# SlaveBoard_2020.net
KiCad netlist of a schematic drawn in Altium Designer
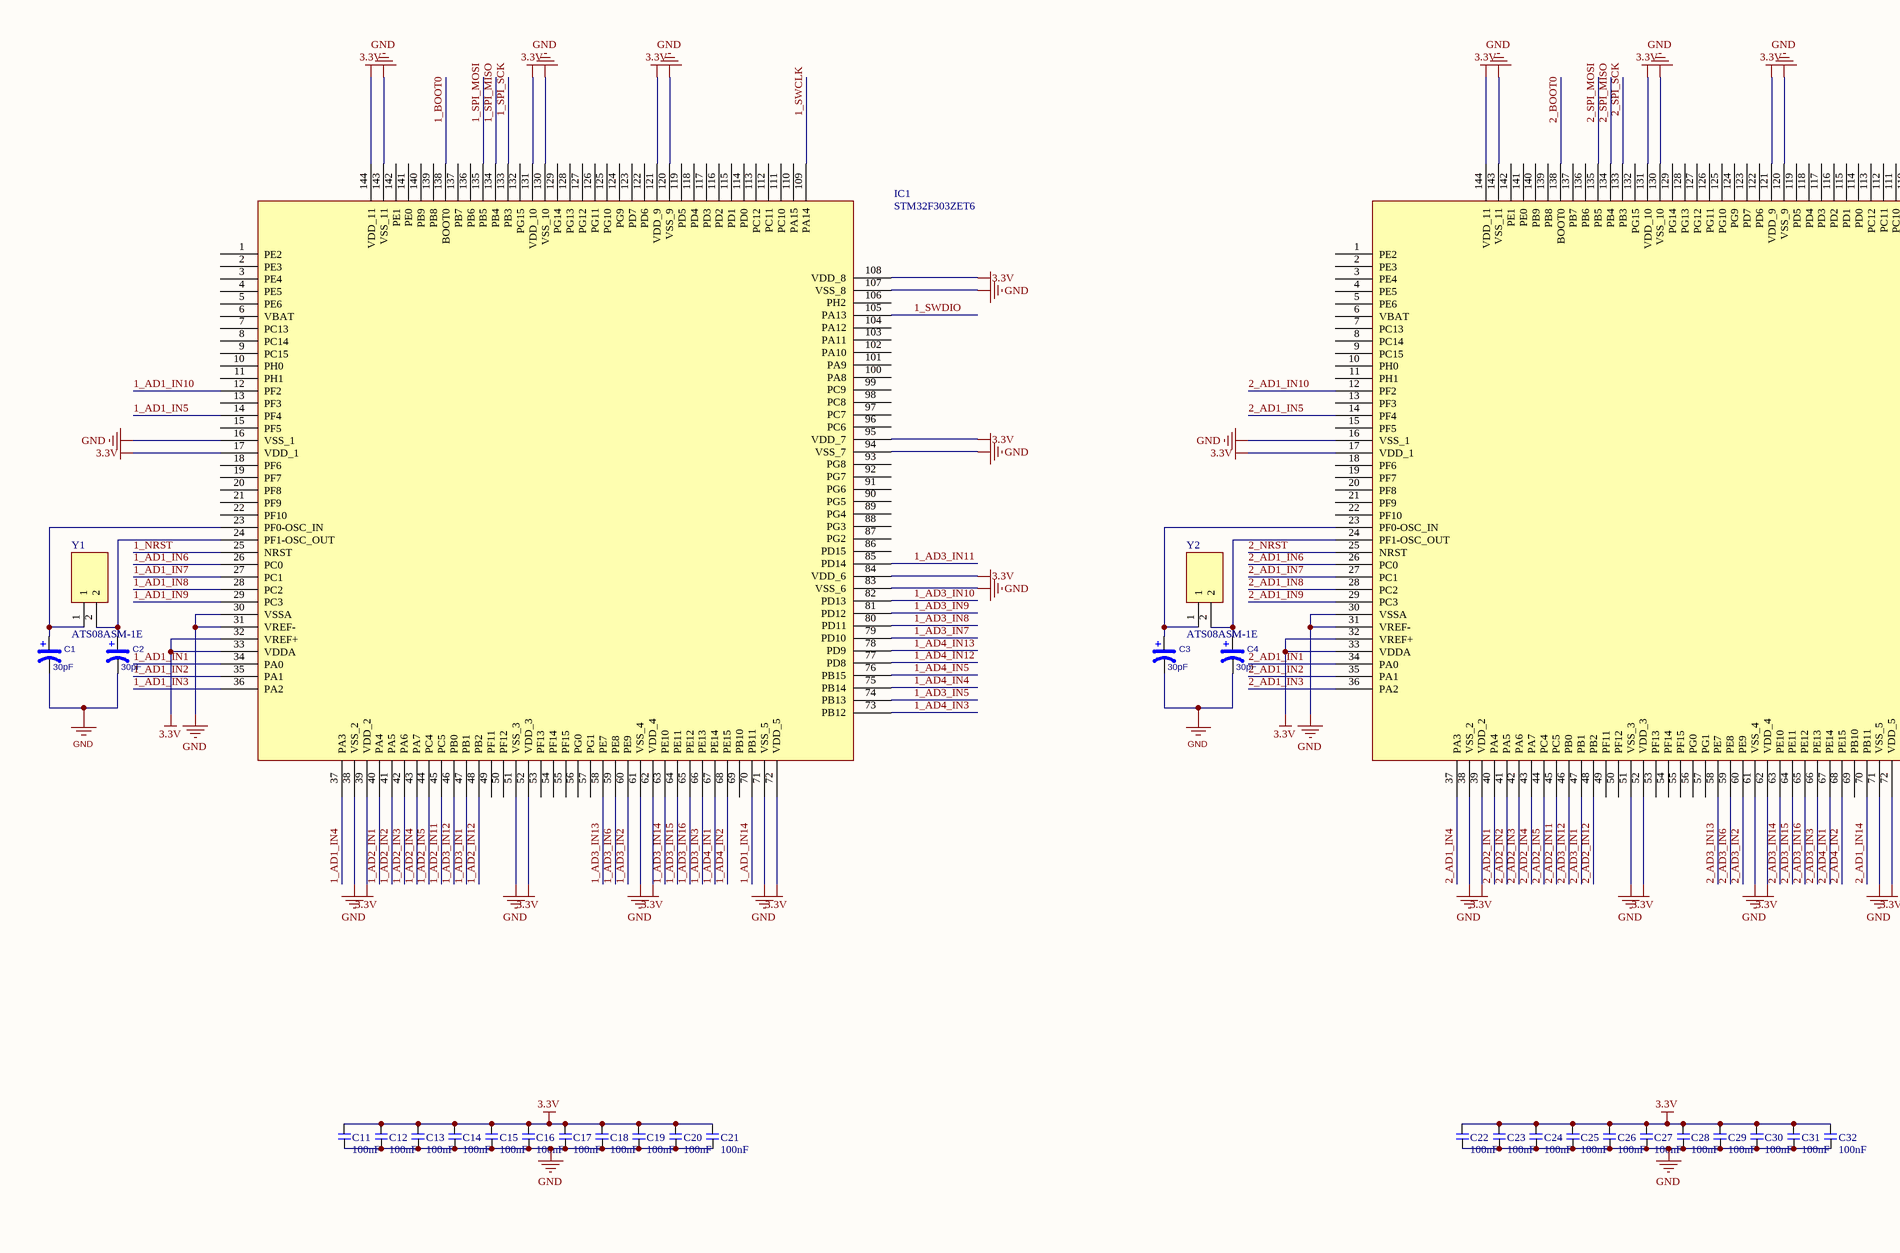
[diagram p0: SlaveBoard_2020.SchDoc, top left]
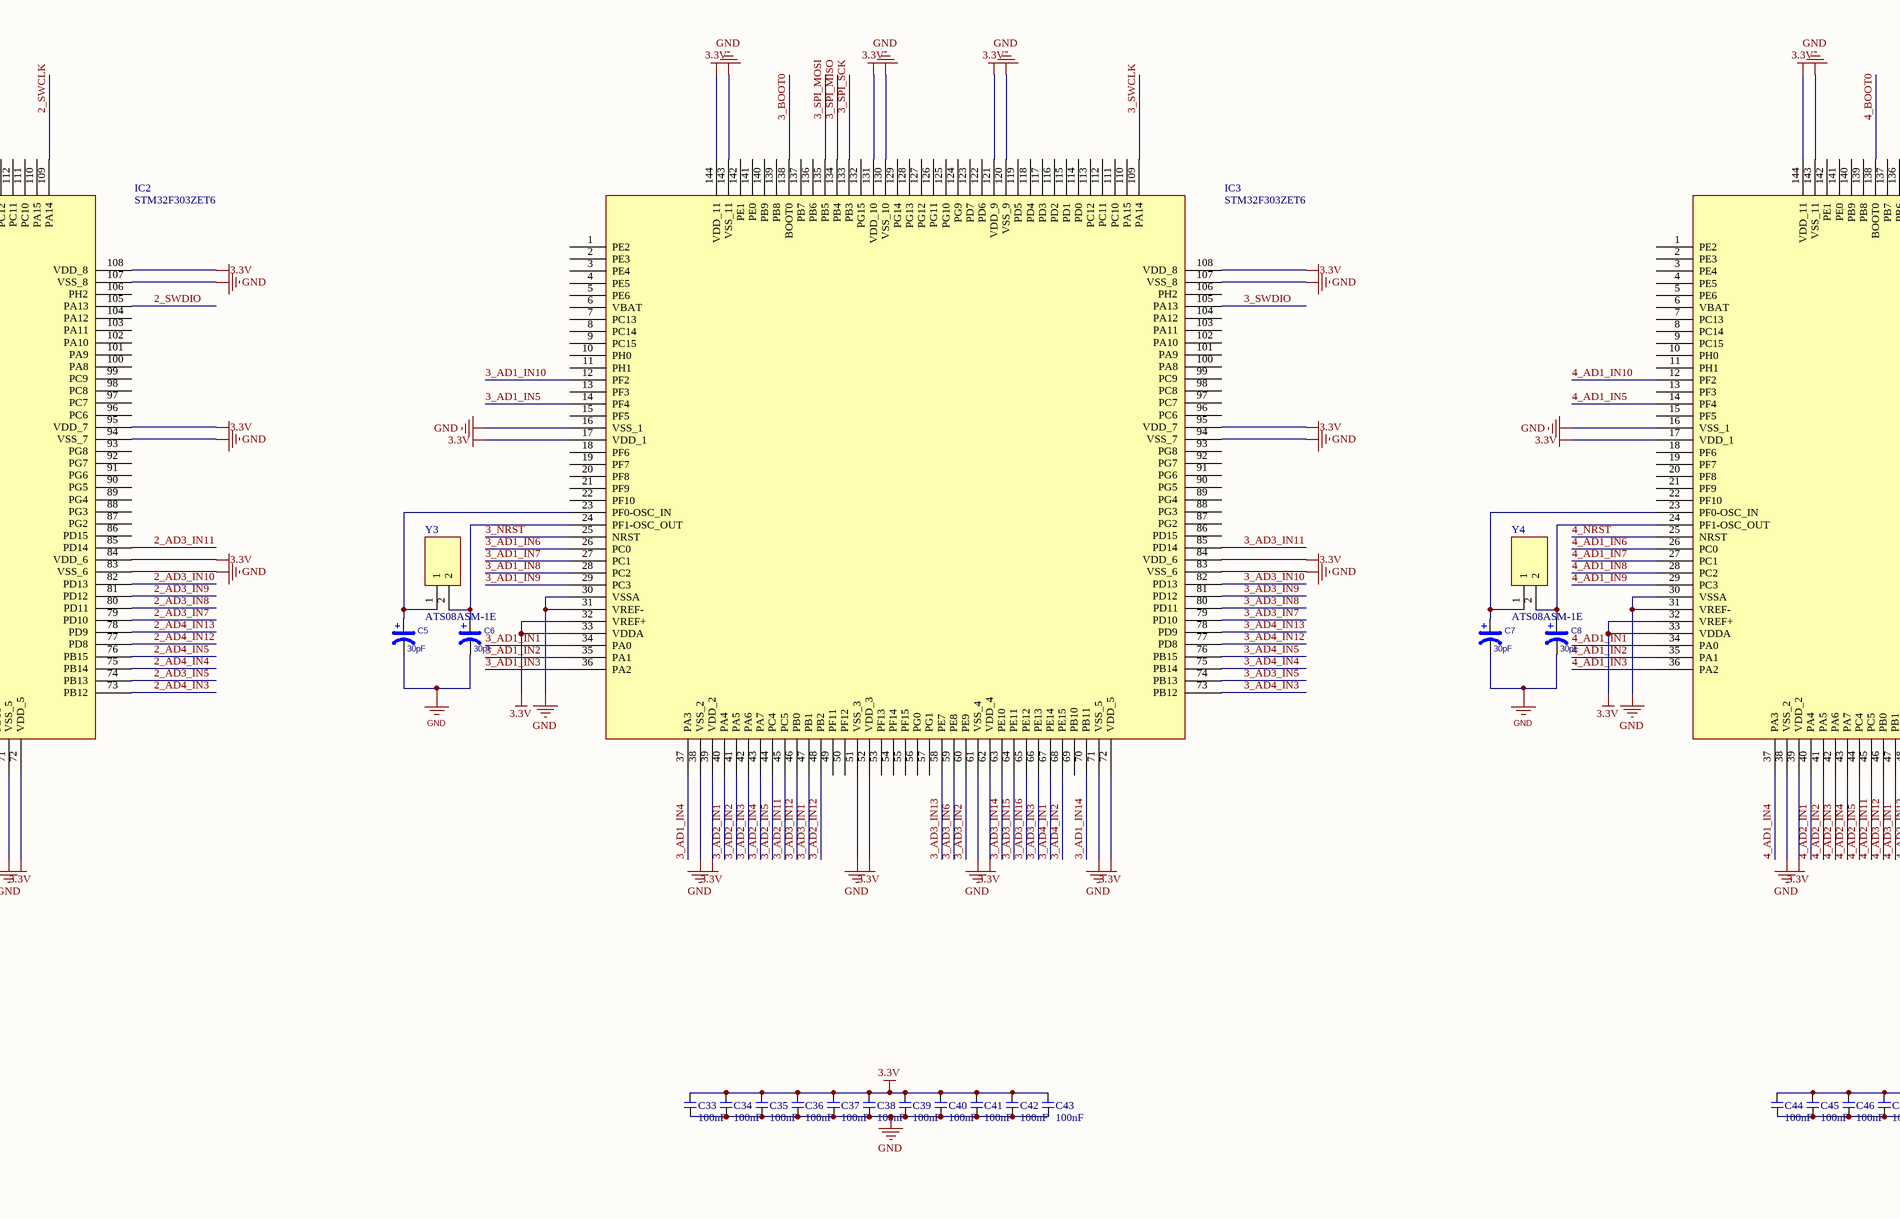
[diagram p1: SlaveBoard_2020.SchDoc, top middle]
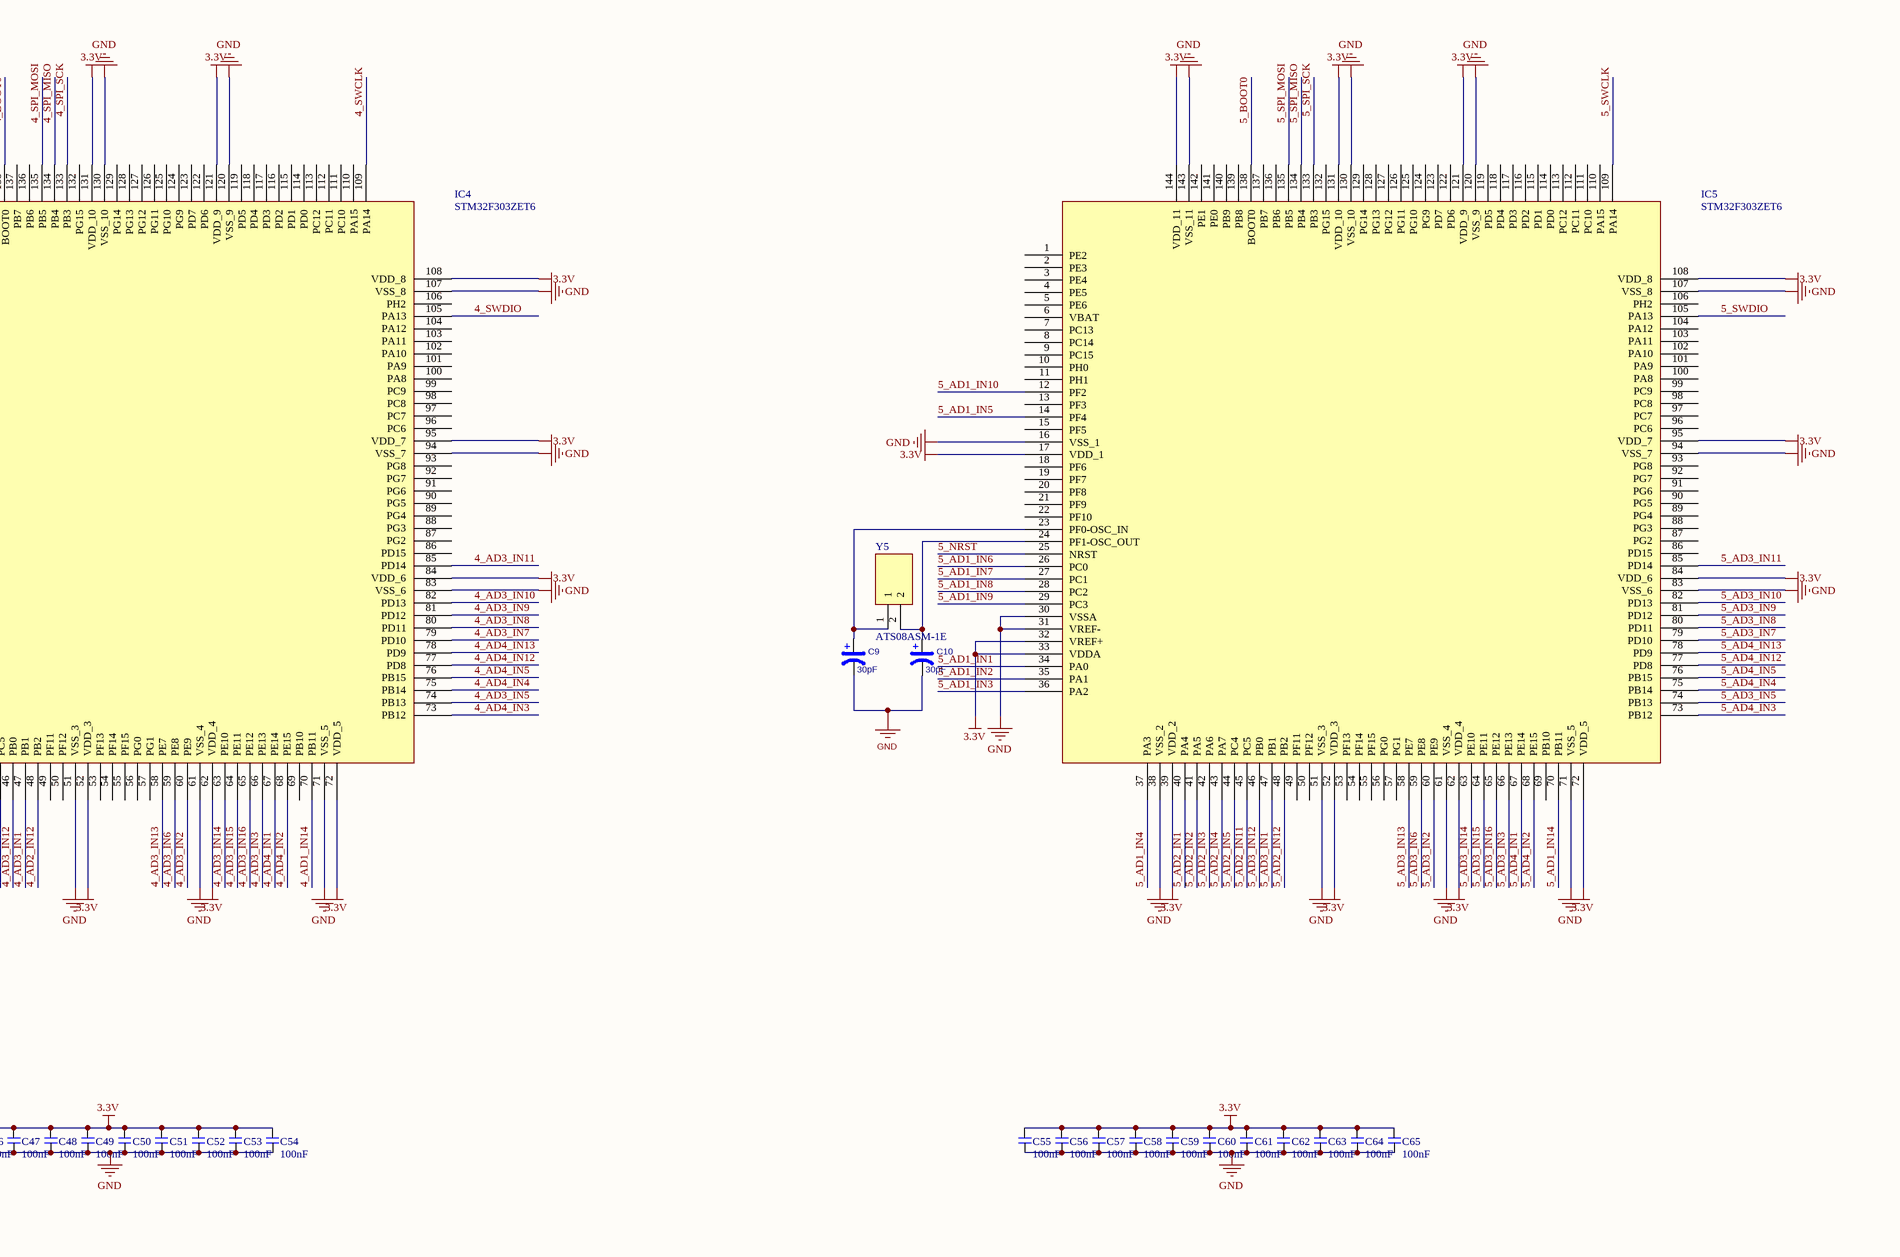
[diagram p2: SlaveBoard_2020.SchDoc, top right]
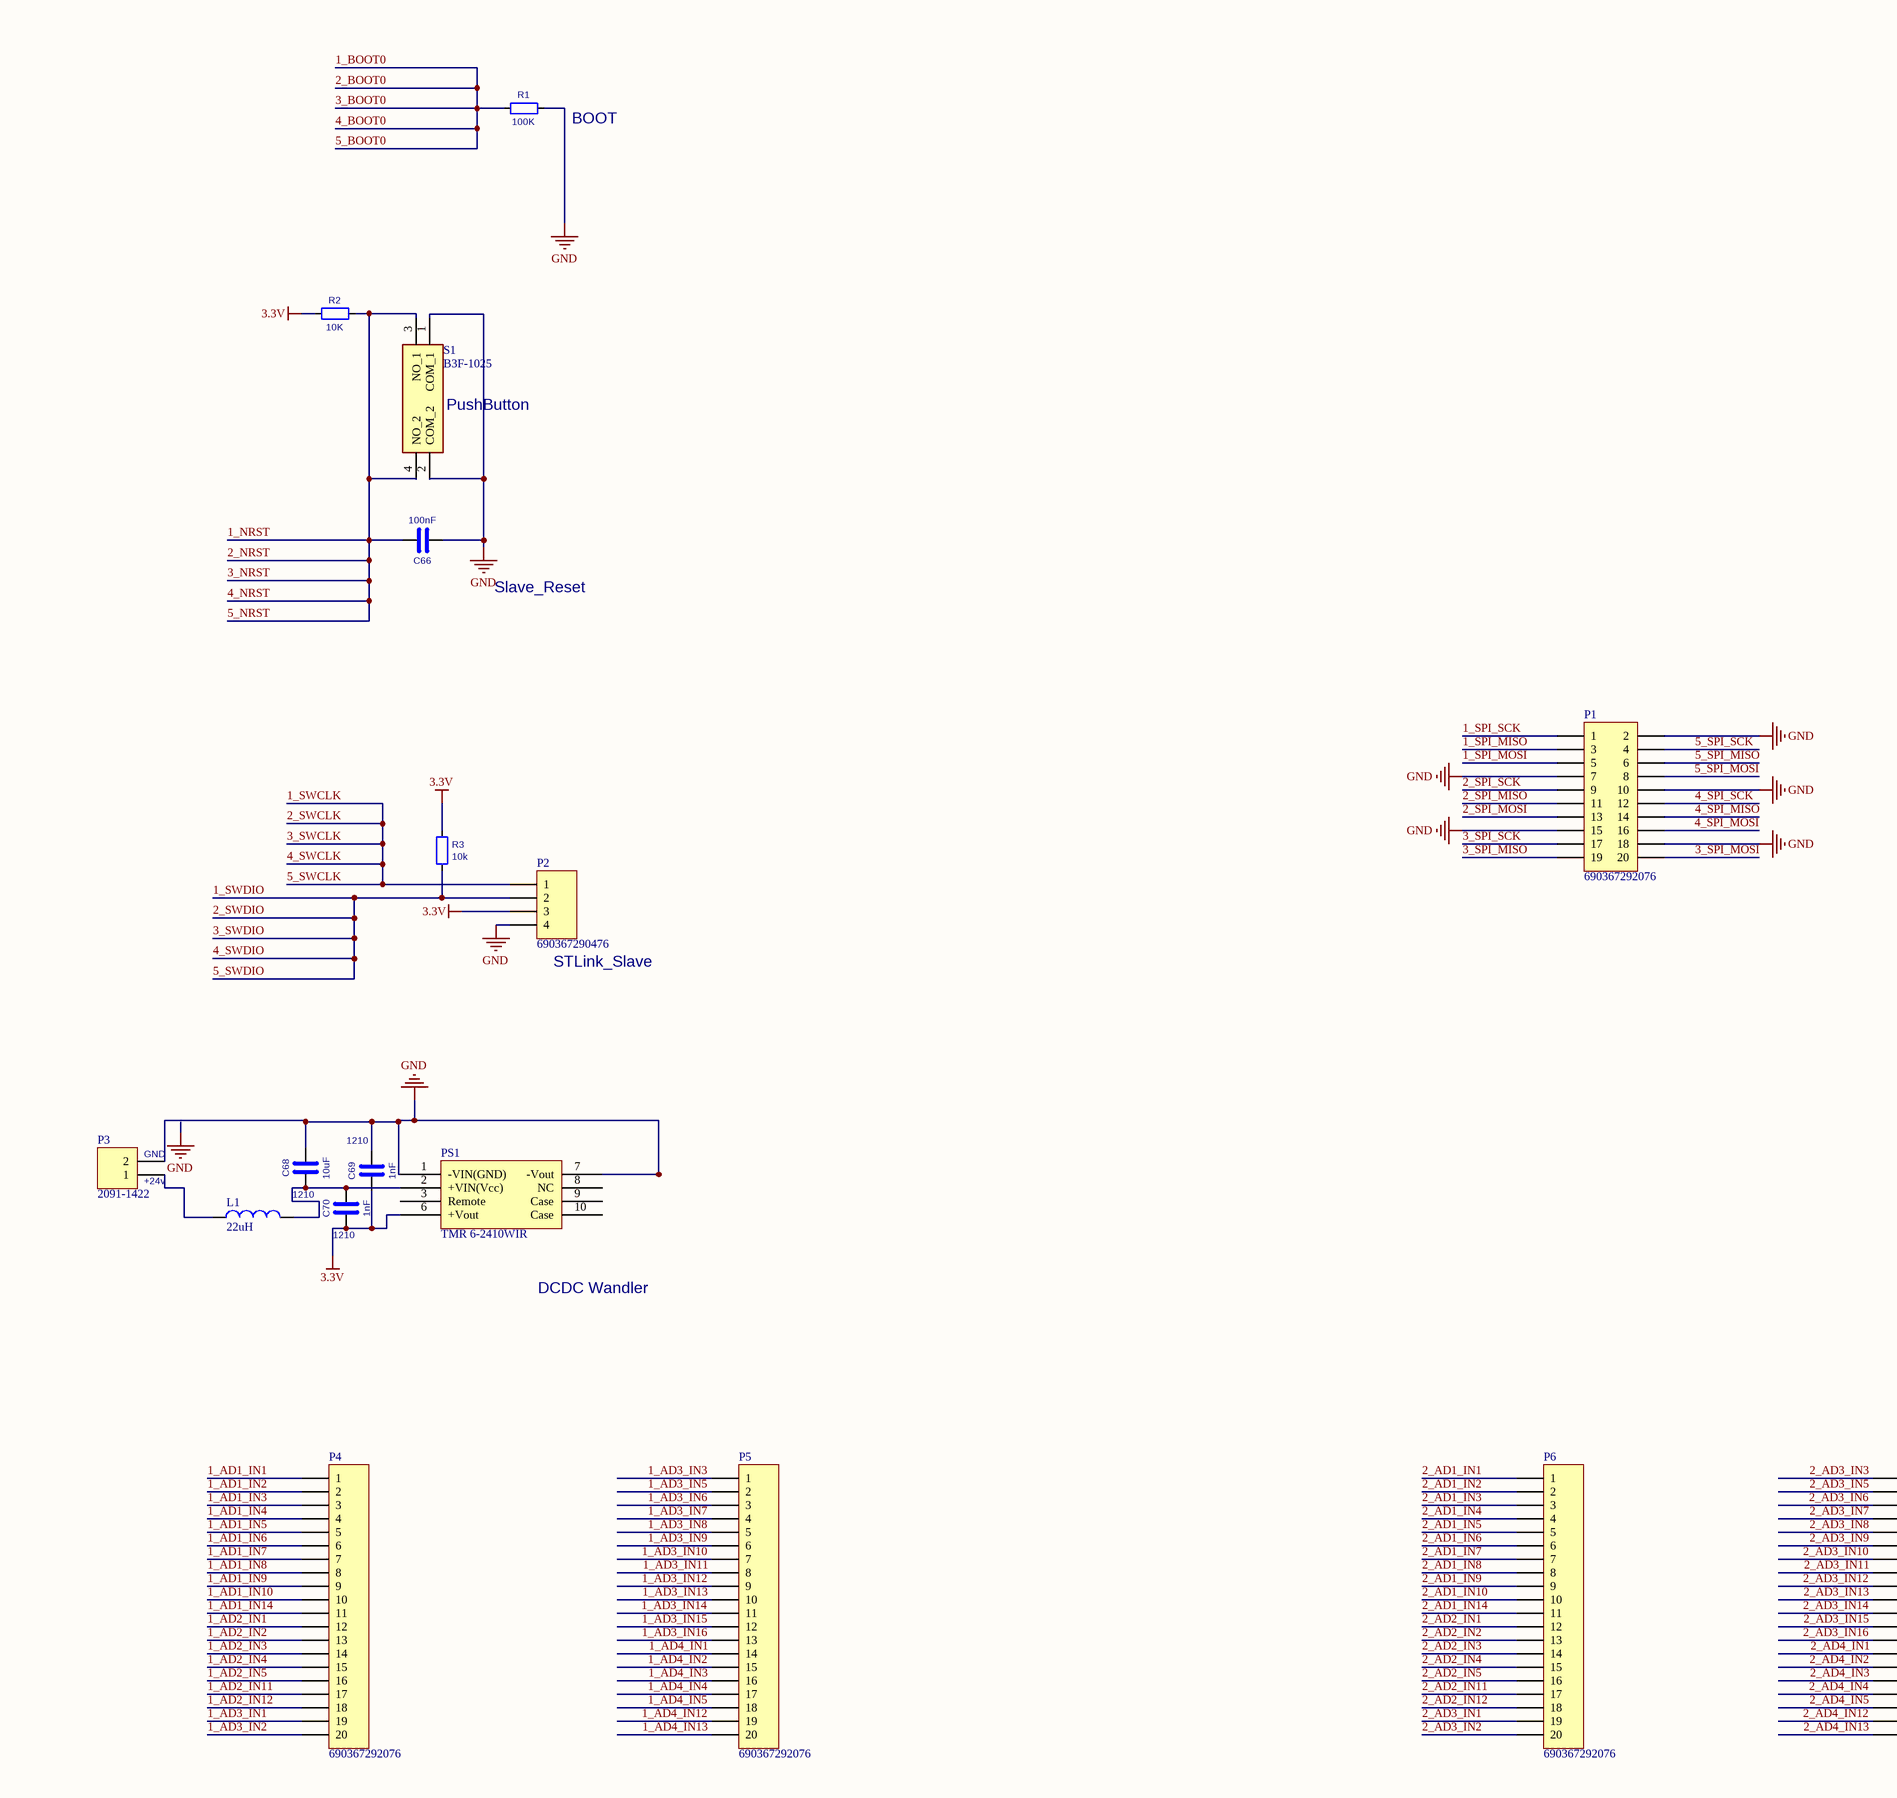
[diagram p3: SlaveBoard_2020.SchDoc, bottom left]
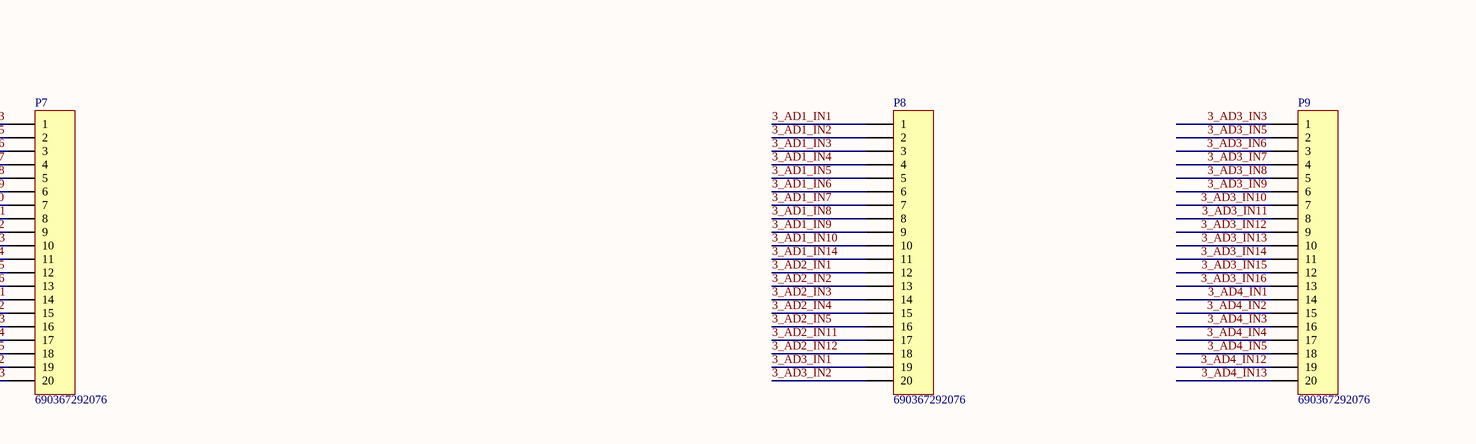
[diagram p4: SlaveBoard_2020.SchDoc, bottom middle]
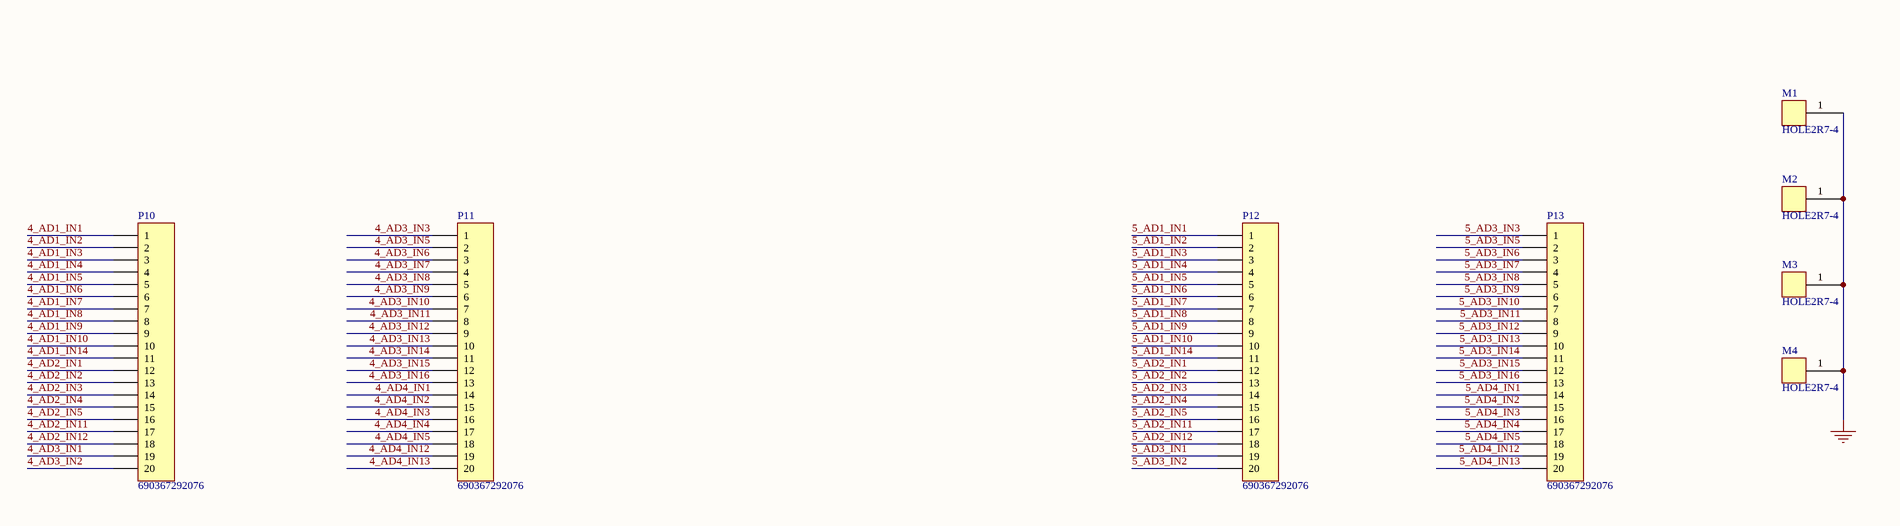
[diagram p5: SlaveBoard_2020.SchDoc, bottom right]

(export (version "E")
  (design (tool "Eeschema 10.0.6"))
  (components
    (comp (ref "C1") (value "30pF") (footprint "C0603") (libsource (lib "Device") (part "CP1")))
    (comp (ref "C2") (value "30pF") (footprint "C0603") (libsource (lib "Device") (part "CP1")))
    (comp (ref "C3") (value "30pF") (footprint "C0603") (libsource (lib "Device") (part "CP1")))
    (comp (ref "C4") (value "30pF") (footprint "C0603") (libsource (lib "Device") (part "CP1")))
    (comp (ref "C5") (value "30pF") (footprint "C0603") (libsource (lib "Device") (part "CP1")))
    (comp (ref "C6") (value "30pF") (footprint "C0603") (libsource (lib "Device") (part "CP1")))
    (comp (ref "C7") (value "30pF") (footprint "C0603") (libsource (lib "Device") (part "CP1")))
    (comp (ref "C8") (value "30pF") (footprint "C0603") (libsource (lib "Device") (part "CP1")))
    (comp (ref "C9") (value "30pF") (footprint "C0603") (libsource (lib "Device") (part "CP1")))
    (comp (ref "C10") (value "30pF") (footprint "C0603") (libsource (lib "Device") (part "CP1")))
    (comp (ref "C11") (value "100nF") (footprint "C0603") (libsource (lib "My_Chip") (part "Cap_0805")))
    (comp (ref "C12") (value "100nF") (footprint "C0603") (libsource (lib "My_Chip") (part "Cap_0805")))
    (comp (ref "C13") (value "100nF") (footprint "C0603") (libsource (lib "My_Chip") (part "Cap_0805")))
    (comp (ref "C14") (value "100nF") (footprint "C0603") (libsource (lib "My_Chip") (part "Cap_0805")))
    (comp (ref "C15") (value "100nF") (footprint "C0603") (libsource (lib "My_Chip") (part "Cap_0805")))
    (comp (ref "C16") (value "100nF") (footprint "C0603") (libsource (lib "My_Chip") (part "Cap_0805")))
    (comp (ref "C17") (value "100nF") (footprint "C0603") (libsource (lib "My_Chip") (part "Cap_0805")))
    (comp (ref "C18") (value "100nF") (footprint "C0603") (libsource (lib "My_Chip") (part "Cap_0805")))
    (comp (ref "C19") (value "100nF") (footprint "C0603") (libsource (lib "My_Chip") (part "Cap_0805")))
    (comp (ref "C20") (value "100nF") (footprint "C0603") (libsource (lib "My_Chip") (part "Cap_0805")))
    (comp (ref "C21") (value "100nF") (footprint "C0603") (libsource (lib "My_Chip") (part "Cap_0805")))
    (comp (ref "C22") (value "100nF") (footprint "C0603") (libsource (lib "My_Chip") (part "Cap_0805")))
    (comp (ref "C23") (value "100nF") (footprint "C0603") (libsource (lib "My_Chip") (part "Cap_0805")))
    (comp (ref "C24") (value "100nF") (footprint "C0603") (libsource (lib "My_Chip") (part "Cap_0805")))
    (comp (ref "C25") (value "100nF") (footprint "C0603") (libsource (lib "My_Chip") (part "Cap_0805")))
    (comp (ref "C26") (value "100nF") (footprint "C0603") (libsource (lib "My_Chip") (part "Cap_0805")))
    (comp (ref "C27") (value "100nF") (footprint "C0603") (libsource (lib "My_Chip") (part "Cap_0805")))
    (comp (ref "C28") (value "100nF") (footprint "C0603") (libsource (lib "My_Chip") (part "Cap_0805")))
    (comp (ref "C29") (value "100nF") (footprint "C0603") (libsource (lib "My_Chip") (part "Cap_0805")))
    (comp (ref "C30") (value "100nF") (footprint "C0603") (libsource (lib "My_Chip") (part "Cap_0805")))
    (comp (ref "C31") (value "100nF") (footprint "C0603") (libsource (lib "My_Chip") (part "Cap_0805")))
    (comp (ref "C32") (value "100nF") (footprint "C0603") (libsource (lib "My_Chip") (part "Cap_0805")))
    (comp (ref "C33") (value "100nF") (footprint "C0603") (libsource (lib "My_Chip") (part "Cap_0805")))
    (comp (ref "C34") (value "100nF") (footprint "C0603") (libsource (lib "My_Chip") (part "Cap_0805")))
    (comp (ref "C35") (value "100nF") (footprint "C0603") (libsource (lib "My_Chip") (part "Cap_0805")))
    (comp (ref "C36") (value "100nF") (footprint "C0603") (libsource (lib "My_Chip") (part "Cap_0805")))
    (comp (ref "C37") (value "100nF") (footprint "C0603") (libsource (lib "My_Chip") (part "Cap_0805")))
    (comp (ref "C38") (value "100nF") (footprint "C0603") (libsource (lib "My_Chip") (part "Cap_0805")))
    (comp (ref "C39") (value "100nF") (footprint "C0603") (libsource (lib "My_Chip") (part "Cap_0805")))
    (comp (ref "C40") (value "100nF") (footprint "C0603") (libsource (lib "My_Chip") (part "Cap_0805")))
    (comp (ref "C41") (value "100nF") (footprint "C0603") (libsource (lib "My_Chip") (part "Cap_0805")))
    (comp (ref "C42") (value "100nF") (footprint "C0603") (libsource (lib "My_Chip") (part "Cap_0805")))
    (comp (ref "C43") (value "100nF") (footprint "C0603") (libsource (lib "My_Chip") (part "Cap_0805")))
    (comp (ref "C44") (value "100nF") (footprint "C0603") (libsource (lib "My_Chip") (part "Cap_0805")))
    (comp (ref "C45") (value "100nF") (footprint "C0603") (libsource (lib "My_Chip") (part "Cap_0805")))
    (comp (ref "C46") (value "100nF") (footprint "C0603") (libsource (lib "My_Chip") (part "Cap_0805")))
    (comp (ref "C47") (value "100nF") (footprint "C0603") (libsource (lib "My_Chip") (part "Cap_0805")))
    (comp (ref "C48") (value "100nF") (footprint "C0603") (libsource (lib "My_Chip") (part "Cap_0805")))
    (comp (ref "C49") (value "100nF") (footprint "C0603") (libsource (lib "My_Chip") (part "Cap_0805")))
    (comp (ref "C50") (value "100nF") (footprint "C0603") (libsource (lib "My_Chip") (part "Cap_0805")))
    (comp (ref "C51") (value "100nF") (footprint "C0603") (libsource (lib "My_Chip") (part "Cap_0805")))
    (comp (ref "C52") (value "100nF") (footprint "C0603") (libsource (lib "My_Chip") (part "Cap_0805")))
    (comp (ref "C53") (value "100nF") (footprint "C0603") (libsource (lib "My_Chip") (part "Cap_0805")))
    (comp (ref "C54") (value "100nF") (footprint "C0603") (libsource (lib "My_Chip") (part "Cap_0805")))
    (comp (ref "C55") (value "100nF") (footprint "C0603") (libsource (lib "My_Chip") (part "Cap_0805")))
    (comp (ref "C56") (value "100nF") (footprint "C0603") (libsource (lib "My_Chip") (part "Cap_0805")))
    (comp (ref "C57") (value "100nF") (footprint "C0603") (libsource (lib "My_Chip") (part "Cap_0805")))
    (comp (ref "C58") (value "100nF") (footprint "C0603") (libsource (lib "My_Chip") (part "Cap_0805")))
    (comp (ref "C59") (value "100nF") (footprint "C0603") (libsource (lib "My_Chip") (part "Cap_0805")))
    (comp (ref "C60") (value "100nF") (footprint "C0603") (libsource (lib "My_Chip") (part "Cap_0805")))
    (comp (ref "C61") (value "100nF") (footprint "C0603") (libsource (lib "My_Chip") (part "Cap_0805")))
    (comp (ref "C62") (value "100nF") (footprint "C0603") (libsource (lib "My_Chip") (part "Cap_0805")))
    (comp (ref "C63") (value "100nF") (footprint "C0603") (libsource (lib "My_Chip") (part "Cap_0805")))
    (comp (ref "C64") (value "100nF") (footprint "C0603") (libsource (lib "My_Chip") (part "Cap_0805")))
    (comp (ref "C65") (value "100nF") (footprint "C0603") (libsource (lib "My_Chip") (part "Cap_0805")))
    (comp (ref "C66") (value "100nF") (footprint "C0603") (libsource (lib "Device") (part "C")))
    (comp (ref "C68") (value "10uF") (footprint "C1210") (libsource (lib "Device") (part "C")))
    (comp (ref "C69") (value "1nF") (footprint "C1210") (libsource (lib "Device") (part "C")))
    (comp (ref "C70") (value "1nF") (footprint "C1210") (libsource (lib "Device") (part "C")))
    (comp (ref "IC1")
      (value "STM32F303ZET6")
      (footprint "f303QFP50P2200X2200X160-144N")
      (libsource (lib "SamacSys") (part "STM32F303ZET6"))
    )
    (comp (ref "IC2")
      (value "STM32F303ZET6")
      (footprint "f303QFP50P2200X2200X160-144N")
      (libsource (lib "SamacSys") (part "STM32F303ZET6"))
    )
    (comp (ref "IC3")
      (value "STM32F303ZET6")
      (footprint "f303QFP50P2200X2200X160-144N")
      (libsource (lib "SamacSys") (part "STM32F303ZET6"))
    )
    (comp (ref "IC4")
      (value "STM32F303ZET6")
      (footprint "f303QFP50P2200X2200X160-144N")
      (libsource (lib "SamacSys") (part "STM32F303ZET6"))
    )
    (comp (ref "IC5")
      (value "STM32F303ZET6")
      (footprint "f303QFP50P2200X2200X160-144N")
      (libsource (lib "SamacSys") (part "STM32F303ZET6"))
    )
    (comp (ref "L1")
      (value "22uH")
      (footprint "L1_74404054220")
      (description "Inductor")
      (libsource (lib "Simulation Generic Components") (part "Inductor"))
    )
    (comp (ref "M1")
      (value "HOLE2R7-4")
      (footprint "HOLE2R7-4")
      (libsource (lib "SamacSys") (part "HOLE2R7-4"))
    )
    (comp (ref "M2")
      (value "HOLE2R7-4")
      (footprint "HOLE2R7-4")
      (libsource (lib "SamacSys") (part "HOLE2R7-4"))
    )
    (comp (ref "M3")
      (value "HOLE2R7-4")
      (footprint "HOLE2R7-4")
      (libsource (lib "SamacSys") (part "HOLE2R7-4"))
    )
    (comp (ref "M4")
      (value "HOLE2R7-4")
      (footprint "HOLE2R7-4")
      (libsource (lib "SamacSys") (part "HOLE2R7-4"))
    )
    (comp (ref "P1")
      (value "690367292076")
      (footprint "conn20pin")
      (description "Header, 10-Pin, Dual row")
      (fields (field (name "PUBLISHER") "Altium Limited"))
      (libsource (lib "Miscellaneous Connectors") (part "MHDR2X10"))
    )
    (comp (ref "P2")
      (value "690367290476")
      (footprint "Conn4pin")
      (description "Header, 4-Pin")
      (fields (field (name "PUBLISHER") "Altium Limited"))
      (libsource (lib "Miscellaneous Connectors") (part "MHDR1X4"))
    )
    (comp (ref "P3")
      (value "2091-1422")
      (footprint "ConnPWR")
      (description "Header, 2-Pin")
      (fields (field (name "PUBLISHER") "Altium Limited"))
      (libsource (lib "Miscellaneous Connectors") (part "MHDR1X2"))
    )
    (comp (ref "P4")
      (value "690367292076")
      (footprint "conn20pin")
      (description "Header, 20-Pin")
      (fields (field (name "PUBLISHER") "Altium Limited"))
      (libsource (lib "Miscellaneous Connectors") (part "MHDR1X20"))
    )
    (comp (ref "P5")
      (value "690367292076")
      (footprint "conn20pin")
      (description "Header, 20-Pin")
      (fields (field (name "PUBLISHER") "Altium Limited"))
      (libsource (lib "Miscellaneous Connectors") (part "MHDR1X20"))
    )
    (comp (ref "P6")
      (value "690367292076")
      (footprint "conn20pin")
      (description "Header, 20-Pin")
      (fields (field (name "PUBLISHER") "Altium Limited"))
      (libsource (lib "Miscellaneous Connectors") (part "MHDR1X20"))
    )
    (comp (ref "P7")
      (value "690367292076")
      (footprint "conn20pin")
      (description "Header, 20-Pin")
      (fields (field (name "PUBLISHER") "Altium Limited"))
      (libsource (lib "Miscellaneous Connectors") (part "MHDR1X20"))
    )
    (comp (ref "P8")
      (value "690367292076")
      (footprint "conn20pin")
      (description "Header, 20-Pin")
      (fields (field (name "PUBLISHER") "Altium Limited"))
      (libsource (lib "Miscellaneous Connectors") (part "MHDR1X20"))
    )
    (comp (ref "P9")
      (value "690367292076")
      (footprint "conn20pin")
      (description "Header, 20-Pin")
      (fields (field (name "PUBLISHER") "Altium Limited"))
      (libsource (lib "Miscellaneous Connectors") (part "MHDR1X20"))
    )
    (comp (ref "P10")
      (value "690367292076")
      (footprint "conn20pin")
      (description "Header, 20-Pin")
      (fields (field (name "PUBLISHER") "Altium Limited"))
      (libsource (lib "Miscellaneous Connectors") (part "MHDR1X20"))
    )
    (comp (ref "P11")
      (value "690367292076")
      (footprint "conn20pin")
      (description "Header, 20-Pin")
      (fields (field (name "PUBLISHER") "Altium Limited"))
      (libsource (lib "Miscellaneous Connectors") (part "MHDR1X20"))
    )
    (comp (ref "P12")
      (value "690367292076")
      (footprint "conn20pin")
      (description "Header, 20-Pin")
      (fields (field (name "PUBLISHER") "Altium Limited"))
      (libsource (lib "Miscellaneous Connectors") (part "MHDR1X20"))
    )
    (comp (ref "P13")
      (value "690367292076")
      (footprint "conn20pin")
      (description "Header, 20-Pin")
      (fields (field (name "PUBLISHER") "Altium Limited"))
      (libsource (lib "Miscellaneous Connectors") (part "MHDR1X20"))
    )
    (comp (ref "PS1")
      (value "TMR 6-2410WIR")
      (footprint "TMR62410WIR")
      (description "DCDC Wandler")
      (libsource (lib "SamacSys") (part "TMR 6-2410WIR"))
    )
    (comp (ref "R1")
      (value "100K")
      (footprint "6-0805_N")
      (fields (field (name "Comment") "10K"))
      (libsource (lib "Device") (part "R"))
    )
    (comp (ref "R2") (value "10K") (footprint "6-0805_N") (libsource (lib "Device") (part "R")))
    (comp (ref "R3") (value "10k") (footprint "6-0805_N") (libsource (lib "") (part "R_1")))
    (comp (ref "S1")
      (value "B3F-1025")
      (footprint "B3F1025")
      (description "Switch")
      (fields (field (name "MOUSER PART NUMBER") "653-B3F-1025"))
      (libsource (lib "*") (part "B3F-1025"))
    )
    (comp (ref "Y1")
      (value "ATS08ASM-1E")
      (footprint "ATS040SM1")
      (description "Crystal or Oscillator")
      (fields (field (name "MOUSER PART NUMBER") "774-ATS08ASM-1E"))
      (libsource (lib "*") (part "ATS08ASM-1E"))
    )
    (comp (ref "Y2")
      (value "ATS08ASM-1E")
      (footprint "ATS040SM1")
      (description "Crystal or Oscillator")
      (fields (field (name "MOUSER PART NUMBER") "774-ATS08ASM-1E"))
      (libsource (lib "*") (part "ATS08ASM-1E"))
    )
    (comp (ref "Y3")
      (value "ATS08ASM-1E")
      (footprint "ATS040SM1")
      (description "Crystal or Oscillator")
      (fields (field (name "MOUSER PART NUMBER") "774-ATS08ASM-1E"))
      (libsource (lib "*") (part "ATS08ASM-1E"))
    )
    (comp (ref "Y4")
      (value "ATS08ASM-1E")
      (footprint "ATS040SM1")
      (description "Crystal or Oscillator")
      (fields (field (name "MOUSER PART NUMBER") "774-ATS08ASM-1E"))
      (libsource (lib "*") (part "ATS08ASM-1E"))
    )
    (comp (ref "Y5")
      (value "ATS08ASM-1E")
      (footprint "ATS040SM1")
      (description "Crystal or Oscillator")
      (fields (field (name "MOUSER PART NUMBER") "774-ATS08ASM-1E"))
      (libsource (lib "*") (part "ATS08ASM-1E"))
    )
  )
  (nets
    (net (code "1") (name "/1_AD1_IN1") (class "Default")
      (node (ref "IC1") (pin "34") (pinfunction "PA0_34") (pintype "passive"))
      (node (ref "P4") (pin "1") (pinfunction "1_1") (pintype "passive"))
    )
    (net (code "2") (name "/1_AD1_IN2") (class "Default")
      (node (ref "IC1") (pin "35") (pinfunction "PA1_35") (pintype "passive"))
      (node (ref "P4") (pin "2") (pinfunction "2_2") (pintype "passive"))
    )
    (net (code "3") (name "/1_AD1_IN3") (class "Default")
      (node (ref "IC1") (pin "36") (pinfunction "PA2_36") (pintype "passive"))
      (node (ref "P4") (pin "3") (pinfunction "3_3") (pintype "passive"))
    )
    (net (code "4") (name "/1_AD1_IN4") (class "Default")
      (node (ref "IC1") (pin "37") (pinfunction "PA3_37") (pintype "passive"))
      (node (ref "P4") (pin "4") (pinfunction "4_4") (pintype "passive"))
    )
    (net (code "5") (name "/1_AD1_IN5") (class "Default")
      (node (ref "IC1") (pin "14") (pinfunction "PF4_14") (pintype "passive"))
      (node (ref "P4") (pin "5") (pinfunction "5_5") (pintype "passive"))
    )
    (net (code "6") (name "/1_AD1_IN6") (class "Default")
      (node (ref "IC1") (pin "26") (pinfunction "PC0_26") (pintype "passive"))
      (node (ref "P4") (pin "6") (pinfunction "6_6") (pintype "passive"))
    )
    (net (code "7") (name "/1_AD1_IN7") (class "Default")
      (node (ref "IC1") (pin "27") (pinfunction "PC1_27") (pintype "passive"))
      (node (ref "P4") (pin "7") (pinfunction "7_7") (pintype "passive"))
    )
    (net (code "8") (name "/1_AD1_IN8") (class "Default")
      (node (ref "IC1") (pin "28") (pinfunction "PC2_28") (pintype "passive"))
      (node (ref "P4") (pin "8") (pinfunction "8_8") (pintype "passive"))
    )
    (net (code "9") (name "/1_AD1_IN9") (class "Default")
      (node (ref "IC1") (pin "29") (pinfunction "PC3_29") (pintype "passive"))
      (node (ref "P4") (pin "9") (pinfunction "9_9") (pintype "passive"))
    )
    (net (code "10") (name "/1_AD1_IN10") (class "Default")
      (node (ref "IC1") (pin "12") (pinfunction "PF2_12") (pintype "passive"))
      (node (ref "P4") (pin "10") (pinfunction "10_10") (pintype "passive"))
    )
    (net (code "11") (name "/1_AD1_IN14") (class "Default")
      (node (ref "IC1") (pin "70") (pinfunction "PB11_70") (pintype "passive"))
      (node (ref "P4") (pin "11") (pinfunction "11_11") (pintype "passive"))
    )
    (net (code "12") (name "/1_AD2_IN1") (class "Default")
      (node (ref "IC1") (pin "40") (pinfunction "PA4_40") (pintype "passive"))
      (node (ref "P4") (pin "12") (pinfunction "12_12") (pintype "passive"))
    )
    (net (code "13") (name "/1_AD2_IN2") (class "Default")
      (node (ref "IC1") (pin "41") (pinfunction "PA5_41") (pintype "passive"))
      (node (ref "P4") (pin "13") (pinfunction "13_13") (pintype "passive"))
    )
    (net (code "14") (name "/1_AD2_IN3") (class "Default")
      (node (ref "IC1") (pin "42") (pinfunction "PA6_42") (pintype "passive"))
      (node (ref "P4") (pin "14") (pinfunction "14_14") (pintype "passive"))
    )
    (net (code "15") (name "/1_AD2_IN4") (class "Default")
      (node (ref "IC1") (pin "43") (pinfunction "PA7_43") (pintype "passive"))
      (node (ref "P4") (pin "15") (pinfunction "15_15") (pintype "passive"))
    )
    (net (code "16") (name "/1_AD2_IN5") (class "Default")
      (node (ref "IC1") (pin "44") (pinfunction "PC4_44") (pintype "passive"))
      (node (ref "P4") (pin "16") (pinfunction "16_16") (pintype "passive"))
    )
    (net (code "17") (name "/1_AD2_IN11") (class "Default")
      (node (ref "IC1") (pin "45") (pinfunction "PC5_45") (pintype "passive"))
      (node (ref "P4") (pin "17") (pinfunction "17_17") (pintype "passive"))
    )
    (net (code "18") (name "/1_AD2_IN12") (class "Default")
      (node (ref "IC1") (pin "48") (pinfunction "PB2_48") (pintype "passive"))
      (node (ref "P4") (pin "18") (pinfunction "18_18") (pintype "passive"))
    )
    (net (code "19") (name "/1_AD3_IN1") (class "Default")
      (node (ref "IC1") (pin "47") (pinfunction "PB1_47") (pintype "passive"))
      (node (ref "P4") (pin "19") (pinfunction "19_19") (pintype "passive"))
    )
    (net (code "20") (name "/1_AD3_IN2") (class "Default")
      (node (ref "IC1") (pin "60") (pinfunction "PE9_60") (pintype "passive"))
      (node (ref "P4") (pin "20") (pinfunction "20_20") (pintype "passive"))
    )
    (net (code "21") (name "/1_AD3_IN3") (class "Default")
      (node (ref "IC1") (pin "66") (pinfunction "PE13_66") (pintype "passive"))
      (node (ref "P5") (pin "1") (pinfunction "1_1") (pintype "passive"))
    )
    (net (code "22") (name "/1_AD3_IN5") (class "Default")
      (node (ref "IC1") (pin "74") (pinfunction "PB13_74") (pintype "passive"))
      (node (ref "P5") (pin "2") (pinfunction "2_2") (pintype "passive"))
    )
    (net (code "23") (name "/1_AD3_IN6") (class "Default")
      (node (ref "IC1") (pin "59") (pinfunction "PE8_59") (pintype "passive"))
      (node (ref "P5") (pin "3") (pinfunction "3_3") (pintype "passive"))
    )
    (net (code "24") (name "/1_AD3_IN7") (class "Default")
      (node (ref "IC1") (pin "79") (pinfunction "PD10_79") (pintype "passive"))
      (node (ref "P5") (pin "4") (pinfunction "4_4") (pintype "passive"))
    )
    (net (code "25") (name "/1_AD3_IN8") (class "Default")
      (node (ref "IC1") (pin "80") (pinfunction "PD11_80") (pintype "passive"))
      (node (ref "P5") (pin "5") (pinfunction "5_5") (pintype "passive"))
    )
    (net (code "26") (name "/1_AD3_IN9") (class "Default")
      (node (ref "IC1") (pin "81") (pinfunction "PD12_81") (pintype "passive"))
      (node (ref "P5") (pin "6") (pinfunction "6_6") (pintype "passive"))
    )
    (net (code "27") (name "/1_AD3_IN10") (class "Default")
      (node (ref "IC1") (pin "82") (pinfunction "PD13_82") (pintype "passive"))
      (node (ref "P5") (pin "7") (pinfunction "7_7") (pintype "passive"))
    )
    (net (code "28") (name "/1_AD3_IN11") (class "Default")
      (node (ref "IC1") (pin "85") (pinfunction "PD14_85") (pintype "passive"))
      (node (ref "P5") (pin "8") (pinfunction "8_8") (pintype "passive"))
    )
    (net (code "29") (name "/1_AD3_IN12") (class "Default")
      (node (ref "IC1") (pin "46") (pinfunction "PB0_46") (pintype "passive"))
      (node (ref "P5") (pin "9") (pinfunction "9_9") (pintype "passive"))
    )
    (net (code "30") (name "/1_AD3_IN13") (class "Default")
      (node (ref "IC1") (pin "58") (pinfunction "PE7_58") (pintype "passive"))
      (node (ref "P5") (pin "10") (pinfunction "10_10") (pintype "passive"))
    )
    (net (code "31") (name "/1_AD3_IN14") (class "Default")
      (node (ref "IC1") (pin "63") (pinfunction "PE10_63") (pintype "passive"))
      (node (ref "P5") (pin "11") (pinfunction "11_11") (pintype "passive"))
    )
    (net (code "32") (name "/1_AD3_IN15") (class "Default")
      (node (ref "IC1") (pin "64") (pinfunction "PE11_64") (pintype "passive"))
      (node (ref "P5") (pin "12") (pinfunction "12_12") (pintype "passive"))
    )
    (net (code "33") (name "/1_AD3_IN16") (class "Default")
      (node (ref "IC1") (pin "65") (pinfunction "PE12_65") (pintype "passive"))
      (node (ref "P5") (pin "13") (pinfunction "13_13") (pintype "passive"))
    )
    (net (code "34") (name "/1_AD4_IN1") (class "Default")
      (node (ref "IC1") (pin "67") (pinfunction "PE14_67") (pintype "passive"))
      (node (ref "P5") (pin "14") (pinfunction "14_14") (pintype "passive"))
    )
    (net (code "35") (name "/1_AD4_IN2") (class "Default")
      (node (ref "IC1") (pin "68") (pinfunction "PE15_68") (pintype "passive"))
      (node (ref "P5") (pin "15") (pinfunction "15_15") (pintype "passive"))
    )
    (net (code "36") (name "/1_AD4_IN3") (class "Default")
      (node (ref "IC1") (pin "73") (pinfunction "PB12_73") (pintype "passive"))
      (node (ref "P5") (pin "16") (pinfunction "16_16") (pintype "passive"))
    )
    (net (code "37") (name "/1_AD4_IN4") (class "Default")
      (node (ref "IC1") (pin "75") (pinfunction "PB14_75") (pintype "passive"))
      (node (ref "P5") (pin "17") (pinfunction "17_17") (pintype "passive"))
    )
    (net (code "38") (name "/1_AD4_IN5") (class "Default")
      (node (ref "IC1") (pin "76") (pinfunction "PB15_76") (pintype "passive"))
      (node (ref "P5") (pin "18") (pinfunction "18_18") (pintype "passive"))
    )
    (net (code "39") (name "/1_AD4_IN12") (class "Default")
      (node (ref "IC1") (pin "77") (pinfunction "PD8_77") (pintype "passive"))
      (node (ref "P5") (pin "19") (pinfunction "19_19") (pintype "passive"))
    )
    (net (code "40") (name "/1_AD4_IN13") (class "Default")
      (node (ref "IC1") (pin "78") (pinfunction "PD9_78") (pintype "passive"))
      (node (ref "P5") (pin "20") (pinfunction "20_20") (pintype "passive"))
    )
    (net (code "41") (name "/1_BOOT0") (class "Default")
      (node (ref "IC1") (pin "138") (pinfunction "BOOT0_138") (pintype "passive"))
      (node (ref "IC2") (pin "138") (pinfunction "BOOT0_138") (pintype "passive"))
      (node (ref "IC3") (pin "138") (pinfunction "BOOT0_138") (pintype "passive"))
      (node (ref "IC4") (pin "138") (pinfunction "BOOT0_138") (pintype "passive"))
      (node (ref "IC5") (pin "138") (pinfunction "BOOT0_138") (pintype "passive"))
      (node (ref "R1") (pin "2") (pinfunction "2_2") (pintype "passive"))
    )
    (net (code "42") (name "/1_NRST") (class "Default")
      (node (ref "C66") (pin "1") (pinfunction "1_1") (pintype "passive"))
      (node (ref "IC1") (pin "25") (pinfunction "NRST_25") (pintype "passive"))
      (node (ref "IC2") (pin "25") (pinfunction "NRST_25") (pintype "passive"))
      (node (ref "IC3") (pin "25") (pinfunction "NRST_25") (pintype "passive"))
      (node (ref "IC4") (pin "25") (pinfunction "NRST_25") (pintype "passive"))
      (node (ref "IC5") (pin "25") (pinfunction "NRST_25") (pintype "passive"))
      (node (ref "R2") (pin "1") (pinfunction "1_1") (pintype "passive"))
      (node (ref "S1") (pin "3") (pinfunction "NO_1_3") (pintype "passive"))
      (node (ref "S1") (pin "4") (pinfunction "NO_2_4") (pintype "passive"))
    )
    (net (code "43") (name "/1_SPI_MISO") (class "Default")
      (node (ref "IC1") (pin "134") (pinfunction "PB4_134") (pintype "passive"))
      (node (ref "P1") (pin "3") (pinfunction "3_3") (pintype "passive"))
    )
    (net (code "44") (name "/1_SPI_MOSI") (class "Default")
      (node (ref "IC1") (pin "135") (pinfunction "PB5_135") (pintype "passive"))
      (node (ref "P1") (pin "5") (pinfunction "5_5") (pintype "passive"))
    )
    (net (code "45") (name "/1_SPI_SCK") (class "Default")
      (node (ref "IC1") (pin "133") (pinfunction "PB3_133") (pintype "passive"))
      (node (ref "P1") (pin "1") (pinfunction "1_1") (pintype "passive"))
    )
    (net (code "46") (name "/1_SWCLK") (class "Default")
      (node (ref "IC1") (pin "109") (pinfunction "PA14_109") (pintype "passive"))
      (node (ref "IC2") (pin "109") (pinfunction "PA14_109") (pintype "passive"))
      (node (ref "IC3") (pin "109") (pinfunction "PA14_109") (pintype "passive"))
      (node (ref "IC4") (pin "109") (pinfunction "PA14_109") (pintype "passive"))
      (node (ref "IC5") (pin "109") (pinfunction "PA14_109") (pintype "passive"))
      (node (ref "P2") (pin "1") (pinfunction "1_1") (pintype "passive"))
    )
    (net (code "47") (name "/1_SWDIO") (class "Default")
      (node (ref "IC1") (pin "105") (pinfunction "PA13_105") (pintype "passive"))
      (node (ref "IC2") (pin "105") (pinfunction "PA13_105") (pintype "passive"))
      (node (ref "IC3") (pin "105") (pinfunction "PA13_105") (pintype "passive"))
      (node (ref "IC4") (pin "105") (pinfunction "PA13_105") (pintype "passive"))
      (node (ref "IC5") (pin "105") (pinfunction "PA13_105") (pintype "passive"))
      (node (ref "P2") (pin "2") (pinfunction "2_2") (pintype "passive"))
      (node (ref "R3") (pin "2") (pinfunction "2_2") (pintype "passive"))
    )
    (net (code "48") (name "/2_AD1_IN1") (class "Default")
      (node (ref "IC2") (pin "34") (pinfunction "PA0_34") (pintype "passive"))
      (node (ref "P6") (pin "1") (pinfunction "1_1") (pintype "passive"))
    )
    (net (code "49") (name "/2_AD1_IN2") (class "Default")
      (node (ref "IC2") (pin "35") (pinfunction "PA1_35") (pintype "passive"))
      (node (ref "P6") (pin "2") (pinfunction "2_2") (pintype "passive"))
    )
    (net (code "50") (name "/2_AD1_IN3") (class "Default")
      (node (ref "IC2") (pin "36") (pinfunction "PA2_36") (pintype "passive"))
      (node (ref "P6") (pin "3") (pinfunction "3_3") (pintype "passive"))
    )
    (net (code "51") (name "/2_AD1_IN4") (class "Default")
      (node (ref "IC2") (pin "37") (pinfunction "PA3_37") (pintype "passive"))
      (node (ref "P6") (pin "4") (pinfunction "4_4") (pintype "passive"))
    )
    (net (code "52") (name "/2_AD1_IN5") (class "Default")
      (node (ref "IC2") (pin "14") (pinfunction "PF4_14") (pintype "passive"))
      (node (ref "P6") (pin "5") (pinfunction "5_5") (pintype "passive"))
    )
    (net (code "53") (name "/2_AD1_IN6") (class "Default")
      (node (ref "IC2") (pin "26") (pinfunction "PC0_26") (pintype "passive"))
      (node (ref "P6") (pin "6") (pinfunction "6_6") (pintype "passive"))
    )
    (net (code "54") (name "/2_AD1_IN7") (class "Default")
      (node (ref "IC2") (pin "27") (pinfunction "PC1_27") (pintype "passive"))
      (node (ref "P6") (pin "7") (pinfunction "7_7") (pintype "passive"))
    )
    (net (code "55") (name "/2_AD1_IN8") (class "Default")
      (node (ref "IC2") (pin "28") (pinfunction "PC2_28") (pintype "passive"))
      (node (ref "P6") (pin "8") (pinfunction "8_8") (pintype "passive"))
    )
    (net (code "56") (name "/2_AD1_IN9") (class "Default")
      (node (ref "IC2") (pin "29") (pinfunction "PC3_29") (pintype "passive"))
      (node (ref "P6") (pin "9") (pinfunction "9_9") (pintype "passive"))
    )
    (net (code "57") (name "/2_AD1_IN10") (class "Default")
      (node (ref "IC2") (pin "12") (pinfunction "PF2_12") (pintype "passive"))
      (node (ref "P6") (pin "10") (pinfunction "10_10") (pintype "passive"))
    )
    (net (code "58") (name "/2_AD1_IN14") (class "Default")
      (node (ref "IC2") (pin "70") (pinfunction "PB11_70") (pintype "passive"))
      (node (ref "P6") (pin "11") (pinfunction "11_11") (pintype "passive"))
    )
    (net (code "59") (name "/2_AD2_IN1") (class "Default")
      (node (ref "IC2") (pin "40") (pinfunction "PA4_40") (pintype "passive"))
      (node (ref "P6") (pin "12") (pinfunction "12_12") (pintype "passive"))
    )
    (net (code "60") (name "/2_AD2_IN2") (class "Default")
      (node (ref "IC2") (pin "41") (pinfunction "PA5_41") (pintype "passive"))
      (node (ref "P6") (pin "13") (pinfunction "13_13") (pintype "passive"))
    )
    (net (code "61") (name "/2_AD2_IN3") (class "Default")
      (node (ref "IC2") (pin "42") (pinfunction "PA6_42") (pintype "passive"))
      (node (ref "P6") (pin "14") (pinfunction "14_14") (pintype "passive"))
    )
    (net (code "62") (name "/2_AD2_IN4") (class "Default")
      (node (ref "IC2") (pin "43") (pinfunction "PA7_43") (pintype "passive"))
      (node (ref "P6") (pin "15") (pinfunction "15_15") (pintype "passive"))
    )
    (net (code "63") (name "/2_AD2_IN5") (class "Default")
      (node (ref "IC2") (pin "44") (pinfunction "PC4_44") (pintype "passive"))
      (node (ref "P6") (pin "16") (pinfunction "16_16") (pintype "passive"))
    )
    (net (code "64") (name "/2_AD2_IN11") (class "Default")
      (node (ref "IC2") (pin "45") (pinfunction "PC5_45") (pintype "passive"))
      (node (ref "P6") (pin "17") (pinfunction "17_17") (pintype "passive"))
    )
    (net (code "65") (name "/2_AD2_IN12") (class "Default")
      (node (ref "IC2") (pin "48") (pinfunction "PB2_48") (pintype "passive"))
      (node (ref "P6") (pin "18") (pinfunction "18_18") (pintype "passive"))
    )
    (net (code "66") (name "/2_AD3_IN1") (class "Default")
      (node (ref "IC2") (pin "47") (pinfunction "PB1_47") (pintype "passive"))
      (node (ref "P6") (pin "19") (pinfunction "19_19") (pintype "passive"))
    )
    (net (code "67") (name "/2_AD3_IN2") (class "Default")
      (node (ref "IC2") (pin "60") (pinfunction "PE9_60") (pintype "passive"))
      (node (ref "P6") (pin "20") (pinfunction "20_20") (pintype "passive"))
    )
    (net (code "68") (name "/2_AD3_IN3") (class "Default")
      (node (ref "IC2") (pin "66") (pinfunction "PE13_66") (pintype "passive"))
      (node (ref "P7") (pin "1") (pinfunction "1_1") (pintype "passive"))
    )
    (net (code "69") (name "/2_AD3_IN5") (class "Default")
      (node (ref "IC2") (pin "74") (pinfunction "PB13_74") (pintype "passive"))
      (node (ref "P7") (pin "2") (pinfunction "2_2") (pintype "passive"))
    )
    (net (code "70") (name "/2_AD3_IN6") (class "Default")
      (node (ref "IC2") (pin "59") (pinfunction "PE8_59") (pintype "passive"))
      (node (ref "P7") (pin "3") (pinfunction "3_3") (pintype "passive"))
    )
    (net (code "71") (name "/2_AD3_IN7") (class "Default")
      (node (ref "IC2") (pin "79") (pinfunction "PD10_79") (pintype "passive"))
      (node (ref "P7") (pin "4") (pinfunction "4_4") (pintype "passive"))
    )
    (net (code "72") (name "/2_AD3_IN8") (class "Default")
      (node (ref "IC2") (pin "80") (pinfunction "PD11_80") (pintype "passive"))
      (node (ref "P7") (pin "5") (pinfunction "5_5") (pintype "passive"))
    )
    (net (code "73") (name "/2_AD3_IN9") (class "Default")
      (node (ref "IC2") (pin "81") (pinfunction "PD12_81") (pintype "passive"))
      (node (ref "P7") (pin "6") (pinfunction "6_6") (pintype "passive"))
    )
    (net (code "74") (name "/2_AD3_IN10") (class "Default")
      (node (ref "IC2") (pin "82") (pinfunction "PD13_82") (pintype "passive"))
      (node (ref "P7") (pin "7") (pinfunction "7_7") (pintype "passive"))
    )
    (net (code "75") (name "/2_AD3_IN11") (class "Default")
      (node (ref "IC2") (pin "85") (pinfunction "PD14_85") (pintype "passive"))
      (node (ref "P7") (pin "8") (pinfunction "8_8") (pintype "passive"))
    )
    (net (code "76") (name "/2_AD3_IN12") (class "Default")
      (node (ref "IC2") (pin "46") (pinfunction "PB0_46") (pintype "passive"))
      (node (ref "P7") (pin "9") (pinfunction "9_9") (pintype "passive"))
    )
    (net (code "77") (name "/2_AD3_IN13") (class "Default")
      (node (ref "IC2") (pin "58") (pinfunction "PE7_58") (pintype "passive"))
      (node (ref "P7") (pin "10") (pinfunction "10_10") (pintype "passive"))
    )
    (net (code "78") (name "/2_AD3_IN14") (class "Default")
      (node (ref "IC2") (pin "63") (pinfunction "PE10_63") (pintype "passive"))
      (node (ref "P7") (pin "11") (pinfunction "11_11") (pintype "passive"))
    )
    (net (code "79") (name "/2_AD3_IN15") (class "Default")
      (node (ref "IC2") (pin "64") (pinfunction "PE11_64") (pintype "passive"))
      (node (ref "P7") (pin "12") (pinfunction "12_12") (pintype "passive"))
    )
    (net (code "80") (name "/2_AD3_IN16") (class "Default")
      (node (ref "IC2") (pin "65") (pinfunction "PE12_65") (pintype "passive"))
      (node (ref "P7") (pin "13") (pinfunction "13_13") (pintype "passive"))
    )
    (net (code "81") (name "/2_AD4_IN1") (class "Default")
      (node (ref "IC2") (pin "67") (pinfunction "PE14_67") (pintype "passive"))
      (node (ref "P7") (pin "14") (pinfunction "14_14") (pintype "passive"))
    )
    (net (code "82") (name "/2_AD4_IN2") (class "Default")
      (node (ref "IC2") (pin "68") (pinfunction "PE15_68") (pintype "passive"))
      (node (ref "P7") (pin "15") (pinfunction "15_15") (pintype "passive"))
    )
    (net (code "83") (name "/2_AD4_IN3") (class "Default")
      (node (ref "IC2") (pin "73") (pinfunction "PB12_73") (pintype "passive"))
      (node (ref "P7") (pin "16") (pinfunction "16_16") (pintype "passive"))
    )
    (net (code "84") (name "/2_AD4_IN4") (class "Default")
      (node (ref "IC2") (pin "75") (pinfunction "PB14_75") (pintype "passive"))
      (node (ref "P7") (pin "17") (pinfunction "17_17") (pintype "passive"))
    )
    (net (code "85") (name "/2_AD4_IN5") (class "Default")
      (node (ref "IC2") (pin "76") (pinfunction "PB15_76") (pintype "passive"))
      (node (ref "P7") (pin "18") (pinfunction "18_18") (pintype "passive"))
    )
    (net (code "86") (name "/2_AD4_IN12") (class "Default")
      (node (ref "IC2") (pin "77") (pinfunction "PD8_77") (pintype "passive"))
      (node (ref "P7") (pin "19") (pinfunction "19_19") (pintype "passive"))
    )
    (net (code "87") (name "/2_AD4_IN13") (class "Default")
      (node (ref "IC2") (pin "78") (pinfunction "PD9_78") (pintype "passive"))
      (node (ref "P7") (pin "20") (pinfunction "20_20") (pintype "passive"))
    )
    (net (code "88") (name "/2_SPI_MISO") (class "Default")
      (node (ref "IC2") (pin "134") (pinfunction "PB4_134") (pintype "passive"))
      (node (ref "P1") (pin "11") (pinfunction "11_11") (pintype "passive"))
    )
    (net (code "89") (name "/2_SPI_MOSI") (class "Default")
      (node (ref "IC2") (pin "135") (pinfunction "PB5_135") (pintype "passive"))
      (node (ref "P1") (pin "13") (pinfunction "13_13") (pintype "passive"))
    )
    (net (code "90") (name "/2_SPI_SCK") (class "Default")
      (node (ref "IC2") (pin "133") (pinfunction "PB3_133") (pintype "passive"))
      (node (ref "P1") (pin "9") (pinfunction "9_9") (pintype "passive"))
    )
    (net (code "91") (name "/3_AD1_IN1") (class "Default")
      (node (ref "IC3") (pin "34") (pinfunction "PA0_34") (pintype "passive"))
      (node (ref "P8") (pin "1") (pinfunction "1_1") (pintype "passive"))
    )
    (net (code "92") (name "/3_AD1_IN2") (class "Default")
      (node (ref "IC3") (pin "35") (pinfunction "PA1_35") (pintype "passive"))
      (node (ref "P8") (pin "2") (pinfunction "2_2") (pintype "passive"))
    )
    (net (code "93") (name "/3_AD1_IN3") (class "Default")
      (node (ref "IC3") (pin "36") (pinfunction "PA2_36") (pintype "passive"))
      (node (ref "P8") (pin "3") (pinfunction "3_3") (pintype "passive"))
    )
    (net (code "94") (name "/3_AD1_IN4") (class "Default")
      (node (ref "IC3") (pin "37") (pinfunction "PA3_37") (pintype "passive"))
      (node (ref "P8") (pin "4") (pinfunction "4_4") (pintype "passive"))
    )
    (net (code "95") (name "/3_AD1_IN5") (class "Default")
      (node (ref "IC3") (pin "14") (pinfunction "PF4_14") (pintype "passive"))
      (node (ref "P8") (pin "5") (pinfunction "5_5") (pintype "passive"))
    )
    (net (code "96") (name "/3_AD1_IN6") (class "Default")
      (node (ref "IC3") (pin "26") (pinfunction "PC0_26") (pintype "passive"))
      (node (ref "P8") (pin "6") (pinfunction "6_6") (pintype "passive"))
    )
    (net (code "97") (name "/3_AD1_IN7") (class "Default")
      (node (ref "IC3") (pin "27") (pinfunction "PC1_27") (pintype "passive"))
      (node (ref "P8") (pin "7") (pinfunction "7_7") (pintype "passive"))
    )
    (net (code "98") (name "/3_AD1_IN8") (class "Default")
      (node (ref "IC3") (pin "28") (pinfunction "PC2_28") (pintype "passive"))
      (node (ref "P8") (pin "8") (pinfunction "8_8") (pintype "passive"))
    )
    (net (code "99") (name "/3_AD1_IN9") (class "Default")
      (node (ref "IC3") (pin "29") (pinfunction "PC3_29") (pintype "passive"))
      (node (ref "P8") (pin "9") (pinfunction "9_9") (pintype "passive"))
    )
    (net (code "100") (name "/3_AD1_IN10") (class "Default")
      (node (ref "IC3") (pin "12") (pinfunction "PF2_12") (pintype "passive"))
      (node (ref "P8") (pin "10") (pinfunction "10_10") (pintype "passive"))
    )
    (net (code "101") (name "/3_AD1_IN14") (class "Default")
      (node (ref "IC3") (pin "70") (pinfunction "PB11_70") (pintype "passive"))
      (node (ref "P8") (pin "11") (pinfunction "11_11") (pintype "passive"))
    )
    (net (code "102") (name "/3_AD2_IN1") (class "Default")
      (node (ref "IC3") (pin "40") (pinfunction "PA4_40") (pintype "passive"))
      (node (ref "P8") (pin "12") (pinfunction "12_12") (pintype "passive"))
    )
    (net (code "103") (name "/3_AD2_IN2") (class "Default")
      (node (ref "IC3") (pin "41") (pinfunction "PA5_41") (pintype "passive"))
      (node (ref "P8") (pin "13") (pinfunction "13_13") (pintype "passive"))
    )
    (net (code "104") (name "/3_AD2_IN3") (class "Default")
      (node (ref "IC3") (pin "42") (pinfunction "PA6_42") (pintype "passive"))
      (node (ref "P8") (pin "14") (pinfunction "14_14") (pintype "passive"))
    )
    (net (code "105") (name "/3_AD2_IN4") (class "Default")
      (node (ref "IC3") (pin "43") (pinfunction "PA7_43") (pintype "passive"))
      (node (ref "P8") (pin "15") (pinfunction "15_15") (pintype "passive"))
    )
    (net (code "106") (name "/3_AD2_IN5") (class "Default")
      (node (ref "IC3") (pin "44") (pinfunction "PC4_44") (pintype "passive"))
      (node (ref "P8") (pin "16") (pinfunction "16_16") (pintype "passive"))
    )
    (net (code "107") (name "/3_AD2_IN11") (class "Default")
      (node (ref "IC3") (pin "45") (pinfunction "PC5_45") (pintype "passive"))
      (node (ref "P8") (pin "17") (pinfunction "17_17") (pintype "passive"))
    )
    (net (code "108") (name "/3_AD2_IN12") (class "Default")
      (node (ref "IC3") (pin "48") (pinfunction "PB2_48") (pintype "passive"))
      (node (ref "P8") (pin "18") (pinfunction "18_18") (pintype "passive"))
    )
    (net (code "109") (name "/3_AD3_IN1") (class "Default")
      (node (ref "IC3") (pin "47") (pinfunction "PB1_47") (pintype "passive"))
      (node (ref "P8") (pin "19") (pinfunction "19_19") (pintype "passive"))
    )
    (net (code "110") (name "/3_AD3_IN2") (class "Default")
      (node (ref "IC3") (pin "60") (pinfunction "PE9_60") (pintype "passive"))
      (node (ref "P8") (pin "20") (pinfunction "20_20") (pintype "passive"))
    )
    (net (code "111") (name "/3_AD3_IN3") (class "Default")
      (node (ref "IC3") (pin "66") (pinfunction "PE13_66") (pintype "passive"))
      (node (ref "P9") (pin "1") (pinfunction "1_1") (pintype "passive"))
    )
    (net (code "112") (name "/3_AD3_IN5") (class "Default")
      (node (ref "IC3") (pin "74") (pinfunction "PB13_74") (pintype "passive"))
      (node (ref "P9") (pin "2") (pinfunction "2_2") (pintype "passive"))
    )
    (net (code "113") (name "/3_AD3_IN6") (class "Default")
      (node (ref "IC3") (pin "59") (pinfunction "PE8_59") (pintype "passive"))
      (node (ref "P9") (pin "3") (pinfunction "3_3") (pintype "passive"))
    )
    (net (code "114") (name "/3_AD3_IN7") (class "Default")
      (node (ref "IC3") (pin "79") (pinfunction "PD10_79") (pintype "passive"))
      (node (ref "P9") (pin "4") (pinfunction "4_4") (pintype "passive"))
    )
    (net (code "115") (name "/3_AD3_IN8") (class "Default")
      (node (ref "IC3") (pin "80") (pinfunction "PD11_80") (pintype "passive"))
      (node (ref "P9") (pin "5") (pinfunction "5_5") (pintype "passive"))
    )
    (net (code "116") (name "/3_AD3_IN9") (class "Default")
      (node (ref "IC3") (pin "81") (pinfunction "PD12_81") (pintype "passive"))
      (node (ref "P9") (pin "6") (pinfunction "6_6") (pintype "passive"))
    )
    (net (code "117") (name "/3_AD3_IN10") (class "Default")
      (node (ref "IC3") (pin "82") (pinfunction "PD13_82") (pintype "passive"))
      (node (ref "P9") (pin "7") (pinfunction "7_7") (pintype "passive"))
    )
    (net (code "118") (name "/3_AD3_IN11") (class "Default")
      (node (ref "IC3") (pin "85") (pinfunction "PD14_85") (pintype "passive"))
      (node (ref "P9") (pin "8") (pinfunction "8_8") (pintype "passive"))
    )
    (net (code "119") (name "/3_AD3_IN12") (class "Default")
      (node (ref "IC3") (pin "46") (pinfunction "PB0_46") (pintype "passive"))
      (node (ref "P9") (pin "9") (pinfunction "9_9") (pintype "passive"))
    )
    (net (code "120") (name "/3_AD3_IN13") (class "Default")
      (node (ref "IC3") (pin "58") (pinfunction "PE7_58") (pintype "passive"))
      (node (ref "P9") (pin "10") (pinfunction "10_10") (pintype "passive"))
    )
    (net (code "121") (name "/3_AD3_IN14") (class "Default")
      (node (ref "IC3") (pin "63") (pinfunction "PE10_63") (pintype "passive"))
      (node (ref "P9") (pin "11") (pinfunction "11_11") (pintype "passive"))
    )
    (net (code "122") (name "/3_AD3_IN15") (class "Default")
      (node (ref "IC3") (pin "64") (pinfunction "PE11_64") (pintype "passive"))
      (node (ref "P9") (pin "12") (pinfunction "12_12") (pintype "passive"))
    )
    (net (code "123") (name "/3_AD3_IN16") (class "Default")
      (node (ref "IC3") (pin "65") (pinfunction "PE12_65") (pintype "passive"))
      (node (ref "P9") (pin "13") (pinfunction "13_13") (pintype "passive"))
    )
    (net (code "124") (name "/3_AD4_IN1") (class "Default")
      (node (ref "IC3") (pin "67") (pinfunction "PE14_67") (pintype "passive"))
      (node (ref "P9") (pin "14") (pinfunction "14_14") (pintype "passive"))
    )
    (net (code "125") (name "/3_AD4_IN2") (class "Default")
      (node (ref "IC3") (pin "68") (pinfunction "PE15_68") (pintype "passive"))
      (node (ref "P9") (pin "15") (pinfunction "15_15") (pintype "passive"))
    )
    (net (code "126") (name "/3_AD4_IN3") (class "Default")
      (node (ref "IC3") (pin "73") (pinfunction "PB12_73") (pintype "passive"))
      (node (ref "P9") (pin "16") (pinfunction "16_16") (pintype "passive"))
    )
    (net (code "127") (name "/3_AD4_IN4") (class "Default")
      (node (ref "IC3") (pin "75") (pinfunction "PB14_75") (pintype "passive"))
      (node (ref "P9") (pin "17") (pinfunction "17_17") (pintype "passive"))
    )
    (net (code "128") (name "/3_AD4_IN5") (class "Default")
      (node (ref "IC3") (pin "76") (pinfunction "PB15_76") (pintype "passive"))
      (node (ref "P9") (pin "18") (pinfunction "18_18") (pintype "passive"))
    )
    (net (code "129") (name "/3_AD4_IN12") (class "Default")
      (node (ref "IC3") (pin "77") (pinfunction "PD8_77") (pintype "passive"))
      (node (ref "P9") (pin "19") (pinfunction "19_19") (pintype "passive"))
    )
    (net (code "130") (name "/3_AD4_IN13") (class "Default")
      (node (ref "IC3") (pin "78") (pinfunction "PD9_78") (pintype "passive"))
      (node (ref "P9") (pin "20") (pinfunction "20_20") (pintype "passive"))
    )
    (net (code "131") (name "/3_SPI_MISO") (class "Default")
      (node (ref "IC3") (pin "134") (pinfunction "PB4_134") (pintype "passive"))
      (node (ref "P1") (pin "19") (pinfunction "19_19") (pintype "passive"))
    )
    (net (code "132") (name "/3_SPI_MOSI") (class "Default")
      (node (ref "IC3") (pin "135") (pinfunction "PB5_135") (pintype "passive"))
      (node (ref "P1") (pin "20") (pinfunction "20_20") (pintype "passive"))
    )
    (net (code "133") (name "/3_SPI_SCK") (class "Default")
      (node (ref "IC3") (pin "133") (pinfunction "PB3_133") (pintype "passive"))
      (node (ref "P1") (pin "17") (pinfunction "17_17") (pintype "passive"))
    )
    (net (code "134") (name "/4_AD1_IN1") (class "Default")
      (node (ref "IC4") (pin "34") (pinfunction "PA0_34") (pintype "passive"))
      (node (ref "P10") (pin "1") (pinfunction "1_1") (pintype "passive"))
    )
    (net (code "135") (name "/4_AD1_IN2") (class "Default")
      (node (ref "IC4") (pin "35") (pinfunction "PA1_35") (pintype "passive"))
      (node (ref "P10") (pin "2") (pinfunction "2_2") (pintype "passive"))
    )
    (net (code "136") (name "/4_AD1_IN3") (class "Default")
      (node (ref "IC4") (pin "36") (pinfunction "PA2_36") (pintype "passive"))
      (node (ref "P10") (pin "3") (pinfunction "3_3") (pintype "passive"))
    )
    (net (code "137") (name "/4_AD1_IN4") (class "Default")
      (node (ref "IC4") (pin "37") (pinfunction "PA3_37") (pintype "passive"))
      (node (ref "P10") (pin "4") (pinfunction "4_4") (pintype "passive"))
    )
    (net (code "138") (name "/4_AD1_IN5") (class "Default")
      (node (ref "IC4") (pin "14") (pinfunction "PF4_14") (pintype "passive"))
      (node (ref "P10") (pin "5") (pinfunction "5_5") (pintype "passive"))
    )
    (net (code "139") (name "/4_AD1_IN6") (class "Default")
      (node (ref "IC4") (pin "26") (pinfunction "PC0_26") (pintype "passive"))
      (node (ref "P10") (pin "6") (pinfunction "6_6") (pintype "passive"))
    )
    (net (code "140") (name "/4_AD1_IN7") (class "Default")
      (node (ref "IC4") (pin "27") (pinfunction "PC1_27") (pintype "passive"))
      (node (ref "P10") (pin "7") (pinfunction "7_7") (pintype "passive"))
    )
    (net (code "141") (name "/4_AD1_IN8") (class "Default")
      (node (ref "IC4") (pin "28") (pinfunction "PC2_28") (pintype "passive"))
      (node (ref "P10") (pin "8") (pinfunction "8_8") (pintype "passive"))
    )
    (net (code "142") (name "/4_AD1_IN9") (class "Default")
      (node (ref "IC4") (pin "29") (pinfunction "PC3_29") (pintype "passive"))
      (node (ref "P10") (pin "9") (pinfunction "9_9") (pintype "passive"))
    )
    (net (code "143") (name "/4_AD1_IN10") (class "Default")
      (node (ref "IC4") (pin "12") (pinfunction "PF2_12") (pintype "passive"))
      (node (ref "P10") (pin "10") (pinfunction "10_10") (pintype "passive"))
    )
    (net (code "144") (name "/4_AD1_IN14") (class "Default")
      (node (ref "IC4") (pin "70") (pinfunction "PB11_70") (pintype "passive"))
      (node (ref "P10") (pin "11") (pinfunction "11_11") (pintype "passive"))
    )
    (net (code "145") (name "/4_AD2_IN1") (class "Default")
      (node (ref "IC4") (pin "40") (pinfunction "PA4_40") (pintype "passive"))
      (node (ref "P10") (pin "12") (pinfunction "12_12") (pintype "passive"))
    )
    (net (code "146") (name "/4_AD2_IN2") (class "Default")
      (node (ref "IC4") (pin "41") (pinfunction "PA5_41") (pintype "passive"))
      (node (ref "P10") (pin "13") (pinfunction "13_13") (pintype "passive"))
    )
    (net (code "147") (name "/4_AD2_IN3") (class "Default")
      (node (ref "IC4") (pin "42") (pinfunction "PA6_42") (pintype "passive"))
      (node (ref "P10") (pin "14") (pinfunction "14_14") (pintype "passive"))
    )
    (net (code "148") (name "/4_AD2_IN4") (class "Default")
      (node (ref "IC4") (pin "43") (pinfunction "PA7_43") (pintype "passive"))
      (node (ref "P10") (pin "15") (pinfunction "15_15") (pintype "passive"))
    )
    (net (code "149") (name "/4_AD2_IN5") (class "Default")
      (node (ref "IC4") (pin "44") (pinfunction "PC4_44") (pintype "passive"))
      (node (ref "P10") (pin "16") (pinfunction "16_16") (pintype "passive"))
    )
    (net (code "150") (name "/4_AD2_IN11") (class "Default")
      (node (ref "IC4") (pin "45") (pinfunction "PC5_45") (pintype "passive"))
      (node (ref "P10") (pin "17") (pinfunction "17_17") (pintype "passive"))
    )
    (net (code "151") (name "/4_AD2_IN12") (class "Default")
      (node (ref "IC4") (pin "48") (pinfunction "PB2_48") (pintype "passive"))
      (node (ref "P10") (pin "18") (pinfunction "18_18") (pintype "passive"))
    )
    (net (code "152") (name "/4_AD3_IN1") (class "Default")
      (node (ref "IC4") (pin "47") (pinfunction "PB1_47") (pintype "passive"))
      (node (ref "P10") (pin "19") (pinfunction "19_19") (pintype "passive"))
    )
    (net (code "153") (name "/4_AD3_IN2") (class "Default")
      (node (ref "IC4") (pin "60") (pinfunction "PE9_60") (pintype "passive"))
      (node (ref "P10") (pin "20") (pinfunction "20_20") (pintype "passive"))
    )
    (net (code "154") (name "/4_AD3_IN3") (class "Default")
      (node (ref "IC4") (pin "66") (pinfunction "PE13_66") (pintype "passive"))
      (node (ref "P11") (pin "1") (pinfunction "1_1") (pintype "passive"))
    )
    (net (code "155") (name "/4_AD3_IN5") (class "Default")
      (node (ref "IC4") (pin "74") (pinfunction "PB13_74") (pintype "passive"))
      (node (ref "P11") (pin "2") (pinfunction "2_2") (pintype "passive"))
    )
    (net (code "156") (name "/4_AD3_IN6") (class "Default")
      (node (ref "IC4") (pin "59") (pinfunction "PE8_59") (pintype "passive"))
      (node (ref "P11") (pin "3") (pinfunction "3_3") (pintype "passive"))
    )
    (net (code "157") (name "/4_AD3_IN7") (class "Default")
      (node (ref "IC4") (pin "79") (pinfunction "PD10_79") (pintype "passive"))
      (node (ref "P11") (pin "4") (pinfunction "4_4") (pintype "passive"))
    )
    (net (code "158") (name "/4_AD3_IN8") (class "Default")
      (node (ref "IC4") (pin "80") (pinfunction "PD11_80") (pintype "passive"))
      (node (ref "P11") (pin "5") (pinfunction "5_5") (pintype "passive"))
    )
    (net (code "159") (name "/4_AD3_IN9") (class "Default")
      (node (ref "IC4") (pin "81") (pinfunction "PD12_81") (pintype "passive"))
      (node (ref "P11") (pin "6") (pinfunction "6_6") (pintype "passive"))
    )
    (net (code "160") (name "/4_AD3_IN10") (class "Default")
      (node (ref "IC4") (pin "82") (pinfunction "PD13_82") (pintype "passive"))
      (node (ref "P11") (pin "7") (pinfunction "7_7") (pintype "passive"))
    )
    (net (code "161") (name "/4_AD3_IN11") (class "Default")
      (node (ref "IC4") (pin "85") (pinfunction "PD14_85") (pintype "passive"))
      (node (ref "P11") (pin "8") (pinfunction "8_8") (pintype "passive"))
    )
    (net (code "162") (name "/4_AD3_IN12") (class "Default")
      (node (ref "IC4") (pin "46") (pinfunction "PB0_46") (pintype "passive"))
      (node (ref "P11") (pin "9") (pinfunction "9_9") (pintype "passive"))
    )
    (net (code "163") (name "/4_AD3_IN13") (class "Default")
      (node (ref "IC4") (pin "58") (pinfunction "PE7_58") (pintype "passive"))
      (node (ref "P11") (pin "10") (pinfunction "10_10") (pintype "passive"))
    )
    (net (code "164") (name "/4_AD3_IN14") (class "Default")
      (node (ref "IC4") (pin "63") (pinfunction "PE10_63") (pintype "passive"))
      (node (ref "P11") (pin "11") (pinfunction "11_11") (pintype "passive"))
    )
    (net (code "165") (name "/4_AD3_IN15") (class "Default")
      (node (ref "IC4") (pin "64") (pinfunction "PE11_64") (pintype "passive"))
      (node (ref "P11") (pin "12") (pinfunction "12_12") (pintype "passive"))
    )
    (net (code "166") (name "/4_AD3_IN16") (class "Default")
      (node (ref "IC4") (pin "65") (pinfunction "PE12_65") (pintype "passive"))
      (node (ref "P11") (pin "13") (pinfunction "13_13") (pintype "passive"))
    )
    (net (code "167") (name "/4_AD4_IN1") (class "Default")
      (node (ref "IC4") (pin "67") (pinfunction "PE14_67") (pintype "passive"))
      (node (ref "P11") (pin "14") (pinfunction "14_14") (pintype "passive"))
    )
    (net (code "168") (name "/4_AD4_IN2") (class "Default")
      (node (ref "IC4") (pin "68") (pinfunction "PE15_68") (pintype "passive"))
      (node (ref "P11") (pin "15") (pinfunction "15_15") (pintype "passive"))
    )
    (net (code "169") (name "/4_AD4_IN3") (class "Default")
      (node (ref "IC4") (pin "73") (pinfunction "PB12_73") (pintype "passive"))
      (node (ref "P11") (pin "16") (pinfunction "16_16") (pintype "passive"))
    )
    (net (code "170") (name "/4_AD4_IN4") (class "Default")
      (node (ref "IC4") (pin "75") (pinfunction "PB14_75") (pintype "passive"))
      (node (ref "P11") (pin "17") (pinfunction "17_17") (pintype "passive"))
    )
    (net (code "171") (name "/4_AD4_IN5") (class "Default")
      (node (ref "IC4") (pin "76") (pinfunction "PB15_76") (pintype "passive"))
      (node (ref "P11") (pin "18") (pinfunction "18_18") (pintype "passive"))
    )
    (net (code "172") (name "/4_AD4_IN12") (class "Default")
      (node (ref "IC4") (pin "77") (pinfunction "PD8_77") (pintype "passive"))
      (node (ref "P11") (pin "19") (pinfunction "19_19") (pintype "passive"))
    )
    (net (code "173") (name "/4_AD4_IN13") (class "Default")
      (node (ref "IC4") (pin "78") (pinfunction "PD9_78") (pintype "passive"))
      (node (ref "P11") (pin "20") (pinfunction "20_20") (pintype "passive"))
    )
    (net (code "174") (name "/4_SPI_MISO") (class "Default")
      (node (ref "IC4") (pin "134") (pinfunction "PB4_134") (pintype "passive"))
      (node (ref "P1") (pin "14") (pinfunction "14_14") (pintype "passive"))
    )
    (net (code "175") (name "/4_SPI_MOSI") (class "Default")
      (node (ref "IC4") (pin "135") (pinfunction "PB5_135") (pintype "passive"))
      (node (ref "P1") (pin "16") (pinfunction "16_16") (pintype "passive"))
    )
    (net (code "176") (name "/4_SPI_SCK") (class "Default")
      (node (ref "IC4") (pin "133") (pinfunction "PB3_133") (pintype "passive"))
      (node (ref "P1") (pin "12") (pinfunction "12_12") (pintype "passive"))
    )
    (net (code "177") (name "/5_AD1_IN1") (class "Default")
      (node (ref "IC5") (pin "34") (pinfunction "PA0_34") (pintype "passive"))
      (node (ref "P12") (pin "1") (pinfunction "1_1") (pintype "passive"))
    )
    (net (code "178") (name "/5_AD1_IN2") (class "Default")
      (node (ref "IC5") (pin "35") (pinfunction "PA1_35") (pintype "passive"))
      (node (ref "P12") (pin "2") (pinfunction "2_2") (pintype "passive"))
    )
    (net (code "179") (name "/5_AD1_IN3") (class "Default")
      (node (ref "IC5") (pin "36") (pinfunction "PA2_36") (pintype "passive"))
      (node (ref "P12") (pin "3") (pinfunction "3_3") (pintype "passive"))
    )
    (net (code "180") (name "/5_AD1_IN4") (class "Default")
      (node (ref "IC5") (pin "37") (pinfunction "PA3_37") (pintype "passive"))
      (node (ref "P12") (pin "4") (pinfunction "4_4") (pintype "passive"))
    )
    (net (code "181") (name "/5_AD1_IN5") (class "Default")
      (node (ref "IC5") (pin "14") (pinfunction "PF4_14") (pintype "passive"))
      (node (ref "P12") (pin "5") (pinfunction "5_5") (pintype "passive"))
    )
    (net (code "182") (name "/5_AD1_IN6") (class "Default")
      (node (ref "IC5") (pin "26") (pinfunction "PC0_26") (pintype "passive"))
      (node (ref "P12") (pin "6") (pinfunction "6_6") (pintype "passive"))
    )
    (net (code "183") (name "/5_AD1_IN7") (class "Default")
      (node (ref "IC5") (pin "27") (pinfunction "PC1_27") (pintype "passive"))
      (node (ref "P12") (pin "7") (pinfunction "7_7") (pintype "passive"))
    )
    (net (code "184") (name "/5_AD1_IN8") (class "Default")
      (node (ref "IC5") (pin "28") (pinfunction "PC2_28") (pintype "passive"))
      (node (ref "P12") (pin "8") (pinfunction "8_8") (pintype "passive"))
    )
    (net (code "185") (name "/5_AD1_IN9") (class "Default")
      (node (ref "IC5") (pin "29") (pinfunction "PC3_29") (pintype "passive"))
      (node (ref "P12") (pin "9") (pinfunction "9_9") (pintype "passive"))
    )
    (net (code "186") (name "/5_AD1_IN10") (class "Default")
      (node (ref "IC5") (pin "12") (pinfunction "PF2_12") (pintype "passive"))
      (node (ref "P12") (pin "10") (pinfunction "10_10") (pintype "passive"))
    )
    (net (code "187") (name "/5_AD1_IN14") (class "Default")
      (node (ref "IC5") (pin "70") (pinfunction "PB11_70") (pintype "passive"))
      (node (ref "P12") (pin "11") (pinfunction "11_11") (pintype "passive"))
    )
    (net (code "188") (name "/5_AD2_IN1") (class "Default")
      (node (ref "IC5") (pin "40") (pinfunction "PA4_40") (pintype "passive"))
      (node (ref "P12") (pin "12") (pinfunction "12_12") (pintype "passive"))
    )
    (net (code "189") (name "/5_AD2_IN2") (class "Default")
      (node (ref "IC5") (pin "41") (pinfunction "PA5_41") (pintype "passive"))
      (node (ref "P12") (pin "13") (pinfunction "13_13") (pintype "passive"))
    )
    (net (code "190") (name "/5_AD2_IN3") (class "Default")
      (node (ref "IC5") (pin "42") (pinfunction "PA6_42") (pintype "passive"))
      (node (ref "P12") (pin "14") (pinfunction "14_14") (pintype "passive"))
    )
    (net (code "191") (name "/5_AD2_IN4") (class "Default")
      (node (ref "IC5") (pin "43") (pinfunction "PA7_43") (pintype "passive"))
      (node (ref "P12") (pin "15") (pinfunction "15_15") (pintype "passive"))
    )
    (net (code "192") (name "/5_AD2_IN5") (class "Default")
      (node (ref "IC5") (pin "44") (pinfunction "PC4_44") (pintype "passive"))
      (node (ref "P12") (pin "16") (pinfunction "16_16") (pintype "passive"))
    )
    (net (code "193") (name "/5_AD2_IN11") (class "Default")
      (node (ref "IC5") (pin "45") (pinfunction "PC5_45") (pintype "passive"))
      (node (ref "P12") (pin "17") (pinfunction "17_17") (pintype "passive"))
    )
    (net (code "194") (name "/5_AD2_IN12") (class "Default")
      (node (ref "IC5") (pin "48") (pinfunction "PB2_48") (pintype "passive"))
      (node (ref "P12") (pin "18") (pinfunction "18_18") (pintype "passive"))
    )
    (net (code "195") (name "/5_AD3_IN1") (class "Default")
      (node (ref "IC5") (pin "47") (pinfunction "PB1_47") (pintype "passive"))
      (node (ref "P12") (pin "19") (pinfunction "19_19") (pintype "passive"))
    )
    (net (code "196") (name "/5_AD3_IN2") (class "Default")
      (node (ref "IC5") (pin "60") (pinfunction "PE9_60") (pintype "passive"))
      (node (ref "P12") (pin "20") (pinfunction "20_20") (pintype "passive"))
    )
    (net (code "197") (name "/5_AD3_IN3") (class "Default")
      (node (ref "IC5") (pin "66") (pinfunction "PE13_66") (pintype "passive"))
      (node (ref "P13") (pin "1") (pinfunction "1_1") (pintype "passive"))
    )
    (net (code "198") (name "/5_AD3_IN5") (class "Default")
      (node (ref "IC5") (pin "74") (pinfunction "PB13_74") (pintype "passive"))
      (node (ref "P13") (pin "2") (pinfunction "2_2") (pintype "passive"))
    )
    (net (code "199") (name "/5_AD3_IN6") (class "Default")
      (node (ref "IC5") (pin "59") (pinfunction "PE8_59") (pintype "passive"))
      (node (ref "P13") (pin "3") (pinfunction "3_3") (pintype "passive"))
    )
    (net (code "200") (name "/5_AD3_IN7") (class "Default")
      (node (ref "IC5") (pin "79") (pinfunction "PD10_79") (pintype "passive"))
      (node (ref "P13") (pin "4") (pinfunction "4_4") (pintype "passive"))
    )
    (net (code "201") (name "/5_AD3_IN8") (class "Default")
      (node (ref "IC5") (pin "80") (pinfunction "PD11_80") (pintype "passive"))
      (node (ref "P13") (pin "5") (pinfunction "5_5") (pintype "passive"))
    )
    (net (code "202") (name "/5_AD3_IN9") (class "Default")
      (node (ref "IC5") (pin "81") (pinfunction "PD12_81") (pintype "passive"))
      (node (ref "P13") (pin "6") (pinfunction "6_6") (pintype "passive"))
    )
    (net (code "203") (name "/5_AD3_IN10") (class "Default")
      (node (ref "IC5") (pin "82") (pinfunction "PD13_82") (pintype "passive"))
      (node (ref "P13") (pin "7") (pinfunction "7_7") (pintype "passive"))
    )
    (net (code "204") (name "/5_AD3_IN11") (class "Default")
      (node (ref "IC5") (pin "85") (pinfunction "PD14_85") (pintype "passive"))
      (node (ref "P13") (pin "8") (pinfunction "8_8") (pintype "passive"))
    )
    (net (code "205") (name "/5_AD3_IN12") (class "Default")
      (node (ref "IC5") (pin "46") (pinfunction "PB0_46") (pintype "passive"))
      (node (ref "P13") (pin "9") (pinfunction "9_9") (pintype "passive"))
    )
    (net (code "206") (name "/5_AD3_IN13") (class "Default")
      (node (ref "IC5") (pin "58") (pinfunction "PE7_58") (pintype "passive"))
      (node (ref "P13") (pin "10") (pinfunction "10_10") (pintype "passive"))
    )
    (net (code "207") (name "/5_AD3_IN14") (class "Default")
      (node (ref "IC5") (pin "63") (pinfunction "PE10_63") (pintype "passive"))
      (node (ref "P13") (pin "11") (pinfunction "11_11") (pintype "passive"))
    )
    (net (code "208") (name "/5_AD3_IN15") (class "Default")
      (node (ref "IC5") (pin "64") (pinfunction "PE11_64") (pintype "passive"))
      (node (ref "P13") (pin "12") (pinfunction "12_12") (pintype "passive"))
    )
    (net (code "209") (name "/5_AD3_IN16") (class "Default")
      (node (ref "IC5") (pin "65") (pinfunction "PE12_65") (pintype "passive"))
      (node (ref "P13") (pin "13") (pinfunction "13_13") (pintype "passive"))
    )
    (net (code "210") (name "/5_AD4_IN1") (class "Default")
      (node (ref "IC5") (pin "67") (pinfunction "PE14_67") (pintype "passive"))
      (node (ref "P13") (pin "14") (pinfunction "14_14") (pintype "passive"))
    )
    (net (code "211") (name "/5_AD4_IN2") (class "Default")
      (node (ref "IC5") (pin "68") (pinfunction "PE15_68") (pintype "passive"))
      (node (ref "P13") (pin "15") (pinfunction "15_15") (pintype "passive"))
    )
    (net (code "212") (name "/5_AD4_IN3") (class "Default")
      (node (ref "IC5") (pin "73") (pinfunction "PB12_73") (pintype "passive"))
      (node (ref "P13") (pin "16") (pinfunction "16_16") (pintype "passive"))
    )
    (net (code "213") (name "/5_AD4_IN4") (class "Default")
      (node (ref "IC5") (pin "75") (pinfunction "PB14_75") (pintype "passive"))
      (node (ref "P13") (pin "17") (pinfunction "17_17") (pintype "passive"))
    )
    (net (code "214") (name "/5_AD4_IN5") (class "Default")
      (node (ref "IC5") (pin "76") (pinfunction "PB15_76") (pintype "passive"))
      (node (ref "P13") (pin "18") (pinfunction "18_18") (pintype "passive"))
    )
    (net (code "215") (name "/5_AD4_IN12") (class "Default")
      (node (ref "IC5") (pin "77") (pinfunction "PD8_77") (pintype "passive"))
      (node (ref "P13") (pin "19") (pinfunction "19_19") (pintype "passive"))
    )
    (net (code "216") (name "/5_AD4_IN13") (class "Default")
      (node (ref "IC5") (pin "78") (pinfunction "PD9_78") (pintype "passive"))
      (node (ref "P13") (pin "20") (pinfunction "20_20") (pintype "passive"))
    )
    (net (code "217") (name "/5_SPI_MISO") (class "Default")
      (node (ref "IC5") (pin "134") (pinfunction "PB4_134") (pintype "passive"))
      (node (ref "P1") (pin "6") (pinfunction "6_6") (pintype "passive"))
    )
    (net (code "218") (name "/5_SPI_MOSI") (class "Default")
      (node (ref "IC5") (pin "135") (pinfunction "PB5_135") (pintype "passive"))
      (node (ref "P1") (pin "8") (pinfunction "8_8") (pintype "passive"))
    )
    (net (code "219") (name "/5_SPI_SCK") (class "Default")
      (node (ref "IC5") (pin "133") (pinfunction "PB3_133") (pintype "passive"))
      (node (ref "P1") (pin "4") (pinfunction "4_4") (pintype "passive"))
    )
    (net (code "220") (name "3.3V") (class "Default")
      (node (ref "C11") (pin "1") (pinfunction "1_1") (pintype "passive"))
      (node (ref "C12") (pin "1") (pinfunction "1_1") (pintype "passive"))
      (node (ref "C13") (pin "1") (pinfunction "1_1") (pintype "passive"))
      (node (ref "C14") (pin "1") (pinfunction "1_1") (pintype "passive"))
      (node (ref "C15") (pin "1") (pinfunction "1_1") (pintype "passive"))
      (node (ref "C16") (pin "1") (pinfunction "1_1") (pintype "passive"))
      (node (ref "C17") (pin "1") (pinfunction "1_1") (pintype "passive"))
      (node (ref "C18") (pin "1") (pinfunction "1_1") (pintype "passive"))
      (node (ref "C19") (pin "1") (pinfunction "1_1") (pintype "passive"))
      (node (ref "C20") (pin "1") (pinfunction "1_1") (pintype "passive"))
      (node (ref "C21") (pin "1") (pinfunction "1_1") (pintype "passive"))
      (node (ref "C22") (pin "1") (pinfunction "1_1") (pintype "passive"))
      (node (ref "C23") (pin "1") (pinfunction "1_1") (pintype "passive"))
      (node (ref "C24") (pin "1") (pinfunction "1_1") (pintype "passive"))
      (node (ref "C25") (pin "1") (pinfunction "1_1") (pintype "passive"))
      (node (ref "C26") (pin "1") (pinfunction "1_1") (pintype "passive"))
      (node (ref "C27") (pin "1") (pinfunction "1_1") (pintype "passive"))
      (node (ref "C28") (pin "1") (pinfunction "1_1") (pintype "passive"))
      (node (ref "C29") (pin "1") (pinfunction "1_1") (pintype "passive"))
      (node (ref "C30") (pin "1") (pinfunction "1_1") (pintype "passive"))
      (node (ref "C31") (pin "1") (pinfunction "1_1") (pintype "passive"))
      (node (ref "C32") (pin "1") (pinfunction "1_1") (pintype "passive"))
      (node (ref "C33") (pin "1") (pinfunction "1_1") (pintype "passive"))
      (node (ref "C34") (pin "1") (pinfunction "1_1") (pintype "passive"))
      (node (ref "C35") (pin "1") (pinfunction "1_1") (pintype "passive"))
      (node (ref "C36") (pin "1") (pinfunction "1_1") (pintype "passive"))
      (node (ref "C37") (pin "1") (pinfunction "1_1") (pintype "passive"))
      (node (ref "C38") (pin "1") (pinfunction "1_1") (pintype "passive"))
      (node (ref "C39") (pin "1") (pinfunction "1_1") (pintype "passive"))
      (node (ref "C40") (pin "1") (pinfunction "1_1") (pintype "passive"))
      (node (ref "C41") (pin "1") (pinfunction "1_1") (pintype "passive"))
      (node (ref "C42") (pin "1") (pinfunction "1_1") (pintype "passive"))
      (node (ref "C43") (pin "1") (pinfunction "1_1") (pintype "passive"))
      (node (ref "C44") (pin "1") (pinfunction "1_1") (pintype "passive"))
      (node (ref "C45") (pin "1") (pinfunction "1_1") (pintype "passive"))
      (node (ref "C46") (pin "1") (pinfunction "1_1") (pintype "passive"))
      (node (ref "C47") (pin "1") (pinfunction "1_1") (pintype "passive"))
      (node (ref "C48") (pin "1") (pinfunction "1_1") (pintype "passive"))
      (node (ref "C49") (pin "1") (pinfunction "1_1") (pintype "passive"))
      (node (ref "C50") (pin "1") (pinfunction "1_1") (pintype "passive"))
      (node (ref "C51") (pin "1") (pinfunction "1_1") (pintype "passive"))
      (node (ref "C52") (pin "1") (pinfunction "1_1") (pintype "passive"))
      (node (ref "C53") (pin "1") (pinfunction "1_1") (pintype "passive"))
      (node (ref "C54") (pin "1") (pinfunction "1_1") (pintype "passive"))
      (node (ref "C55") (pin "1") (pinfunction "1_1") (pintype "passive"))
      (node (ref "C56") (pin "1") (pinfunction "1_1") (pintype "passive"))
      (node (ref "C57") (pin "1") (pinfunction "1_1") (pintype "passive"))
      (node (ref "C58") (pin "1") (pinfunction "1_1") (pintype "passive"))
      (node (ref "C59") (pin "1") (pinfunction "1_1") (pintype "passive"))
      (node (ref "C60") (pin "1") (pinfunction "1_1") (pintype "passive"))
      (node (ref "C61") (pin "1") (pinfunction "1_1") (pintype "passive"))
      (node (ref "C62") (pin "1") (pinfunction "1_1") (pintype "passive"))
      (node (ref "C63") (pin "1") (pinfunction "1_1") (pintype "passive"))
      (node (ref "C64") (pin "1") (pinfunction "1_1") (pintype "passive"))
      (node (ref "C65") (pin "1") (pinfunction "1_1") (pintype "passive"))
      (node (ref "C69") (pin "2") (pinfunction "2_2") (pintype "passive"))
      (node (ref "C70") (pin "2") (pinfunction "2_2") (pintype "passive"))
      (node (ref "IC1") (pin "108") (pinfunction "VDD_8_108") (pintype "passive"))
      (node (ref "IC1") (pin "121") (pinfunction "VDD_9_121") (pintype "passive"))
      (node (ref "IC1") (pin "131") (pinfunction "VDD_10_131") (pintype "passive"))
      (node (ref "IC1") (pin "144") (pinfunction "VDD_11_144") (pintype "passive"))
      (node (ref "IC1") (pin "17") (pinfunction "VDD_1_17") (pintype "passive"))
      (node (ref "IC1") (pin "32") (pinfunction "VREF+_32") (pintype "passive"))
      (node (ref "IC1") (pin "33") (pinfunction "VDDA_33") (pintype "passive"))
      (node (ref "IC1") (pin "39") (pinfunction "VDD_2_39") (pintype "passive"))
      (node (ref "IC1") (pin "52") (pinfunction "VDD_3_52") (pintype "passive"))
      (node (ref "IC1") (pin "62") (pinfunction "VDD_4_62") (pintype "passive"))
      (node (ref "IC1") (pin "72") (pinfunction "VDD_5_72") (pintype "passive"))
      (node (ref "IC1") (pin "84") (pinfunction "VDD_6_84") (pintype "passive"))
      (node (ref "IC1") (pin "95") (pinfunction "VDD_7_95") (pintype "passive"))
      (node (ref "IC2") (pin "108") (pinfunction "VDD_8_108") (pintype "passive"))
      (node (ref "IC2") (pin "121") (pinfunction "VDD_9_121") (pintype "passive"))
      (node (ref "IC2") (pin "131") (pinfunction "VDD_10_131") (pintype "passive"))
      (node (ref "IC2") (pin "144") (pinfunction "VDD_11_144") (pintype "passive"))
      (node (ref "IC2") (pin "17") (pinfunction "VDD_1_17") (pintype "passive"))
      (node (ref "IC2") (pin "32") (pinfunction "VREF+_32") (pintype "passive"))
      (node (ref "IC2") (pin "33") (pinfunction "VDDA_33") (pintype "passive"))
      (node (ref "IC2") (pin "39") (pinfunction "VDD_2_39") (pintype "passive"))
      (node (ref "IC2") (pin "52") (pinfunction "VDD_3_52") (pintype "passive"))
      (node (ref "IC2") (pin "62") (pinfunction "VDD_4_62") (pintype "passive"))
      (node (ref "IC2") (pin "72") (pinfunction "VDD_5_72") (pintype "passive"))
      (node (ref "IC2") (pin "84") (pinfunction "VDD_6_84") (pintype "passive"))
      (node (ref "IC2") (pin "95") (pinfunction "VDD_7_95") (pintype "passive"))
      (node (ref "IC3") (pin "108") (pinfunction "VDD_8_108") (pintype "passive"))
      (node (ref "IC3") (pin "121") (pinfunction "VDD_9_121") (pintype "passive"))
      (node (ref "IC3") (pin "131") (pinfunction "VDD_10_131") (pintype "passive"))
      (node (ref "IC3") (pin "144") (pinfunction "VDD_11_144") (pintype "passive"))
      (node (ref "IC3") (pin "17") (pinfunction "VDD_1_17") (pintype "passive"))
      (node (ref "IC3") (pin "32") (pinfunction "VREF+_32") (pintype "passive"))
      (node (ref "IC3") (pin "33") (pinfunction "VDDA_33") (pintype "passive"))
      (node (ref "IC3") (pin "39") (pinfunction "VDD_2_39") (pintype "passive"))
      (node (ref "IC3") (pin "52") (pinfunction "VDD_3_52") (pintype "passive"))
      (node (ref "IC3") (pin "62") (pinfunction "VDD_4_62") (pintype "passive"))
      (node (ref "IC3") (pin "72") (pinfunction "VDD_5_72") (pintype "passive"))
      (node (ref "IC3") (pin "84") (pinfunction "VDD_6_84") (pintype "passive"))
      (node (ref "IC3") (pin "95") (pinfunction "VDD_7_95") (pintype "passive"))
      (node (ref "IC4") (pin "108") (pinfunction "VDD_8_108") (pintype "passive"))
      (node (ref "IC4") (pin "121") (pinfunction "VDD_9_121") (pintype "passive"))
      (node (ref "IC4") (pin "131") (pinfunction "VDD_10_131") (pintype "passive"))
      (node (ref "IC4") (pin "144") (pinfunction "VDD_11_144") (pintype "passive"))
      (node (ref "IC4") (pin "17") (pinfunction "VDD_1_17") (pintype "passive"))
      (node (ref "IC4") (pin "32") (pinfunction "VREF+_32") (pintype "passive"))
      (node (ref "IC4") (pin "33") (pinfunction "VDDA_33") (pintype "passive"))
      (node (ref "IC4") (pin "39") (pinfunction "VDD_2_39") (pintype "passive"))
      (node (ref "IC4") (pin "52") (pinfunction "VDD_3_52") (pintype "passive"))
      (node (ref "IC4") (pin "62") (pinfunction "VDD_4_62") (pintype "passive"))
      (node (ref "IC4") (pin "72") (pinfunction "VDD_5_72") (pintype "passive"))
      (node (ref "IC4") (pin "84") (pinfunction "VDD_6_84") (pintype "passive"))
      (node (ref "IC4") (pin "95") (pinfunction "VDD_7_95") (pintype "passive"))
      (node (ref "IC5") (pin "108") (pinfunction "VDD_8_108") (pintype "passive"))
      (node (ref "IC5") (pin "121") (pinfunction "VDD_9_121") (pintype "passive"))
      (node (ref "IC5") (pin "131") (pinfunction "VDD_10_131") (pintype "passive"))
      (node (ref "IC5") (pin "144") (pinfunction "VDD_11_144") (pintype "passive"))
      (node (ref "IC5") (pin "17") (pinfunction "VDD_1_17") (pintype "passive"))
      (node (ref "IC5") (pin "32") (pinfunction "VREF+_32") (pintype "passive"))
      (node (ref "IC5") (pin "33") (pinfunction "VDDA_33") (pintype "passive"))
      (node (ref "IC5") (pin "39") (pinfunction "VDD_2_39") (pintype "passive"))
      (node (ref "IC5") (pin "52") (pinfunction "VDD_3_52") (pintype "passive"))
      (node (ref "IC5") (pin "62") (pinfunction "VDD_4_62") (pintype "passive"))
      (node (ref "IC5") (pin "72") (pinfunction "VDD_5_72") (pintype "passive"))
      (node (ref "IC5") (pin "84") (pinfunction "VDD_6_84") (pintype "passive"))
      (node (ref "IC5") (pin "95") (pinfunction "VDD_7_95") (pintype "passive"))
      (node (ref "P2") (pin "3") (pinfunction "3_3") (pintype "passive"))
      (node (ref "PS1") (pin "6") (pinfunction "+Vout_6") (pintype "power_in"))
      (node (ref "R2") (pin "2") (pinfunction "2_2") (pintype "passive"))
      (node (ref "R3") (pin "1") (pinfunction "1_1") (pintype "passive"))
    )
    (net (code "221") (name "GND") (class "Default")
      (node (ref "C1") (pin "2") (pinfunction "2_2") (pintype "passive"))
      (node (ref "C10") (pin "2") (pinfunction "2_2") (pintype "passive"))
      (node (ref "C11") (pin "2") (pinfunction "2_2") (pintype "passive"))
      (node (ref "C12") (pin "2") (pinfunction "2_2") (pintype "passive"))
      (node (ref "C13") (pin "2") (pinfunction "2_2") (pintype "passive"))
      (node (ref "C14") (pin "2") (pinfunction "2_2") (pintype "passive"))
      (node (ref "C15") (pin "2") (pinfunction "2_2") (pintype "passive"))
      (node (ref "C16") (pin "2") (pinfunction "2_2") (pintype "passive"))
      (node (ref "C17") (pin "2") (pinfunction "2_2") (pintype "passive"))
      (node (ref "C18") (pin "2") (pinfunction "2_2") (pintype "passive"))
      (node (ref "C19") (pin "2") (pinfunction "2_2") (pintype "passive"))
      (node (ref "C2") (pin "2") (pinfunction "2_2") (pintype "passive"))
      (node (ref "C20") (pin "2") (pinfunction "2_2") (pintype "passive"))
      (node (ref "C21") (pin "2") (pinfunction "2_2") (pintype "passive"))
      (node (ref "C22") (pin "2") (pinfunction "2_2") (pintype "passive"))
      (node (ref "C23") (pin "2") (pinfunction "2_2") (pintype "passive"))
      (node (ref "C24") (pin "2") (pinfunction "2_2") (pintype "passive"))
      (node (ref "C25") (pin "2") (pinfunction "2_2") (pintype "passive"))
      (node (ref "C26") (pin "2") (pinfunction "2_2") (pintype "passive"))
      (node (ref "C27") (pin "2") (pinfunction "2_2") (pintype "passive"))
      (node (ref "C28") (pin "2") (pinfunction "2_2") (pintype "passive"))
      (node (ref "C29") (pin "2") (pinfunction "2_2") (pintype "passive"))
      (node (ref "C3") (pin "2") (pinfunction "2_2") (pintype "passive"))
      (node (ref "C30") (pin "2") (pinfunction "2_2") (pintype "passive"))
      (node (ref "C31") (pin "2") (pinfunction "2_2") (pintype "passive"))
      (node (ref "C32") (pin "2") (pinfunction "2_2") (pintype "passive"))
      (node (ref "C33") (pin "2") (pinfunction "2_2") (pintype "passive"))
      (node (ref "C34") (pin "2") (pinfunction "2_2") (pintype "passive"))
      (node (ref "C35") (pin "2") (pinfunction "2_2") (pintype "passive"))
      (node (ref "C36") (pin "2") (pinfunction "2_2") (pintype "passive"))
      (node (ref "C37") (pin "2") (pinfunction "2_2") (pintype "passive"))
      (node (ref "C38") (pin "2") (pinfunction "2_2") (pintype "passive"))
      (node (ref "C39") (pin "2") (pinfunction "2_2") (pintype "passive"))
      (node (ref "C4") (pin "2") (pinfunction "2_2") (pintype "passive"))
      (node (ref "C40") (pin "2") (pinfunction "2_2") (pintype "passive"))
      (node (ref "C41") (pin "2") (pinfunction "2_2") (pintype "passive"))
      (node (ref "C42") (pin "2") (pinfunction "2_2") (pintype "passive"))
      (node (ref "C43") (pin "2") (pinfunction "2_2") (pintype "passive"))
      (node (ref "C44") (pin "2") (pinfunction "2_2") (pintype "passive"))
      (node (ref "C45") (pin "2") (pinfunction "2_2") (pintype "passive"))
      (node (ref "C46") (pin "2") (pinfunction "2_2") (pintype "passive"))
      (node (ref "C47") (pin "2") (pinfunction "2_2") (pintype "passive"))
      (node (ref "C48") (pin "2") (pinfunction "2_2") (pintype "passive"))
      (node (ref "C49") (pin "2") (pinfunction "2_2") (pintype "passive"))
      (node (ref "C5") (pin "2") (pinfunction "2_2") (pintype "passive"))
      (node (ref "C50") (pin "2") (pinfunction "2_2") (pintype "passive"))
      (node (ref "C51") (pin "2") (pinfunction "2_2") (pintype "passive"))
      (node (ref "C52") (pin "2") (pinfunction "2_2") (pintype "passive"))
      (node (ref "C53") (pin "2") (pinfunction "2_2") (pintype "passive"))
      (node (ref "C54") (pin "2") (pinfunction "2_2") (pintype "passive"))
      (node (ref "C55") (pin "2") (pinfunction "2_2") (pintype "passive"))
      (node (ref "C56") (pin "2") (pinfunction "2_2") (pintype "passive"))
      (node (ref "C57") (pin "2") (pinfunction "2_2") (pintype "passive"))
      (node (ref "C58") (pin "2") (pinfunction "2_2") (pintype "passive"))
      (node (ref "C59") (pin "2") (pinfunction "2_2") (pintype "passive"))
      (node (ref "C6") (pin "2") (pinfunction "2_2") (pintype "passive"))
      (node (ref "C60") (pin "2") (pinfunction "2_2") (pintype "passive"))
      (node (ref "C61") (pin "2") (pinfunction "2_2") (pintype "passive"))
      (node (ref "C62") (pin "2") (pinfunction "2_2") (pintype "passive"))
      (node (ref "C63") (pin "2") (pinfunction "2_2") (pintype "passive"))
      (node (ref "C64") (pin "2") (pinfunction "2_2") (pintype "passive"))
      (node (ref "C65") (pin "2") (pinfunction "2_2") (pintype "passive"))
      (node (ref "C66") (pin "2") (pinfunction "2_2") (pintype "passive"))
      (node (ref "C68") (pin "1") (pinfunction "1_1") (pintype "passive"))
      (node (ref "C69") (pin "1") (pinfunction "1_1") (pintype "passive"))
      (node (ref "C7") (pin "2") (pinfunction "2_2") (pintype "passive"))
      (node (ref "C8") (pin "2") (pinfunction "2_2") (pintype "passive"))
      (node (ref "C9") (pin "2") (pinfunction "2_2") (pintype "passive"))
      (node (ref "IC1") (pin "107") (pinfunction "VSS_8_107") (pintype "passive"))
      (node (ref "IC1") (pin "120") (pinfunction "VSS_9_120") (pintype "passive"))
      (node (ref "IC1") (pin "130") (pinfunction "VSS_10_130") (pintype "passive"))
      (node (ref "IC1") (pin "143") (pinfunction "VSS_11_143") (pintype "passive"))
      (node (ref "IC1") (pin "16") (pinfunction "VSS_1_16") (pintype "passive"))
      (node (ref "IC1") (pin "30") (pinfunction "VSSA_30") (pintype "passive"))
      (node (ref "IC1") (pin "31") (pinfunction "VREF-_31") (pintype "passive"))
      (node (ref "IC1") (pin "38") (pinfunction "VSS_2_38") (pintype "passive"))
      (node (ref "IC1") (pin "51") (pinfunction "VSS_3_51") (pintype "passive"))
      (node (ref "IC1") (pin "61") (pinfunction "VSS_4_61") (pintype "passive"))
      (node (ref "IC1") (pin "71") (pinfunction "VSS_5_71") (pintype "passive"))
      (node (ref "IC1") (pin "83") (pinfunction "VSS_6_83") (pintype "passive"))
      (node (ref "IC1") (pin "94") (pinfunction "VSS_7_94") (pintype "passive"))
      (node (ref "IC2") (pin "107") (pinfunction "VSS_8_107") (pintype "passive"))
      (node (ref "IC2") (pin "120") (pinfunction "VSS_9_120") (pintype "passive"))
      (node (ref "IC2") (pin "130") (pinfunction "VSS_10_130") (pintype "passive"))
      (node (ref "IC2") (pin "143") (pinfunction "VSS_11_143") (pintype "passive"))
      (node (ref "IC2") (pin "16") (pinfunction "VSS_1_16") (pintype "passive"))
      (node (ref "IC2") (pin "30") (pinfunction "VSSA_30") (pintype "passive"))
      (node (ref "IC2") (pin "31") (pinfunction "VREF-_31") (pintype "passive"))
      (node (ref "IC2") (pin "38") (pinfunction "VSS_2_38") (pintype "passive"))
      (node (ref "IC2") (pin "51") (pinfunction "VSS_3_51") (pintype "passive"))
      (node (ref "IC2") (pin "61") (pinfunction "VSS_4_61") (pintype "passive"))
      (node (ref "IC2") (pin "71") (pinfunction "VSS_5_71") (pintype "passive"))
      (node (ref "IC2") (pin "83") (pinfunction "VSS_6_83") (pintype "passive"))
      (node (ref "IC2") (pin "94") (pinfunction "VSS_7_94") (pintype "passive"))
      (node (ref "IC3") (pin "107") (pinfunction "VSS_8_107") (pintype "passive"))
      (node (ref "IC3") (pin "120") (pinfunction "VSS_9_120") (pintype "passive"))
      (node (ref "IC3") (pin "130") (pinfunction "VSS_10_130") (pintype "passive"))
      (node (ref "IC3") (pin "143") (pinfunction "VSS_11_143") (pintype "passive"))
      (node (ref "IC3") (pin "16") (pinfunction "VSS_1_16") (pintype "passive"))
      (node (ref "IC3") (pin "30") (pinfunction "VSSA_30") (pintype "passive"))
      (node (ref "IC3") (pin "31") (pinfunction "VREF-_31") (pintype "passive"))
      (node (ref "IC3") (pin "38") (pinfunction "VSS_2_38") (pintype "passive"))
      (node (ref "IC3") (pin "51") (pinfunction "VSS_3_51") (pintype "passive"))
      (node (ref "IC3") (pin "61") (pinfunction "VSS_4_61") (pintype "passive"))
      (node (ref "IC3") (pin "71") (pinfunction "VSS_5_71") (pintype "passive"))
      (node (ref "IC3") (pin "83") (pinfunction "VSS_6_83") (pintype "passive"))
      (node (ref "IC3") (pin "94") (pinfunction "VSS_7_94") (pintype "passive"))
      (node (ref "IC4") (pin "107") (pinfunction "VSS_8_107") (pintype "passive"))
      (node (ref "IC4") (pin "120") (pinfunction "VSS_9_120") (pintype "passive"))
      (node (ref "IC4") (pin "130") (pinfunction "VSS_10_130") (pintype "passive"))
      (node (ref "IC4") (pin "143") (pinfunction "VSS_11_143") (pintype "passive"))
      (node (ref "IC4") (pin "16") (pinfunction "VSS_1_16") (pintype "passive"))
      (node (ref "IC4") (pin "30") (pinfunction "VSSA_30") (pintype "passive"))
      (node (ref "IC4") (pin "31") (pinfunction "VREF-_31") (pintype "passive"))
      (node (ref "IC4") (pin "38") (pinfunction "VSS_2_38") (pintype "passive"))
      (node (ref "IC4") (pin "51") (pinfunction "VSS_3_51") (pintype "passive"))
      (node (ref "IC4") (pin "61") (pinfunction "VSS_4_61") (pintype "passive"))
      (node (ref "IC4") (pin "71") (pinfunction "VSS_5_71") (pintype "passive"))
      (node (ref "IC4") (pin "83") (pinfunction "VSS_6_83") (pintype "passive"))
      (node (ref "IC4") (pin "94") (pinfunction "VSS_7_94") (pintype "passive"))
      (node (ref "IC5") (pin "107") (pinfunction "VSS_8_107") (pintype "passive"))
      (node (ref "IC5") (pin "120") (pinfunction "VSS_9_120") (pintype "passive"))
      (node (ref "IC5") (pin "130") (pinfunction "VSS_10_130") (pintype "passive"))
      (node (ref "IC5") (pin "143") (pinfunction "VSS_11_143") (pintype "passive"))
      (node (ref "IC5") (pin "16") (pinfunction "VSS_1_16") (pintype "passive"))
      (node (ref "IC5") (pin "30") (pinfunction "VSSA_30") (pintype "passive"))
      (node (ref "IC5") (pin "31") (pinfunction "VREF-_31") (pintype "passive"))
      (node (ref "IC5") (pin "38") (pinfunction "VSS_2_38") (pintype "passive"))
      (node (ref "IC5") (pin "51") (pinfunction "VSS_3_51") (pintype "passive"))
      (node (ref "IC5") (pin "61") (pinfunction "VSS_4_61") (pintype "passive"))
      (node (ref "IC5") (pin "71") (pinfunction "VSS_5_71") (pintype "passive"))
      (node (ref "IC5") (pin "83") (pinfunction "VSS_6_83") (pintype "passive"))
      (node (ref "IC5") (pin "94") (pinfunction "VSS_7_94") (pintype "passive"))
      (node (ref "M1") (pin "1") (pintype "passive"))
      (node (ref "M2") (pin "1") (pintype "passive"))
      (node (ref "M3") (pin "1") (pintype "passive"))
      (node (ref "M4") (pin "1") (pintype "passive"))
      (node (ref "P1") (pin "10") (pinfunction "10_10") (pintype "passive"))
      (node (ref "P1") (pin "15") (pinfunction "15_15") (pintype "passive"))
      (node (ref "P1") (pin "18") (pinfunction "18_18") (pintype "passive"))
      (node (ref "P1") (pin "2") (pinfunction "2_2") (pintype "passive"))
      (node (ref "P1") (pin "7") (pinfunction "7_7") (pintype "passive"))
      (node (ref "P2") (pin "4") (pinfunction "4_4") (pintype "passive"))
      (node (ref "P3") (pin "2") (pinfunction "2_2") (pintype "passive"))
      (node (ref "PS1") (pin "1") (pinfunction "-VIN(GND)_1") (pintype "power_in"))
      (node (ref "PS1") (pin "7") (pinfunction "-Vout_7") (pintype "power_in"))
      (node (ref "R1") (pin "1") (pinfunction "1_1") (pintype "passive"))
      (node (ref "S1") (pin "1") (pinfunction "COM_1_1") (pintype "passive"))
      (node (ref "S1") (pin "2") (pinfunction "COM_2_2") (pintype "passive"))
    )
    (net (code "222") (name "Net-(IC1-PF0-OSC_IN)") (class "Default")
      (node (ref "C1") (pin "1") (pinfunction "1_1") (pintype "passive"))
      (node (ref "IC1") (pin "23") (pinfunction "PF0-OSC_IN_23") (pintype "passive"))
      (node (ref "Y1") (pin "1") (pinfunction "1_1") (pintype "passive"))
    )
    (net (code "223") (name "Net-(IC1-PF1-OSC_OUT)") (class "Default")
      (node (ref "C2") (pin "1") (pinfunction "1_1") (pintype "passive"))
      (node (ref "IC1") (pin "24") (pinfunction "PF1-OSC_OUT_24") (pintype "passive"))
      (node (ref "Y1") (pin "2") (pinfunction "2_2") (pintype "passive"))
    )
    (net (code "224") (name "Net-(IC2-PF0-OSC_IN)") (class "Default")
      (node (ref "C3") (pin "1") (pinfunction "1_1") (pintype "passive"))
      (node (ref "IC2") (pin "23") (pinfunction "PF0-OSC_IN_23") (pintype "passive"))
      (node (ref "Y2") (pin "1") (pinfunction "1_1") (pintype "passive"))
    )
    (net (code "225") (name "Net-(IC2-PF1-OSC_OUT)") (class "Default")
      (node (ref "C4") (pin "1") (pinfunction "1_1") (pintype "passive"))
      (node (ref "IC2") (pin "24") (pinfunction "PF1-OSC_OUT_24") (pintype "passive"))
      (node (ref "Y2") (pin "2") (pinfunction "2_2") (pintype "passive"))
    )
    (net (code "226") (name "Net-(IC3-PF0-OSC_IN)") (class "Default")
      (node (ref "C5") (pin "1") (pinfunction "1_1") (pintype "passive"))
      (node (ref "IC3") (pin "23") (pinfunction "PF0-OSC_IN_23") (pintype "passive"))
      (node (ref "Y3") (pin "1") (pinfunction "1_1") (pintype "passive"))
    )
    (net (code "227") (name "Net-(IC3-PF1-OSC_OUT)") (class "Default")
      (node (ref "C6") (pin "1") (pinfunction "1_1") (pintype "passive"))
      (node (ref "IC3") (pin "24") (pinfunction "PF1-OSC_OUT_24") (pintype "passive"))
      (node (ref "Y3") (pin "2") (pinfunction "2_2") (pintype "passive"))
    )
    (net (code "228") (name "Net-(IC4-PF0-OSC_IN)") (class "Default")
      (node (ref "C7") (pin "1") (pinfunction "1_1") (pintype "passive"))
      (node (ref "IC4") (pin "23") (pinfunction "PF0-OSC_IN_23") (pintype "passive"))
      (node (ref "Y4") (pin "1") (pinfunction "1_1") (pintype "passive"))
    )
    (net (code "229") (name "Net-(IC4-PF1-OSC_OUT)") (class "Default")
      (node (ref "C8") (pin "1") (pinfunction "1_1") (pintype "passive"))
      (node (ref "IC4") (pin "24") (pinfunction "PF1-OSC_OUT_24") (pintype "passive"))
      (node (ref "Y4") (pin "2") (pinfunction "2_2") (pintype "passive"))
    )
    (net (code "230") (name "Net-(IC5-PF0-OSC_IN)") (class "Default")
      (node (ref "C9") (pin "1") (pinfunction "1_1") (pintype "passive"))
      (node (ref "IC5") (pin "23") (pinfunction "PF0-OSC_IN_23") (pintype "passive"))
      (node (ref "Y5") (pin "1") (pinfunction "1_1") (pintype "passive"))
    )
    (net (code "231") (name "Net-(IC5-PF1-OSC_OUT)") (class "Default")
      (node (ref "C10") (pin "1") (pinfunction "1_1") (pintype "passive"))
      (node (ref "IC5") (pin "24") (pinfunction "PF1-OSC_OUT_24") (pintype "passive"))
      (node (ref "Y5") (pin "2") (pinfunction "2_2") (pintype "passive"))
    )
    (net (code "232") (name "Net-(L1-Pad1)") (class "Default")
      (node (ref "L1") (pin "1") (pinfunction "1_1") (pintype "passive"))
      (node (ref "P3") (pin "1") (pinfunction "1_1") (pintype "passive"))
    )
    (net (code "233") (name "Net-(PS1-+VIN(Vcc))") (class "Default")
      (node (ref "C68") (pin "2") (pinfunction "2_2") (pintype "passive"))
      (node (ref "C70") (pin "1") (pinfunction "1_1") (pintype "passive"))
      (node (ref "L1") (pin "2") (pinfunction "2_2") (pintype "passive"))
      (node (ref "PS1") (pin "2") (pinfunction "+VIN(Vcc)_2") (pintype "power_in"))
    )
    (net (code "234") (name "unconnected-(IC1-PA8-Pad100)") (class "Default")
      (node (ref "IC1") (pin "100") (pinfunction "PA8_100") (pintype "passive"))
    )
    (net (code "235") (name "unconnected-(IC1-PA9-Pad101)") (class "Default")
      (node (ref "IC1") (pin "101") (pinfunction "PA9_101") (pintype "passive"))
    )
    (net (code "236") (name "unconnected-(IC1-PA10-Pad102)") (class "Default")
      (node (ref "IC1") (pin "102") (pinfunction "PA10_102") (pintype "passive"))
    )
    (net (code "237") (name "unconnected-(IC1-PA11-Pad103)") (class "Default")
      (node (ref "IC1") (pin "103") (pinfunction "PA11_103") (pintype "passive"))
    )
    (net (code "238") (name "unconnected-(IC1-PA12-Pad104)") (class "Default")
      (node (ref "IC1") (pin "104") (pinfunction "PA12_104") (pintype "passive"))
    )
    (net (code "239") (name "unconnected-(IC1-PA15-Pad110)") (class "Default")
      (node (ref "IC1") (pin "110") (pinfunction "PA15_110") (pintype "passive"))
    )
    (net (code "240") (name "unconnected-(IC1-PB6-Pad136)") (class "Default")
      (node (ref "IC1") (pin "136") (pinfunction "PB6_136") (pintype "passive"))
    )
    (net (code "241") (name "unconnected-(IC1-PB7-Pad137)") (class "Default")
      (node (ref "IC1") (pin "137") (pinfunction "PB7_137") (pintype "passive"))
    )
    (net (code "242") (name "unconnected-(IC1-PB8-Pad139)") (class "Default")
      (node (ref "IC1") (pin "139") (pinfunction "PB8_139") (pintype "passive"))
    )
    (net (code "243") (name "unconnected-(IC1-PB9-Pad140)") (class "Default")
      (node (ref "IC1") (pin "140") (pinfunction "PB9_140") (pintype "passive"))
    )
    (net (code "244") (name "unconnected-(IC1-PB10-Pad69)") (class "Default")
      (node (ref "IC1") (pin "69") (pinfunction "PB10_69") (pintype "passive"))
    )
    (net (code "245") (name "unconnected-(IC1-PC6-Pad96)") (class "Default")
      (node (ref "IC1") (pin "96") (pinfunction "PC6_96") (pintype "passive"))
    )
    (net (code "246") (name "unconnected-(IC1-PC7-Pad97)") (class "Default")
      (node (ref "IC1") (pin "97") (pinfunction "PC7_97") (pintype "passive"))
    )
    (net (code "247") (name "unconnected-(IC1-PC8-Pad98)") (class "Default")
      (node (ref "IC1") (pin "98") (pinfunction "PC8_98") (pintype "passive"))
    )
    (net (code "248") (name "unconnected-(IC1-PC9-Pad99)") (class "Default")
      (node (ref "IC1") (pin "99") (pinfunction "PC9_99") (pintype "passive"))
    )
    (net (code "249") (name "unconnected-(IC1-PC10-Pad111)") (class "Default")
      (node (ref "IC1") (pin "111") (pinfunction "PC10_111") (pintype "passive"))
    )
    (net (code "250") (name "unconnected-(IC1-PC11-Pad112)") (class "Default")
      (node (ref "IC1") (pin "112") (pinfunction "PC11_112") (pintype "passive"))
    )
    (net (code "251") (name "unconnected-(IC1-PC12-Pad113)") (class "Default")
      (node (ref "IC1") (pin "113") (pinfunction "PC12_113") (pintype "passive"))
    )
    (net (code "252") (name "unconnected-(IC1-PC13-Pad7)") (class "Default")
      (node (ref "IC1") (pin "7") (pinfunction "PC13_7") (pintype "passive"))
    )
    (net (code "253") (name "unconnected-(IC1-PC14-Pad8)") (class "Default")
      (node (ref "IC1") (pin "8") (pinfunction "PC14_8") (pintype "passive"))
    )
    (net (code "254") (name "unconnected-(IC1-PC15-Pad9)") (class "Default")
      (node (ref "IC1") (pin "9") (pinfunction "PC15_9") (pintype "passive"))
    )
    (net (code "255") (name "unconnected-(IC1-PD0-Pad114)") (class "Default")
      (node (ref "IC1") (pin "114") (pinfunction "PD0_114") (pintype "passive"))
    )
    (net (code "256") (name "unconnected-(IC1-PD1-Pad115)") (class "Default")
      (node (ref "IC1") (pin "115") (pinfunction "PD1_115") (pintype "passive"))
    )
    (net (code "257") (name "unconnected-(IC1-PD2-Pad116)") (class "Default")
      (node (ref "IC1") (pin "116") (pinfunction "PD2_116") (pintype "passive"))
    )
    (net (code "258") (name "unconnected-(IC1-PD3-Pad117)") (class "Default")
      (node (ref "IC1") (pin "117") (pinfunction "PD3_117") (pintype "passive"))
    )
    (net (code "259") (name "unconnected-(IC1-PD4-Pad118)") (class "Default")
      (node (ref "IC1") (pin "118") (pinfunction "PD4_118") (pintype "passive"))
    )
    (net (code "260") (name "unconnected-(IC1-PD5-Pad119)") (class "Default")
      (node (ref "IC1") (pin "119") (pinfunction "PD5_119") (pintype "passive"))
    )
    (net (code "261") (name "unconnected-(IC1-PD6-Pad122)") (class "Default")
      (node (ref "IC1") (pin "122") (pinfunction "PD6_122") (pintype "passive"))
    )
    (net (code "262") (name "unconnected-(IC1-PD7-Pad123)") (class "Default")
      (node (ref "IC1") (pin "123") (pinfunction "PD7_123") (pintype "passive"))
    )
    (net (code "263") (name "unconnected-(IC1-PD15-Pad86)") (class "Default")
      (node (ref "IC1") (pin "86") (pinfunction "PD15_86") (pintype "passive"))
    )
    (net (code "264") (name "unconnected-(IC1-PE0-Pad141)") (class "Default")
      (node (ref "IC1") (pin "141") (pinfunction "PE0_141") (pintype "passive"))
    )
    (net (code "265") (name "unconnected-(IC1-PE1-Pad142)") (class "Default")
      (node (ref "IC1") (pin "142") (pinfunction "PE1_142") (pintype "passive"))
    )
    (net (code "266") (name "unconnected-(IC1-PE2-Pad1)") (class "Default")
      (node (ref "IC1") (pin "1") (pinfunction "PE2_1") (pintype "passive"))
    )
    (net (code "267") (name "unconnected-(IC1-PE3-Pad2)") (class "Default")
      (node (ref "IC1") (pin "2") (pinfunction "PE3_2") (pintype "passive"))
    )
    (net (code "268") (name "unconnected-(IC1-PE4-Pad3)") (class "Default")
      (node (ref "IC1") (pin "3") (pinfunction "PE4_3") (pintype "passive"))
    )
    (net (code "269") (name "unconnected-(IC1-PE5-Pad4)") (class "Default")
      (node (ref "IC1") (pin "4") (pinfunction "PE5_4") (pintype "passive"))
    )
    (net (code "270") (name "unconnected-(IC1-PE6-Pad5)") (class "Default")
      (node (ref "IC1") (pin "5") (pinfunction "PE6_5") (pintype "passive"))
    )
    (net (code "271") (name "unconnected-(IC1-PF3-Pad13)") (class "Default")
      (node (ref "IC1") (pin "13") (pinfunction "PF3_13") (pintype "passive"))
    )
    (net (code "272") (name "unconnected-(IC1-PF5-Pad15)") (class "Default")
      (node (ref "IC1") (pin "15") (pinfunction "PF5_15") (pintype "passive"))
    )
    (net (code "273") (name "unconnected-(IC1-PF6-Pad18)") (class "Default")
      (node (ref "IC1") (pin "18") (pinfunction "PF6_18") (pintype "passive"))
    )
    (net (code "274") (name "unconnected-(IC1-PF7-Pad19)") (class "Default")
      (node (ref "IC1") (pin "19") (pinfunction "PF7_19") (pintype "passive"))
    )
    (net (code "275") (name "unconnected-(IC1-PF8-Pad20)") (class "Default")
      (node (ref "IC1") (pin "20") (pinfunction "PF8_20") (pintype "passive"))
    )
    (net (code "276") (name "unconnected-(IC1-PF9-Pad21)") (class "Default")
      (node (ref "IC1") (pin "21") (pinfunction "PF9_21") (pintype "passive"))
    )
    (net (code "277") (name "unconnected-(IC1-PF10-Pad22)") (class "Default")
      (node (ref "IC1") (pin "22") (pinfunction "PF10_22") (pintype "passive"))
    )
    (net (code "278") (name "unconnected-(IC1-PF11-Pad49)") (class "Default")
      (node (ref "IC1") (pin "49") (pinfunction "PF11_49") (pintype "passive"))
    )
    (net (code "279") (name "unconnected-(IC1-PF12-Pad50)") (class "Default")
      (node (ref "IC1") (pin "50") (pinfunction "PF12_50") (pintype "passive"))
    )
    (net (code "280") (name "unconnected-(IC1-PF13-Pad53)") (class "Default")
      (node (ref "IC1") (pin "53") (pinfunction "PF13_53") (pintype "passive"))
    )
    (net (code "281") (name "unconnected-(IC1-PF14-Pad54)") (class "Default")
      (node (ref "IC1") (pin "54") (pinfunction "PF14_54") (pintype "passive"))
    )
    (net (code "282") (name "unconnected-(IC1-PF15-Pad55)") (class "Default")
      (node (ref "IC1") (pin "55") (pinfunction "PF15_55") (pintype "passive"))
    )
    (net (code "283") (name "unconnected-(IC1-PG0-Pad56)") (class "Default")
      (node (ref "IC1") (pin "56") (pinfunction "PG0_56") (pintype "passive"))
    )
    (net (code "284") (name "unconnected-(IC1-PG1-Pad57)") (class "Default")
      (node (ref "IC1") (pin "57") (pinfunction "PG1_57") (pintype "passive"))
    )
    (net (code "285") (name "unconnected-(IC1-PG2-Pad87)") (class "Default")
      (node (ref "IC1") (pin "87") (pinfunction "PG2_87") (pintype "passive"))
    )
    (net (code "286") (name "unconnected-(IC1-PG3-Pad88)") (class "Default")
      (node (ref "IC1") (pin "88") (pinfunction "PG3_88") (pintype "passive"))
    )
    (net (code "287") (name "unconnected-(IC1-PG4-Pad89)") (class "Default")
      (node (ref "IC1") (pin "89") (pinfunction "PG4_89") (pintype "passive"))
    )
    (net (code "288") (name "unconnected-(IC1-PG5-Pad90)") (class "Default")
      (node (ref "IC1") (pin "90") (pinfunction "PG5_90") (pintype "passive"))
    )
    (net (code "289") (name "unconnected-(IC1-PG6-Pad91)") (class "Default")
      (node (ref "IC1") (pin "91") (pinfunction "PG6_91") (pintype "passive"))
    )
    (net (code "290") (name "unconnected-(IC1-PG7-Pad92)") (class "Default")
      (node (ref "IC1") (pin "92") (pinfunction "PG7_92") (pintype "passive"))
    )
    (net (code "291") (name "unconnected-(IC1-PG8-Pad93)") (class "Default")
      (node (ref "IC1") (pin "93") (pinfunction "PG8_93") (pintype "passive"))
    )
    (net (code "292") (name "unconnected-(IC1-PG9-Pad124)") (class "Default")
      (node (ref "IC1") (pin "124") (pinfunction "PG9_124") (pintype "passive"))
    )
    (net (code "293") (name "unconnected-(IC1-PG10-Pad125)") (class "Default")
      (node (ref "IC1") (pin "125") (pinfunction "PG10_125") (pintype "passive"))
    )
    (net (code "294") (name "unconnected-(IC1-PG11-Pad126)") (class "Default")
      (node (ref "IC1") (pin "126") (pinfunction "PG11_126") (pintype "passive"))
    )
    (net (code "295") (name "unconnected-(IC1-PG12-Pad127)") (class "Default")
      (node (ref "IC1") (pin "127") (pinfunction "PG12_127") (pintype "passive"))
    )
    (net (code "296") (name "unconnected-(IC1-PG13-Pad128)") (class "Default")
      (node (ref "IC1") (pin "128") (pinfunction "PG13_128") (pintype "passive"))
    )
    (net (code "297") (name "unconnected-(IC1-PG14-Pad129)") (class "Default")
      (node (ref "IC1") (pin "129") (pinfunction "PG14_129") (pintype "passive"))
    )
    (net (code "298") (name "unconnected-(IC1-PG15-Pad132)") (class "Default")
      (node (ref "IC1") (pin "132") (pinfunction "PG15_132") (pintype "passive"))
    )
    (net (code "299") (name "unconnected-(IC1-PH0-Pad10)") (class "Default")
      (node (ref "IC1") (pin "10") (pinfunction "PH0_10") (pintype "passive"))
    )
    (net (code "300") (name "unconnected-(IC1-PH1-Pad11)") (class "Default")
      (node (ref "IC1") (pin "11") (pinfunction "PH1_11") (pintype "passive"))
    )
    (net (code "301") (name "unconnected-(IC1-PH2-Pad106)") (class "Default")
      (node (ref "IC1") (pin "106") (pinfunction "PH2_106") (pintype "passive"))
    )
    (net (code "302") (name "unconnected-(IC1-VBAT-Pad6)") (class "Default")
      (node (ref "IC1") (pin "6") (pinfunction "VBAT_6") (pintype "passive"))
    )
    (net (code "303") (name "unconnected-(IC2-PA8-Pad100)") (class "Default")
      (node (ref "IC2") (pin "100") (pinfunction "PA8_100") (pintype "passive"))
    )
    (net (code "304") (name "unconnected-(IC2-PA9-Pad101)") (class "Default")
      (node (ref "IC2") (pin "101") (pinfunction "PA9_101") (pintype "passive"))
    )
    (net (code "305") (name "unconnected-(IC2-PA10-Pad102)") (class "Default")
      (node (ref "IC2") (pin "102") (pinfunction "PA10_102") (pintype "passive"))
    )
    (net (code "306") (name "unconnected-(IC2-PA11-Pad103)") (class "Default")
      (node (ref "IC2") (pin "103") (pinfunction "PA11_103") (pintype "passive"))
    )
    (net (code "307") (name "unconnected-(IC2-PA12-Pad104)") (class "Default")
      (node (ref "IC2") (pin "104") (pinfunction "PA12_104") (pintype "passive"))
    )
    (net (code "308") (name "unconnected-(IC2-PA15-Pad110)") (class "Default")
      (node (ref "IC2") (pin "110") (pinfunction "PA15_110") (pintype "passive"))
    )
    (net (code "309") (name "unconnected-(IC2-PB6-Pad136)") (class "Default")
      (node (ref "IC2") (pin "136") (pinfunction "PB6_136") (pintype "passive"))
    )
    (net (code "310") (name "unconnected-(IC2-PB7-Pad137)") (class "Default")
      (node (ref "IC2") (pin "137") (pinfunction "PB7_137") (pintype "passive"))
    )
    (net (code "311") (name "unconnected-(IC2-PB8-Pad139)") (class "Default")
      (node (ref "IC2") (pin "139") (pinfunction "PB8_139") (pintype "passive"))
    )
    (net (code "312") (name "unconnected-(IC2-PB9-Pad140)") (class "Default")
      (node (ref "IC2") (pin "140") (pinfunction "PB9_140") (pintype "passive"))
    )
    (net (code "313") (name "unconnected-(IC2-PB10-Pad69)") (class "Default")
      (node (ref "IC2") (pin "69") (pinfunction "PB10_69") (pintype "passive"))
    )
    (net (code "314") (name "unconnected-(IC2-PC6-Pad96)") (class "Default")
      (node (ref "IC2") (pin "96") (pinfunction "PC6_96") (pintype "passive"))
    )
    (net (code "315") (name "unconnected-(IC2-PC7-Pad97)") (class "Default")
      (node (ref "IC2") (pin "97") (pinfunction "PC7_97") (pintype "passive"))
    )
    (net (code "316") (name "unconnected-(IC2-PC8-Pad98)") (class "Default")
      (node (ref "IC2") (pin "98") (pinfunction "PC8_98") (pintype "passive"))
    )
    (net (code "317") (name "unconnected-(IC2-PC9-Pad99)") (class "Default")
      (node (ref "IC2") (pin "99") (pinfunction "PC9_99") (pintype "passive"))
    )
    (net (code "318") (name "unconnected-(IC2-PC10-Pad111)") (class "Default")
      (node (ref "IC2") (pin "111") (pinfunction "PC10_111") (pintype "passive"))
    )
    (net (code "319") (name "unconnected-(IC2-PC11-Pad112)") (class "Default")
      (node (ref "IC2") (pin "112") (pinfunction "PC11_112") (pintype "passive"))
    )
    (net (code "320") (name "unconnected-(IC2-PC12-Pad113)") (class "Default")
      (node (ref "IC2") (pin "113") (pinfunction "PC12_113") (pintype "passive"))
    )
    (net (code "321") (name "unconnected-(IC2-PC13-Pad7)") (class "Default")
      (node (ref "IC2") (pin "7") (pinfunction "PC13_7") (pintype "passive"))
    )
    (net (code "322") (name "unconnected-(IC2-PC14-Pad8)") (class "Default")
      (node (ref "IC2") (pin "8") (pinfunction "PC14_8") (pintype "passive"))
    )
    (net (code "323") (name "unconnected-(IC2-PC15-Pad9)") (class "Default")
      (node (ref "IC2") (pin "9") (pinfunction "PC15_9") (pintype "passive"))
    )
    (net (code "324") (name "unconnected-(IC2-PD0-Pad114)") (class "Default")
      (node (ref "IC2") (pin "114") (pinfunction "PD0_114") (pintype "passive"))
    )
    (net (code "325") (name "unconnected-(IC2-PD1-Pad115)") (class "Default")
      (node (ref "IC2") (pin "115") (pinfunction "PD1_115") (pintype "passive"))
    )
    (net (code "326") (name "unconnected-(IC2-PD2-Pad116)") (class "Default")
      (node (ref "IC2") (pin "116") (pinfunction "PD2_116") (pintype "passive"))
    )
    (net (code "327") (name "unconnected-(IC2-PD3-Pad117)") (class "Default")
      (node (ref "IC2") (pin "117") (pinfunction "PD3_117") (pintype "passive"))
    )
    (net (code "328") (name "unconnected-(IC2-PD4-Pad118)") (class "Default")
      (node (ref "IC2") (pin "118") (pinfunction "PD4_118") (pintype "passive"))
    )
    (net (code "329") (name "unconnected-(IC2-PD5-Pad119)") (class "Default")
      (node (ref "IC2") (pin "119") (pinfunction "PD5_119") (pintype "passive"))
    )
    (net (code "330") (name "unconnected-(IC2-PD6-Pad122)") (class "Default")
      (node (ref "IC2") (pin "122") (pinfunction "PD6_122") (pintype "passive"))
    )
    (net (code "331") (name "unconnected-(IC2-PD7-Pad123)") (class "Default")
      (node (ref "IC2") (pin "123") (pinfunction "PD7_123") (pintype "passive"))
    )
    (net (code "332") (name "unconnected-(IC2-PD15-Pad86)") (class "Default")
      (node (ref "IC2") (pin "86") (pinfunction "PD15_86") (pintype "passive"))
    )
    (net (code "333") (name "unconnected-(IC2-PE0-Pad141)") (class "Default")
      (node (ref "IC2") (pin "141") (pinfunction "PE0_141") (pintype "passive"))
    )
    (net (code "334") (name "unconnected-(IC2-PE1-Pad142)") (class "Default")
      (node (ref "IC2") (pin "142") (pinfunction "PE1_142") (pintype "passive"))
    )
    (net (code "335") (name "unconnected-(IC2-PE2-Pad1)") (class "Default")
      (node (ref "IC2") (pin "1") (pinfunction "PE2_1") (pintype "passive"))
    )
    (net (code "336") (name "unconnected-(IC2-PE3-Pad2)") (class "Default")
      (node (ref "IC2") (pin "2") (pinfunction "PE3_2") (pintype "passive"))
    )
    (net (code "337") (name "unconnected-(IC2-PE4-Pad3)") (class "Default")
      (node (ref "IC2") (pin "3") (pinfunction "PE4_3") (pintype "passive"))
    )
    (net (code "338") (name "unconnected-(IC2-PE5-Pad4)") (class "Default")
      (node (ref "IC2") (pin "4") (pinfunction "PE5_4") (pintype "passive"))
    )
    (net (code "339") (name "unconnected-(IC2-PE6-Pad5)") (class "Default")
      (node (ref "IC2") (pin "5") (pinfunction "PE6_5") (pintype "passive"))
    )
    (net (code "340") (name "unconnected-(IC2-PF3-Pad13)") (class "Default")
      (node (ref "IC2") (pin "13") (pinfunction "PF3_13") (pintype "passive"))
    )
    (net (code "341") (name "unconnected-(IC2-PF5-Pad15)") (class "Default")
      (node (ref "IC2") (pin "15") (pinfunction "PF5_15") (pintype "passive"))
    )
    (net (code "342") (name "unconnected-(IC2-PF6-Pad18)") (class "Default")
      (node (ref "IC2") (pin "18") (pinfunction "PF6_18") (pintype "passive"))
    )
    (net (code "343") (name "unconnected-(IC2-PF7-Pad19)") (class "Default")
      (node (ref "IC2") (pin "19") (pinfunction "PF7_19") (pintype "passive"))
    )
    (net (code "344") (name "unconnected-(IC2-PF8-Pad20)") (class "Default")
      (node (ref "IC2") (pin "20") (pinfunction "PF8_20") (pintype "passive"))
    )
    (net (code "345") (name "unconnected-(IC2-PF9-Pad21)") (class "Default")
      (node (ref "IC2") (pin "21") (pinfunction "PF9_21") (pintype "passive"))
    )
    (net (code "346") (name "unconnected-(IC2-PF10-Pad22)") (class "Default")
      (node (ref "IC2") (pin "22") (pinfunction "PF10_22") (pintype "passive"))
    )
    (net (code "347") (name "unconnected-(IC2-PF11-Pad49)") (class "Default")
      (node (ref "IC2") (pin "49") (pinfunction "PF11_49") (pintype "passive"))
    )
    (net (code "348") (name "unconnected-(IC2-PF12-Pad50)") (class "Default")
      (node (ref "IC2") (pin "50") (pinfunction "PF12_50") (pintype "passive"))
    )
    (net (code "349") (name "unconnected-(IC2-PF13-Pad53)") (class "Default")
      (node (ref "IC2") (pin "53") (pinfunction "PF13_53") (pintype "passive"))
    )
    (net (code "350") (name "unconnected-(IC2-PF14-Pad54)") (class "Default")
      (node (ref "IC2") (pin "54") (pinfunction "PF14_54") (pintype "passive"))
    )
    (net (code "351") (name "unconnected-(IC2-PF15-Pad55)") (class "Default")
      (node (ref "IC2") (pin "55") (pinfunction "PF15_55") (pintype "passive"))
    )
    (net (code "352") (name "unconnected-(IC2-PG0-Pad56)") (class "Default")
      (node (ref "IC2") (pin "56") (pinfunction "PG0_56") (pintype "passive"))
    )
    (net (code "353") (name "unconnected-(IC2-PG1-Pad57)") (class "Default")
      (node (ref "IC2") (pin "57") (pinfunction "PG1_57") (pintype "passive"))
    )
    (net (code "354") (name "unconnected-(IC2-PG2-Pad87)") (class "Default")
      (node (ref "IC2") (pin "87") (pinfunction "PG2_87") (pintype "passive"))
    )
    (net (code "355") (name "unconnected-(IC2-PG3-Pad88)") (class "Default")
      (node (ref "IC2") (pin "88") (pinfunction "PG3_88") (pintype "passive"))
    )
    (net (code "356") (name "unconnected-(IC2-PG4-Pad89)") (class "Default")
      (node (ref "IC2") (pin "89") (pinfunction "PG4_89") (pintype "passive"))
    )
    (net (code "357") (name "unconnected-(IC2-PG5-Pad90)") (class "Default")
      (node (ref "IC2") (pin "90") (pinfunction "PG5_90") (pintype "passive"))
    )
    (net (code "358") (name "unconnected-(IC2-PG6-Pad91)") (class "Default")
      (node (ref "IC2") (pin "91") (pinfunction "PG6_91") (pintype "passive"))
    )
    (net (code "359") (name "unconnected-(IC2-PG7-Pad92)") (class "Default")
      (node (ref "IC2") (pin "92") (pinfunction "PG7_92") (pintype "passive"))
    )
    (net (code "360") (name "unconnected-(IC2-PG8-Pad93)") (class "Default")
      (node (ref "IC2") (pin "93") (pinfunction "PG8_93") (pintype "passive"))
    )
    (net (code "361") (name "unconnected-(IC2-PG9-Pad124)") (class "Default")
      (node (ref "IC2") (pin "124") (pinfunction "PG9_124") (pintype "passive"))
    )
    (net (code "362") (name "unconnected-(IC2-PG10-Pad125)") (class "Default")
      (node (ref "IC2") (pin "125") (pinfunction "PG10_125") (pintype "passive"))
    )
    (net (code "363") (name "unconnected-(IC2-PG11-Pad126)") (class "Default")
      (node (ref "IC2") (pin "126") (pinfunction "PG11_126") (pintype "passive"))
    )
    (net (code "364") (name "unconnected-(IC2-PG12-Pad127)") (class "Default")
      (node (ref "IC2") (pin "127") (pinfunction "PG12_127") (pintype "passive"))
    )
    (net (code "365") (name "unconnected-(IC2-PG13-Pad128)") (class "Default")
      (node (ref "IC2") (pin "128") (pinfunction "PG13_128") (pintype "passive"))
    )
    (net (code "366") (name "unconnected-(IC2-PG14-Pad129)") (class "Default")
      (node (ref "IC2") (pin "129") (pinfunction "PG14_129") (pintype "passive"))
    )
    (net (code "367") (name "unconnected-(IC2-PG15-Pad132)") (class "Default")
      (node (ref "IC2") (pin "132") (pinfunction "PG15_132") (pintype "passive"))
    )
    (net (code "368") (name "unconnected-(IC2-PH0-Pad10)") (class "Default")
      (node (ref "IC2") (pin "10") (pinfunction "PH0_10") (pintype "passive"))
    )
    (net (code "369") (name "unconnected-(IC2-PH1-Pad11)") (class "Default")
      (node (ref "IC2") (pin "11") (pinfunction "PH1_11") (pintype "passive"))
    )
    (net (code "370") (name "unconnected-(IC2-PH2-Pad106)") (class "Default")
      (node (ref "IC2") (pin "106") (pinfunction "PH2_106") (pintype "passive"))
    )
    (net (code "371") (name "unconnected-(IC2-VBAT-Pad6)") (class "Default")
      (node (ref "IC2") (pin "6") (pinfunction "VBAT_6") (pintype "passive"))
    )
    (net (code "372") (name "unconnected-(IC3-PA8-Pad100)") (class "Default")
      (node (ref "IC3") (pin "100") (pinfunction "PA8_100") (pintype "passive"))
    )
    (net (code "373") (name "unconnected-(IC3-PA9-Pad101)") (class "Default")
      (node (ref "IC3") (pin "101") (pinfunction "PA9_101") (pintype "passive"))
    )
    (net (code "374") (name "unconnected-(IC3-PA10-Pad102)") (class "Default")
      (node (ref "IC3") (pin "102") (pinfunction "PA10_102") (pintype "passive"))
    )
    (net (code "375") (name "unconnected-(IC3-PA11-Pad103)") (class "Default")
      (node (ref "IC3") (pin "103") (pinfunction "PA11_103") (pintype "passive"))
    )
    (net (code "376") (name "unconnected-(IC3-PA12-Pad104)") (class "Default")
      (node (ref "IC3") (pin "104") (pinfunction "PA12_104") (pintype "passive"))
    )
    (net (code "377") (name "unconnected-(IC3-PA15-Pad110)") (class "Default")
      (node (ref "IC3") (pin "110") (pinfunction "PA15_110") (pintype "passive"))
    )
    (net (code "378") (name "unconnected-(IC3-PB6-Pad136)") (class "Default")
      (node (ref "IC3") (pin "136") (pinfunction "PB6_136") (pintype "passive"))
    )
    (net (code "379") (name "unconnected-(IC3-PB7-Pad137)") (class "Default")
      (node (ref "IC3") (pin "137") (pinfunction "PB7_137") (pintype "passive"))
    )
    (net (code "380") (name "unconnected-(IC3-PB8-Pad139)") (class "Default")
      (node (ref "IC3") (pin "139") (pinfunction "PB8_139") (pintype "passive"))
    )
    (net (code "381") (name "unconnected-(IC3-PB9-Pad140)") (class "Default")
      (node (ref "IC3") (pin "140") (pinfunction "PB9_140") (pintype "passive"))
    )
    (net (code "382") (name "unconnected-(IC3-PB10-Pad69)") (class "Default")
      (node (ref "IC3") (pin "69") (pinfunction "PB10_69") (pintype "passive"))
    )
    (net (code "383") (name "unconnected-(IC3-PC6-Pad96)") (class "Default")
      (node (ref "IC3") (pin "96") (pinfunction "PC6_96") (pintype "passive"))
    )
    (net (code "384") (name "unconnected-(IC3-PC7-Pad97)") (class "Default")
      (node (ref "IC3") (pin "97") (pinfunction "PC7_97") (pintype "passive"))
    )
    (net (code "385") (name "unconnected-(IC3-PC8-Pad98)") (class "Default")
      (node (ref "IC3") (pin "98") (pinfunction "PC8_98") (pintype "passive"))
    )
    (net (code "386") (name "unconnected-(IC3-PC9-Pad99)") (class "Default")
      (node (ref "IC3") (pin "99") (pinfunction "PC9_99") (pintype "passive"))
    )
    (net (code "387") (name "unconnected-(IC3-PC10-Pad111)") (class "Default")
      (node (ref "IC3") (pin "111") (pinfunction "PC10_111") (pintype "passive"))
    )
    (net (code "388") (name "unconnected-(IC3-PC11-Pad112)") (class "Default")
      (node (ref "IC3") (pin "112") (pinfunction "PC11_112") (pintype "passive"))
    )
    (net (code "389") (name "unconnected-(IC3-PC12-Pad113)") (class "Default")
      (node (ref "IC3") (pin "113") (pinfunction "PC12_113") (pintype "passive"))
    )
    (net (code "390") (name "unconnected-(IC3-PC13-Pad7)") (class "Default")
      (node (ref "IC3") (pin "7") (pinfunction "PC13_7") (pintype "passive"))
    )
    (net (code "391") (name "unconnected-(IC3-PC14-Pad8)") (class "Default")
      (node (ref "IC3") (pin "8") (pinfunction "PC14_8") (pintype "passive"))
    )
    (net (code "392") (name "unconnected-(IC3-PC15-Pad9)") (class "Default")
      (node (ref "IC3") (pin "9") (pinfunction "PC15_9") (pintype "passive"))
    )
    (net (code "393") (name "unconnected-(IC3-PD0-Pad114)") (class "Default")
      (node (ref "IC3") (pin "114") (pinfunction "PD0_114") (pintype "passive"))
    )
    (net (code "394") (name "unconnected-(IC3-PD1-Pad115)") (class "Default")
      (node (ref "IC3") (pin "115") (pinfunction "PD1_115") (pintype "passive"))
    )
    (net (code "395") (name "unconnected-(IC3-PD2-Pad116)") (class "Default")
      (node (ref "IC3") (pin "116") (pinfunction "PD2_116") (pintype "passive"))
    )
    (net (code "396") (name "unconnected-(IC3-PD3-Pad117)") (class "Default")
      (node (ref "IC3") (pin "117") (pinfunction "PD3_117") (pintype "passive"))
    )
    (net (code "397") (name "unconnected-(IC3-PD4-Pad118)") (class "Default")
      (node (ref "IC3") (pin "118") (pinfunction "PD4_118") (pintype "passive"))
    )
    (net (code "398") (name "unconnected-(IC3-PD5-Pad119)") (class "Default")
      (node (ref "IC3") (pin "119") (pinfunction "PD5_119") (pintype "passive"))
    )
    (net (code "399") (name "unconnected-(IC3-PD6-Pad122)") (class "Default")
      (node (ref "IC3") (pin "122") (pinfunction "PD6_122") (pintype "passive"))
    )
    (net (code "400") (name "unconnected-(IC3-PD7-Pad123)") (class "Default")
      (node (ref "IC3") (pin "123") (pinfunction "PD7_123") (pintype "passive"))
    )
    (net (code "401") (name "unconnected-(IC3-PD15-Pad86)") (class "Default")
      (node (ref "IC3") (pin "86") (pinfunction "PD15_86") (pintype "passive"))
    )
    (net (code "402") (name "unconnected-(IC3-PE0-Pad141)") (class "Default")
      (node (ref "IC3") (pin "141") (pinfunction "PE0_141") (pintype "passive"))
    )
    (net (code "403") (name "unconnected-(IC3-PE1-Pad142)") (class "Default")
      (node (ref "IC3") (pin "142") (pinfunction "PE1_142") (pintype "passive"))
    )
    (net (code "404") (name "unconnected-(IC3-PE2-Pad1)") (class "Default")
      (node (ref "IC3") (pin "1") (pinfunction "PE2_1") (pintype "passive"))
    )
    (net (code "405") (name "unconnected-(IC3-PE3-Pad2)") (class "Default")
      (node (ref "IC3") (pin "2") (pinfunction "PE3_2") (pintype "passive"))
    )
    (net (code "406") (name "unconnected-(IC3-PE4-Pad3)") (class "Default")
      (node (ref "IC3") (pin "3") (pinfunction "PE4_3") (pintype "passive"))
    )
    (net (code "407") (name "unconnected-(IC3-PE5-Pad4)") (class "Default")
      (node (ref "IC3") (pin "4") (pinfunction "PE5_4") (pintype "passive"))
    )
    (net (code "408") (name "unconnected-(IC3-PE6-Pad5)") (class "Default")
      (node (ref "IC3") (pin "5") (pinfunction "PE6_5") (pintype "passive"))
    )
    (net (code "409") (name "unconnected-(IC3-PF3-Pad13)") (class "Default")
      (node (ref "IC3") (pin "13") (pinfunction "PF3_13") (pintype "passive"))
    )
    (net (code "410") (name "unconnected-(IC3-PF5-Pad15)") (class "Default")
      (node (ref "IC3") (pin "15") (pinfunction "PF5_15") (pintype "passive"))
    )
    (net (code "411") (name "unconnected-(IC3-PF6-Pad18)") (class "Default")
      (node (ref "IC3") (pin "18") (pinfunction "PF6_18") (pintype "passive"))
    )
    (net (code "412") (name "unconnected-(IC3-PF7-Pad19)") (class "Default")
      (node (ref "IC3") (pin "19") (pinfunction "PF7_19") (pintype "passive"))
    )
    (net (code "413") (name "unconnected-(IC3-PF8-Pad20)") (class "Default")
      (node (ref "IC3") (pin "20") (pinfunction "PF8_20") (pintype "passive"))
    )
    (net (code "414") (name "unconnected-(IC3-PF9-Pad21)") (class "Default")
      (node (ref "IC3") (pin "21") (pinfunction "PF9_21") (pintype "passive"))
    )
    (net (code "415") (name "unconnected-(IC3-PF10-Pad22)") (class "Default")
      (node (ref "IC3") (pin "22") (pinfunction "PF10_22") (pintype "passive"))
    )
    (net (code "416") (name "unconnected-(IC3-PF11-Pad49)") (class "Default")
      (node (ref "IC3") (pin "49") (pinfunction "PF11_49") (pintype "passive"))
    )
    (net (code "417") (name "unconnected-(IC3-PF12-Pad50)") (class "Default")
      (node (ref "IC3") (pin "50") (pinfunction "PF12_50") (pintype "passive"))
    )
    (net (code "418") (name "unconnected-(IC3-PF13-Pad53)") (class "Default")
      (node (ref "IC3") (pin "53") (pinfunction "PF13_53") (pintype "passive"))
    )
    (net (code "419") (name "unconnected-(IC3-PF14-Pad54)") (class "Default")
      (node (ref "IC3") (pin "54") (pinfunction "PF14_54") (pintype "passive"))
    )
    (net (code "420") (name "unconnected-(IC3-PF15-Pad55)") (class "Default")
      (node (ref "IC3") (pin "55") (pinfunction "PF15_55") (pintype "passive"))
    )
    (net (code "421") (name "unconnected-(IC3-PG0-Pad56)") (class "Default")
      (node (ref "IC3") (pin "56") (pinfunction "PG0_56") (pintype "passive"))
    )
    (net (code "422") (name "unconnected-(IC3-PG1-Pad57)") (class "Default")
      (node (ref "IC3") (pin "57") (pinfunction "PG1_57") (pintype "passive"))
    )
    (net (code "423") (name "unconnected-(IC3-PG2-Pad87)") (class "Default")
      (node (ref "IC3") (pin "87") (pinfunction "PG2_87") (pintype "passive"))
    )
    (net (code "424") (name "unconnected-(IC3-PG3-Pad88)") (class "Default")
      (node (ref "IC3") (pin "88") (pinfunction "PG3_88") (pintype "passive"))
    )
    (net (code "425") (name "unconnected-(IC3-PG4-Pad89)") (class "Default")
      (node (ref "IC3") (pin "89") (pinfunction "PG4_89") (pintype "passive"))
    )
    (net (code "426") (name "unconnected-(IC3-PG5-Pad90)") (class "Default")
      (node (ref "IC3") (pin "90") (pinfunction "PG5_90") (pintype "passive"))
    )
    (net (code "427") (name "unconnected-(IC3-PG6-Pad91)") (class "Default")
      (node (ref "IC3") (pin "91") (pinfunction "PG6_91") (pintype "passive"))
    )
    (net (code "428") (name "unconnected-(IC3-PG7-Pad92)") (class "Default")
      (node (ref "IC3") (pin "92") (pinfunction "PG7_92") (pintype "passive"))
    )
    (net (code "429") (name "unconnected-(IC3-PG8-Pad93)") (class "Default")
      (node (ref "IC3") (pin "93") (pinfunction "PG8_93") (pintype "passive"))
    )
    (net (code "430") (name "unconnected-(IC3-PG9-Pad124)") (class "Default")
      (node (ref "IC3") (pin "124") (pinfunction "PG9_124") (pintype "passive"))
    )
    (net (code "431") (name "unconnected-(IC3-PG10-Pad125)") (class "Default")
      (node (ref "IC3") (pin "125") (pinfunction "PG10_125") (pintype "passive"))
    )
    (net (code "432") (name "unconnected-(IC3-PG11-Pad126)") (class "Default")
      (node (ref "IC3") (pin "126") (pinfunction "PG11_126") (pintype "passive"))
    )
    (net (code "433") (name "unconnected-(IC3-PG12-Pad127)") (class "Default")
      (node (ref "IC3") (pin "127") (pinfunction "PG12_127") (pintype "passive"))
    )
    (net (code "434") (name "unconnected-(IC3-PG13-Pad128)") (class "Default")
      (node (ref "IC3") (pin "128") (pinfunction "PG13_128") (pintype "passive"))
    )
    (net (code "435") (name "unconnected-(IC3-PG14-Pad129)") (class "Default")
      (node (ref "IC3") (pin "129") (pinfunction "PG14_129") (pintype "passive"))
    )
    (net (code "436") (name "unconnected-(IC3-PG15-Pad132)") (class "Default")
      (node (ref "IC3") (pin "132") (pinfunction "PG15_132") (pintype "passive"))
    )
    (net (code "437") (name "unconnected-(IC3-PH0-Pad10)") (class "Default")
      (node (ref "IC3") (pin "10") (pinfunction "PH0_10") (pintype "passive"))
    )
    (net (code "438") (name "unconnected-(IC3-PH1-Pad11)") (class "Default")
      (node (ref "IC3") (pin "11") (pinfunction "PH1_11") (pintype "passive"))
    )
    (net (code "439") (name "unconnected-(IC3-PH2-Pad106)") (class "Default")
      (node (ref "IC3") (pin "106") (pinfunction "PH2_106") (pintype "passive"))
    )
    (net (code "440") (name "unconnected-(IC3-VBAT-Pad6)") (class "Default")
      (node (ref "IC3") (pin "6") (pinfunction "VBAT_6") (pintype "passive"))
    )
    (net (code "441") (name "unconnected-(IC4-PA8-Pad100)") (class "Default")
      (node (ref "IC4") (pin "100") (pinfunction "PA8_100") (pintype "passive"))
    )
    (net (code "442") (name "unconnected-(IC4-PA9-Pad101)") (class "Default")
      (node (ref "IC4") (pin "101") (pinfunction "PA9_101") (pintype "passive"))
    )
    (net (code "443") (name "unconnected-(IC4-PA10-Pad102)") (class "Default")
      (node (ref "IC4") (pin "102") (pinfunction "PA10_102") (pintype "passive"))
    )
    (net (code "444") (name "unconnected-(IC4-PA11-Pad103)") (class "Default")
      (node (ref "IC4") (pin "103") (pinfunction "PA11_103") (pintype "passive"))
    )
    (net (code "445") (name "unconnected-(IC4-PA12-Pad104)") (class "Default")
      (node (ref "IC4") (pin "104") (pinfunction "PA12_104") (pintype "passive"))
    )
    (net (code "446") (name "unconnected-(IC4-PA15-Pad110)") (class "Default")
      (node (ref "IC4") (pin "110") (pinfunction "PA15_110") (pintype "passive"))
    )
    (net (code "447") (name "unconnected-(IC4-PB6-Pad136)") (class "Default")
      (node (ref "IC4") (pin "136") (pinfunction "PB6_136") (pintype "passive"))
    )
    (net (code "448") (name "unconnected-(IC4-PB7-Pad137)") (class "Default")
      (node (ref "IC4") (pin "137") (pinfunction "PB7_137") (pintype "passive"))
    )
    (net (code "449") (name "unconnected-(IC4-PB8-Pad139)") (class "Default")
      (node (ref "IC4") (pin "139") (pinfunction "PB8_139") (pintype "passive"))
    )
    (net (code "450") (name "unconnected-(IC4-PB9-Pad140)") (class "Default")
      (node (ref "IC4") (pin "140") (pinfunction "PB9_140") (pintype "passive"))
    )
    (net (code "451") (name "unconnected-(IC4-PB10-Pad69)") (class "Default")
      (node (ref "IC4") (pin "69") (pinfunction "PB10_69") (pintype "passive"))
    )
    (net (code "452") (name "unconnected-(IC4-PC6-Pad96)") (class "Default")
      (node (ref "IC4") (pin "96") (pinfunction "PC6_96") (pintype "passive"))
    )
    (net (code "453") (name "unconnected-(IC4-PC7-Pad97)") (class "Default")
      (node (ref "IC4") (pin "97") (pinfunction "PC7_97") (pintype "passive"))
    )
    (net (code "454") (name "unconnected-(IC4-PC8-Pad98)") (class "Default")
      (node (ref "IC4") (pin "98") (pinfunction "PC8_98") (pintype "passive"))
    )
    (net (code "455") (name "unconnected-(IC4-PC9-Pad99)") (class "Default")
      (node (ref "IC4") (pin "99") (pinfunction "PC9_99") (pintype "passive"))
    )
    (net (code "456") (name "unconnected-(IC4-PC10-Pad111)") (class "Default")
      (node (ref "IC4") (pin "111") (pinfunction "PC10_111") (pintype "passive"))
    )
    (net (code "457") (name "unconnected-(IC4-PC11-Pad112)") (class "Default")
      (node (ref "IC4") (pin "112") (pinfunction "PC11_112") (pintype "passive"))
    )
    (net (code "458") (name "unconnected-(IC4-PC12-Pad113)") (class "Default")
      (node (ref "IC4") (pin "113") (pinfunction "PC12_113") (pintype "passive"))
    )
    (net (code "459") (name "unconnected-(IC4-PC13-Pad7)") (class "Default")
      (node (ref "IC4") (pin "7") (pinfunction "PC13_7") (pintype "passive"))
    )
    (net (code "460") (name "unconnected-(IC4-PC14-Pad8)") (class "Default")
      (node (ref "IC4") (pin "8") (pinfunction "PC14_8") (pintype "passive"))
    )
    (net (code "461") (name "unconnected-(IC4-PC15-Pad9)") (class "Default")
      (node (ref "IC4") (pin "9") (pinfunction "PC15_9") (pintype "passive"))
    )
    (net (code "462") (name "unconnected-(IC4-PD0-Pad114)") (class "Default")
      (node (ref "IC4") (pin "114") (pinfunction "PD0_114") (pintype "passive"))
    )
    (net (code "463") (name "unconnected-(IC4-PD1-Pad115)") (class "Default")
      (node (ref "IC4") (pin "115") (pinfunction "PD1_115") (pintype "passive"))
    )
    (net (code "464") (name "unconnected-(IC4-PD2-Pad116)") (class "Default")
      (node (ref "IC4") (pin "116") (pinfunction "PD2_116") (pintype "passive"))
    )
    (net (code "465") (name "unconnected-(IC4-PD3-Pad117)") (class "Default")
      (node (ref "IC4") (pin "117") (pinfunction "PD3_117") (pintype "passive"))
    )
    (net (code "466") (name "unconnected-(IC4-PD4-Pad118)") (class "Default")
      (node (ref "IC4") (pin "118") (pinfunction "PD4_118") (pintype "passive"))
    )
    (net (code "467") (name "unconnected-(IC4-PD5-Pad119)") (class "Default")
      (node (ref "IC4") (pin "119") (pinfunction "PD5_119") (pintype "passive"))
    )
    (net (code "468") (name "unconnected-(IC4-PD6-Pad122)") (class "Default")
      (node (ref "IC4") (pin "122") (pinfunction "PD6_122") (pintype "passive"))
    )
    (net (code "469") (name "unconnected-(IC4-PD7-Pad123)") (class "Default")
      (node (ref "IC4") (pin "123") (pinfunction "PD7_123") (pintype "passive"))
    )
    (net (code "470") (name "unconnected-(IC4-PD15-Pad86)") (class "Default")
      (node (ref "IC4") (pin "86") (pinfunction "PD15_86") (pintype "passive"))
    )
    (net (code "471") (name "unconnected-(IC4-PE0-Pad141)") (class "Default")
      (node (ref "IC4") (pin "141") (pinfunction "PE0_141") (pintype "passive"))
    )
    (net (code "472") (name "unconnected-(IC4-PE1-Pad142)") (class "Default")
      (node (ref "IC4") (pin "142") (pinfunction "PE1_142") (pintype "passive"))
    )
    (net (code "473") (name "unconnected-(IC4-PE2-Pad1)") (class "Default")
      (node (ref "IC4") (pin "1") (pinfunction "PE2_1") (pintype "passive"))
    )
    (net (code "474") (name "unconnected-(IC4-PE3-Pad2)") (class "Default")
      (node (ref "IC4") (pin "2") (pinfunction "PE3_2") (pintype "passive"))
    )
    (net (code "475") (name "unconnected-(IC4-PE4-Pad3)") (class "Default")
      (node (ref "IC4") (pin "3") (pinfunction "PE4_3") (pintype "passive"))
    )
    (net (code "476") (name "unconnected-(IC4-PE5-Pad4)") (class "Default")
      (node (ref "IC4") (pin "4") (pinfunction "PE5_4") (pintype "passive"))
    )
    (net (code "477") (name "unconnected-(IC4-PE6-Pad5)") (class "Default")
      (node (ref "IC4") (pin "5") (pinfunction "PE6_5") (pintype "passive"))
    )
    (net (code "478") (name "unconnected-(IC4-PF3-Pad13)") (class "Default")
      (node (ref "IC4") (pin "13") (pinfunction "PF3_13") (pintype "passive"))
    )
    (net (code "479") (name "unconnected-(IC4-PF5-Pad15)") (class "Default")
      (node (ref "IC4") (pin "15") (pinfunction "PF5_15") (pintype "passive"))
    )
    (net (code "480") (name "unconnected-(IC4-PF6-Pad18)") (class "Default")
      (node (ref "IC4") (pin "18") (pinfunction "PF6_18") (pintype "passive"))
    )
    (net (code "481") (name "unconnected-(IC4-PF7-Pad19)") (class "Default")
      (node (ref "IC4") (pin "19") (pinfunction "PF7_19") (pintype "passive"))
    )
    (net (code "482") (name "unconnected-(IC4-PF8-Pad20)") (class "Default")
      (node (ref "IC4") (pin "20") (pinfunction "PF8_20") (pintype "passive"))
    )
    (net (code "483") (name "unconnected-(IC4-PF9-Pad21)") (class "Default")
      (node (ref "IC4") (pin "21") (pinfunction "PF9_21") (pintype "passive"))
    )
    (net (code "484") (name "unconnected-(IC4-PF10-Pad22)") (class "Default")
      (node (ref "IC4") (pin "22") (pinfunction "PF10_22") (pintype "passive"))
    )
    (net (code "485") (name "unconnected-(IC4-PF11-Pad49)") (class "Default")
      (node (ref "IC4") (pin "49") (pinfunction "PF11_49") (pintype "passive"))
    )
    (net (code "486") (name "unconnected-(IC4-PF12-Pad50)") (class "Default")
      (node (ref "IC4") (pin "50") (pinfunction "PF12_50") (pintype "passive"))
    )
    (net (code "487") (name "unconnected-(IC4-PF13-Pad53)") (class "Default")
      (node (ref "IC4") (pin "53") (pinfunction "PF13_53") (pintype "passive"))
    )
    (net (code "488") (name "unconnected-(IC4-PF14-Pad54)") (class "Default")
      (node (ref "IC4") (pin "54") (pinfunction "PF14_54") (pintype "passive"))
    )
    (net (code "489") (name "unconnected-(IC4-PF15-Pad55)") (class "Default")
      (node (ref "IC4") (pin "55") (pinfunction "PF15_55") (pintype "passive"))
    )
    (net (code "490") (name "unconnected-(IC4-PG0-Pad56)") (class "Default")
      (node (ref "IC4") (pin "56") (pinfunction "PG0_56") (pintype "passive"))
    )
    (net (code "491") (name "unconnected-(IC4-PG1-Pad57)") (class "Default")
      (node (ref "IC4") (pin "57") (pinfunction "PG1_57") (pintype "passive"))
    )
    (net (code "492") (name "unconnected-(IC4-PG2-Pad87)") (class "Default")
      (node (ref "IC4") (pin "87") (pinfunction "PG2_87") (pintype "passive"))
    )
    (net (code "493") (name "unconnected-(IC4-PG3-Pad88)") (class "Default")
      (node (ref "IC4") (pin "88") (pinfunction "PG3_88") (pintype "passive"))
    )
    (net (code "494") (name "unconnected-(IC4-PG4-Pad89)") (class "Default")
      (node (ref "IC4") (pin "89") (pinfunction "PG4_89") (pintype "passive"))
    )
    (net (code "495") (name "unconnected-(IC4-PG5-Pad90)") (class "Default")
      (node (ref "IC4") (pin "90") (pinfunction "PG5_90") (pintype "passive"))
    )
    (net (code "496") (name "unconnected-(IC4-PG6-Pad91)") (class "Default")
      (node (ref "IC4") (pin "91") (pinfunction "PG6_91") (pintype "passive"))
    )
    (net (code "497") (name "unconnected-(IC4-PG7-Pad92)") (class "Default")
      (node (ref "IC4") (pin "92") (pinfunction "PG7_92") (pintype "passive"))
    )
    (net (code "498") (name "unconnected-(IC4-PG8-Pad93)") (class "Default")
      (node (ref "IC4") (pin "93") (pinfunction "PG8_93") (pintype "passive"))
    )
    (net (code "499") (name "unconnected-(IC4-PG9-Pad124)") (class "Default")
      (node (ref "IC4") (pin "124") (pinfunction "PG9_124") (pintype "passive"))
    )
    (net (code "500") (name "unconnected-(IC4-PG10-Pad125)") (class "Default")
      (node (ref "IC4") (pin "125") (pinfunction "PG10_125") (pintype "passive"))
    )
    (net (code "501") (name "unconnected-(IC4-PG11-Pad126)") (class "Default")
      (node (ref "IC4") (pin "126") (pinfunction "PG11_126") (pintype "passive"))
    )
    (net (code "502") (name "unconnected-(IC4-PG12-Pad127)") (class "Default")
      (node (ref "IC4") (pin "127") (pinfunction "PG12_127") (pintype "passive"))
    )
    (net (code "503") (name "unconnected-(IC4-PG13-Pad128)") (class "Default")
      (node (ref "IC4") (pin "128") (pinfunction "PG13_128") (pintype "passive"))
    )
    (net (code "504") (name "unconnected-(IC4-PG14-Pad129)") (class "Default")
      (node (ref "IC4") (pin "129") (pinfunction "PG14_129") (pintype "passive"))
    )
    (net (code "505") (name "unconnected-(IC4-PG15-Pad132)") (class "Default")
      (node (ref "IC4") (pin "132") (pinfunction "PG15_132") (pintype "passive"))
    )
    (net (code "506") (name "unconnected-(IC4-PH0-Pad10)") (class "Default")
      (node (ref "IC4") (pin "10") (pinfunction "PH0_10") (pintype "passive"))
    )
    (net (code "507") (name "unconnected-(IC4-PH1-Pad11)") (class "Default")
      (node (ref "IC4") (pin "11") (pinfunction "PH1_11") (pintype "passive"))
    )
    (net (code "508") (name "unconnected-(IC4-PH2-Pad106)") (class "Default")
      (node (ref "IC4") (pin "106") (pinfunction "PH2_106") (pintype "passive"))
    )
    (net (code "509") (name "unconnected-(IC4-VBAT-Pad6)") (class "Default")
      (node (ref "IC4") (pin "6") (pinfunction "VBAT_6") (pintype "passive"))
    )
    (net (code "510") (name "unconnected-(IC5-PA8-Pad100)") (class "Default")
      (node (ref "IC5") (pin "100") (pinfunction "PA8_100") (pintype "passive"))
    )
    (net (code "511") (name "unconnected-(IC5-PA9-Pad101)") (class "Default")
      (node (ref "IC5") (pin "101") (pinfunction "PA9_101") (pintype "passive"))
    )
    (net (code "512") (name "unconnected-(IC5-PA10-Pad102)") (class "Default")
      (node (ref "IC5") (pin "102") (pinfunction "PA10_102") (pintype "passive"))
    )
    (net (code "513") (name "unconnected-(IC5-PA11-Pad103)") (class "Default")
      (node (ref "IC5") (pin "103") (pinfunction "PA11_103") (pintype "passive"))
    )
    (net (code "514") (name "unconnected-(IC5-PA12-Pad104)") (class "Default")
      (node (ref "IC5") (pin "104") (pinfunction "PA12_104") (pintype "passive"))
    )
    (net (code "515") (name "unconnected-(IC5-PA15-Pad110)") (class "Default")
      (node (ref "IC5") (pin "110") (pinfunction "PA15_110") (pintype "passive"))
    )
    (net (code "516") (name "unconnected-(IC5-PB6-Pad136)") (class "Default")
      (node (ref "IC5") (pin "136") (pinfunction "PB6_136") (pintype "passive"))
    )
    (net (code "517") (name "unconnected-(IC5-PB7-Pad137)") (class "Default")
      (node (ref "IC5") (pin "137") (pinfunction "PB7_137") (pintype "passive"))
    )
    (net (code "518") (name "unconnected-(IC5-PB8-Pad139)") (class "Default")
      (node (ref "IC5") (pin "139") (pinfunction "PB8_139") (pintype "passive"))
    )
    (net (code "519") (name "unconnected-(IC5-PB9-Pad140)") (class "Default")
      (node (ref "IC5") (pin "140") (pinfunction "PB9_140") (pintype "passive"))
    )
    (net (code "520") (name "unconnected-(IC5-PB10-Pad69)") (class "Default")
      (node (ref "IC5") (pin "69") (pinfunction "PB10_69") (pintype "passive"))
    )
    (net (code "521") (name "unconnected-(IC5-PC6-Pad96)") (class "Default")
      (node (ref "IC5") (pin "96") (pinfunction "PC6_96") (pintype "passive"))
    )
    (net (code "522") (name "unconnected-(IC5-PC7-Pad97)") (class "Default")
      (node (ref "IC5") (pin "97") (pinfunction "PC7_97") (pintype "passive"))
    )
    (net (code "523") (name "unconnected-(IC5-PC8-Pad98)") (class "Default")
      (node (ref "IC5") (pin "98") (pinfunction "PC8_98") (pintype "passive"))
    )
    (net (code "524") (name "unconnected-(IC5-PC9-Pad99)") (class "Default")
      (node (ref "IC5") (pin "99") (pinfunction "PC9_99") (pintype "passive"))
    )
    (net (code "525") (name "unconnected-(IC5-PC10-Pad111)") (class "Default")
      (node (ref "IC5") (pin "111") (pinfunction "PC10_111") (pintype "passive"))
    )
    (net (code "526") (name "unconnected-(IC5-PC11-Pad112)") (class "Default")
      (node (ref "IC5") (pin "112") (pinfunction "PC11_112") (pintype "passive"))
    )
    (net (code "527") (name "unconnected-(IC5-PC12-Pad113)") (class "Default")
      (node (ref "IC5") (pin "113") (pinfunction "PC12_113") (pintype "passive"))
    )
    (net (code "528") (name "unconnected-(IC5-PC13-Pad7)") (class "Default")
      (node (ref "IC5") (pin "7") (pinfunction "PC13_7") (pintype "passive"))
    )
    (net (code "529") (name "unconnected-(IC5-PC14-Pad8)") (class "Default")
      (node (ref "IC5") (pin "8") (pinfunction "PC14_8") (pintype "passive"))
    )
    (net (code "530") (name "unconnected-(IC5-PC15-Pad9)") (class "Default")
      (node (ref "IC5") (pin "9") (pinfunction "PC15_9") (pintype "passive"))
    )
    (net (code "531") (name "unconnected-(IC5-PD0-Pad114)") (class "Default")
      (node (ref "IC5") (pin "114") (pinfunction "PD0_114") (pintype "passive"))
    )
    (net (code "532") (name "unconnected-(IC5-PD1-Pad115)") (class "Default")
      (node (ref "IC5") (pin "115") (pinfunction "PD1_115") (pintype "passive"))
    )
    (net (code "533") (name "unconnected-(IC5-PD2-Pad116)") (class "Default")
      (node (ref "IC5") (pin "116") (pinfunction "PD2_116") (pintype "passive"))
    )
    (net (code "534") (name "unconnected-(IC5-PD3-Pad117)") (class "Default")
      (node (ref "IC5") (pin "117") (pinfunction "PD3_117") (pintype "passive"))
    )
    (net (code "535") (name "unconnected-(IC5-PD4-Pad118)") (class "Default")
      (node (ref "IC5") (pin "118") (pinfunction "PD4_118") (pintype "passive"))
    )
    (net (code "536") (name "unconnected-(IC5-PD5-Pad119)") (class "Default")
      (node (ref "IC5") (pin "119") (pinfunction "PD5_119") (pintype "passive"))
    )
    (net (code "537") (name "unconnected-(IC5-PD6-Pad122)") (class "Default")
      (node (ref "IC5") (pin "122") (pinfunction "PD6_122") (pintype "passive"))
    )
    (net (code "538") (name "unconnected-(IC5-PD7-Pad123)") (class "Default")
      (node (ref "IC5") (pin "123") (pinfunction "PD7_123") (pintype "passive"))
    )
    (net (code "539") (name "unconnected-(IC5-PD15-Pad86)") (class "Default")
      (node (ref "IC5") (pin "86") (pinfunction "PD15_86") (pintype "passive"))
    )
    (net (code "540") (name "unconnected-(IC5-PE0-Pad141)") (class "Default")
      (node (ref "IC5") (pin "141") (pinfunction "PE0_141") (pintype "passive"))
    )
    (net (code "541") (name "unconnected-(IC5-PE1-Pad142)") (class "Default")
      (node (ref "IC5") (pin "142") (pinfunction "PE1_142") (pintype "passive"))
    )
    (net (code "542") (name "unconnected-(IC5-PE2-Pad1)") (class "Default")
      (node (ref "IC5") (pin "1") (pinfunction "PE2_1") (pintype "passive"))
    )
    (net (code "543") (name "unconnected-(IC5-PE3-Pad2)") (class "Default")
      (node (ref "IC5") (pin "2") (pinfunction "PE3_2") (pintype "passive"))
    )
    (net (code "544") (name "unconnected-(IC5-PE4-Pad3)") (class "Default")
      (node (ref "IC5") (pin "3") (pinfunction "PE4_3") (pintype "passive"))
    )
    (net (code "545") (name "unconnected-(IC5-PE5-Pad4)") (class "Default")
      (node (ref "IC5") (pin "4") (pinfunction "PE5_4") (pintype "passive"))
    )
    (net (code "546") (name "unconnected-(IC5-PE6-Pad5)") (class "Default")
      (node (ref "IC5") (pin "5") (pinfunction "PE6_5") (pintype "passive"))
    )
    (net (code "547") (name "unconnected-(IC5-PF3-Pad13)") (class "Default")
      (node (ref "IC5") (pin "13") (pinfunction "PF3_13") (pintype "passive"))
    )
    (net (code "548") (name "unconnected-(IC5-PF5-Pad15)") (class "Default")
      (node (ref "IC5") (pin "15") (pinfunction "PF5_15") (pintype "passive"))
    )
    (net (code "549") (name "unconnected-(IC5-PF6-Pad18)") (class "Default")
      (node (ref "IC5") (pin "18") (pinfunction "PF6_18") (pintype "passive"))
    )
    (net (code "550") (name "unconnected-(IC5-PF7-Pad19)") (class "Default")
      (node (ref "IC5") (pin "19") (pinfunction "PF7_19") (pintype "passive"))
    )
    (net (code "551") (name "unconnected-(IC5-PF8-Pad20)") (class "Default")
      (node (ref "IC5") (pin "20") (pinfunction "PF8_20") (pintype "passive"))
    )
    (net (code "552") (name "unconnected-(IC5-PF9-Pad21)") (class "Default")
      (node (ref "IC5") (pin "21") (pinfunction "PF9_21") (pintype "passive"))
    )
    (net (code "553") (name "unconnected-(IC5-PF10-Pad22)") (class "Default")
      (node (ref "IC5") (pin "22") (pinfunction "PF10_22") (pintype "passive"))
    )
    (net (code "554") (name "unconnected-(IC5-PF11-Pad49)") (class "Default")
      (node (ref "IC5") (pin "49") (pinfunction "PF11_49") (pintype "passive"))
    )
    (net (code "555") (name "unconnected-(IC5-PF12-Pad50)") (class "Default")
      (node (ref "IC5") (pin "50") (pinfunction "PF12_50") (pintype "passive"))
    )
    (net (code "556") (name "unconnected-(IC5-PF13-Pad53)") (class "Default")
      (node (ref "IC5") (pin "53") (pinfunction "PF13_53") (pintype "passive"))
    )
    (net (code "557") (name "unconnected-(IC5-PF14-Pad54)") (class "Default")
      (node (ref "IC5") (pin "54") (pinfunction "PF14_54") (pintype "passive"))
    )
    (net (code "558") (name "unconnected-(IC5-PF15-Pad55)") (class "Default")
      (node (ref "IC5") (pin "55") (pinfunction "PF15_55") (pintype "passive"))
    )
    (net (code "559") (name "unconnected-(IC5-PG0-Pad56)") (class "Default")
      (node (ref "IC5") (pin "56") (pinfunction "PG0_56") (pintype "passive"))
    )
    (net (code "560") (name "unconnected-(IC5-PG1-Pad57)") (class "Default")
      (node (ref "IC5") (pin "57") (pinfunction "PG1_57") (pintype "passive"))
    )
    (net (code "561") (name "unconnected-(IC5-PG2-Pad87)") (class "Default")
      (node (ref "IC5") (pin "87") (pinfunction "PG2_87") (pintype "passive"))
    )
    (net (code "562") (name "unconnected-(IC5-PG3-Pad88)") (class "Default")
      (node (ref "IC5") (pin "88") (pinfunction "PG3_88") (pintype "passive"))
    )
    (net (code "563") (name "unconnected-(IC5-PG4-Pad89)") (class "Default")
      (node (ref "IC5") (pin "89") (pinfunction "PG4_89") (pintype "passive"))
    )
    (net (code "564") (name "unconnected-(IC5-PG5-Pad90)") (class "Default")
      (node (ref "IC5") (pin "90") (pinfunction "PG5_90") (pintype "passive"))
    )
    (net (code "565") (name "unconnected-(IC5-PG6-Pad91)") (class "Default")
      (node (ref "IC5") (pin "91") (pinfunction "PG6_91") (pintype "passive"))
    )
    (net (code "566") (name "unconnected-(IC5-PG7-Pad92)") (class "Default")
      (node (ref "IC5") (pin "92") (pinfunction "PG7_92") (pintype "passive"))
    )
    (net (code "567") (name "unconnected-(IC5-PG8-Pad93)") (class "Default")
      (node (ref "IC5") (pin "93") (pinfunction "PG8_93") (pintype "passive"))
    )
    (net (code "568") (name "unconnected-(IC5-PG9-Pad124)") (class "Default")
      (node (ref "IC5") (pin "124") (pinfunction "PG9_124") (pintype "passive"))
    )
    (net (code "569") (name "unconnected-(IC5-PG10-Pad125)") (class "Default")
      (node (ref "IC5") (pin "125") (pinfunction "PG10_125") (pintype "passive"))
    )
    (net (code "570") (name "unconnected-(IC5-PG11-Pad126)") (class "Default")
      (node (ref "IC5") (pin "126") (pinfunction "PG11_126") (pintype "passive"))
    )
    (net (code "571") (name "unconnected-(IC5-PG12-Pad127)") (class "Default")
      (node (ref "IC5") (pin "127") (pinfunction "PG12_127") (pintype "passive"))
    )
    (net (code "572") (name "unconnected-(IC5-PG13-Pad128)") (class "Default")
      (node (ref "IC5") (pin "128") (pinfunction "PG13_128") (pintype "passive"))
    )
    (net (code "573") (name "unconnected-(IC5-PG14-Pad129)") (class "Default")
      (node (ref "IC5") (pin "129") (pinfunction "PG14_129") (pintype "passive"))
    )
    (net (code "574") (name "unconnected-(IC5-PG15-Pad132)") (class "Default")
      (node (ref "IC5") (pin "132") (pinfunction "PG15_132") (pintype "passive"))
    )
    (net (code "575") (name "unconnected-(IC5-PH0-Pad10)") (class "Default")
      (node (ref "IC5") (pin "10") (pinfunction "PH0_10") (pintype "passive"))
    )
    (net (code "576") (name "unconnected-(IC5-PH1-Pad11)") (class "Default")
      (node (ref "IC5") (pin "11") (pinfunction "PH1_11") (pintype "passive"))
    )
    (net (code "577") (name "unconnected-(IC5-PH2-Pad106)") (class "Default")
      (node (ref "IC5") (pin "106") (pinfunction "PH2_106") (pintype "passive"))
    )
    (net (code "578") (name "unconnected-(IC5-VBAT-Pad6)") (class "Default")
      (node (ref "IC5") (pin "6") (pinfunction "VBAT_6") (pintype "passive"))
    )
    (net (code "579") (name "unconnected-(PS1-Case-Pad9)") (class "Default")
      (node (ref "PS1") (pin "9") (pinfunction "Case_9") (pintype "power_in"))
    )
    (net (code "580") (name "unconnected-(PS1-Case-Pad10)") (class "Default")
      (node (ref "PS1") (pin "10") (pinfunction "Case_10") (pintype "power_in"))
    )
    (net (code "581") (name "unconnected-(PS1-NC-Pad8)") (class "Default")
      (node (ref "PS1") (pin "8") (pinfunction "NC_8") (pintype "power_in"))
    )
    (net (code "582") (name "unconnected-(PS1-Remote-Pad3)") (class "Default")
      (node (ref "PS1") (pin "3") (pinfunction "Remote_3") (pintype "power_in"))
    )
  )
)
